# BeagleBone_Blue.net
KiCad netlist of a schematic drawn in EAGLE
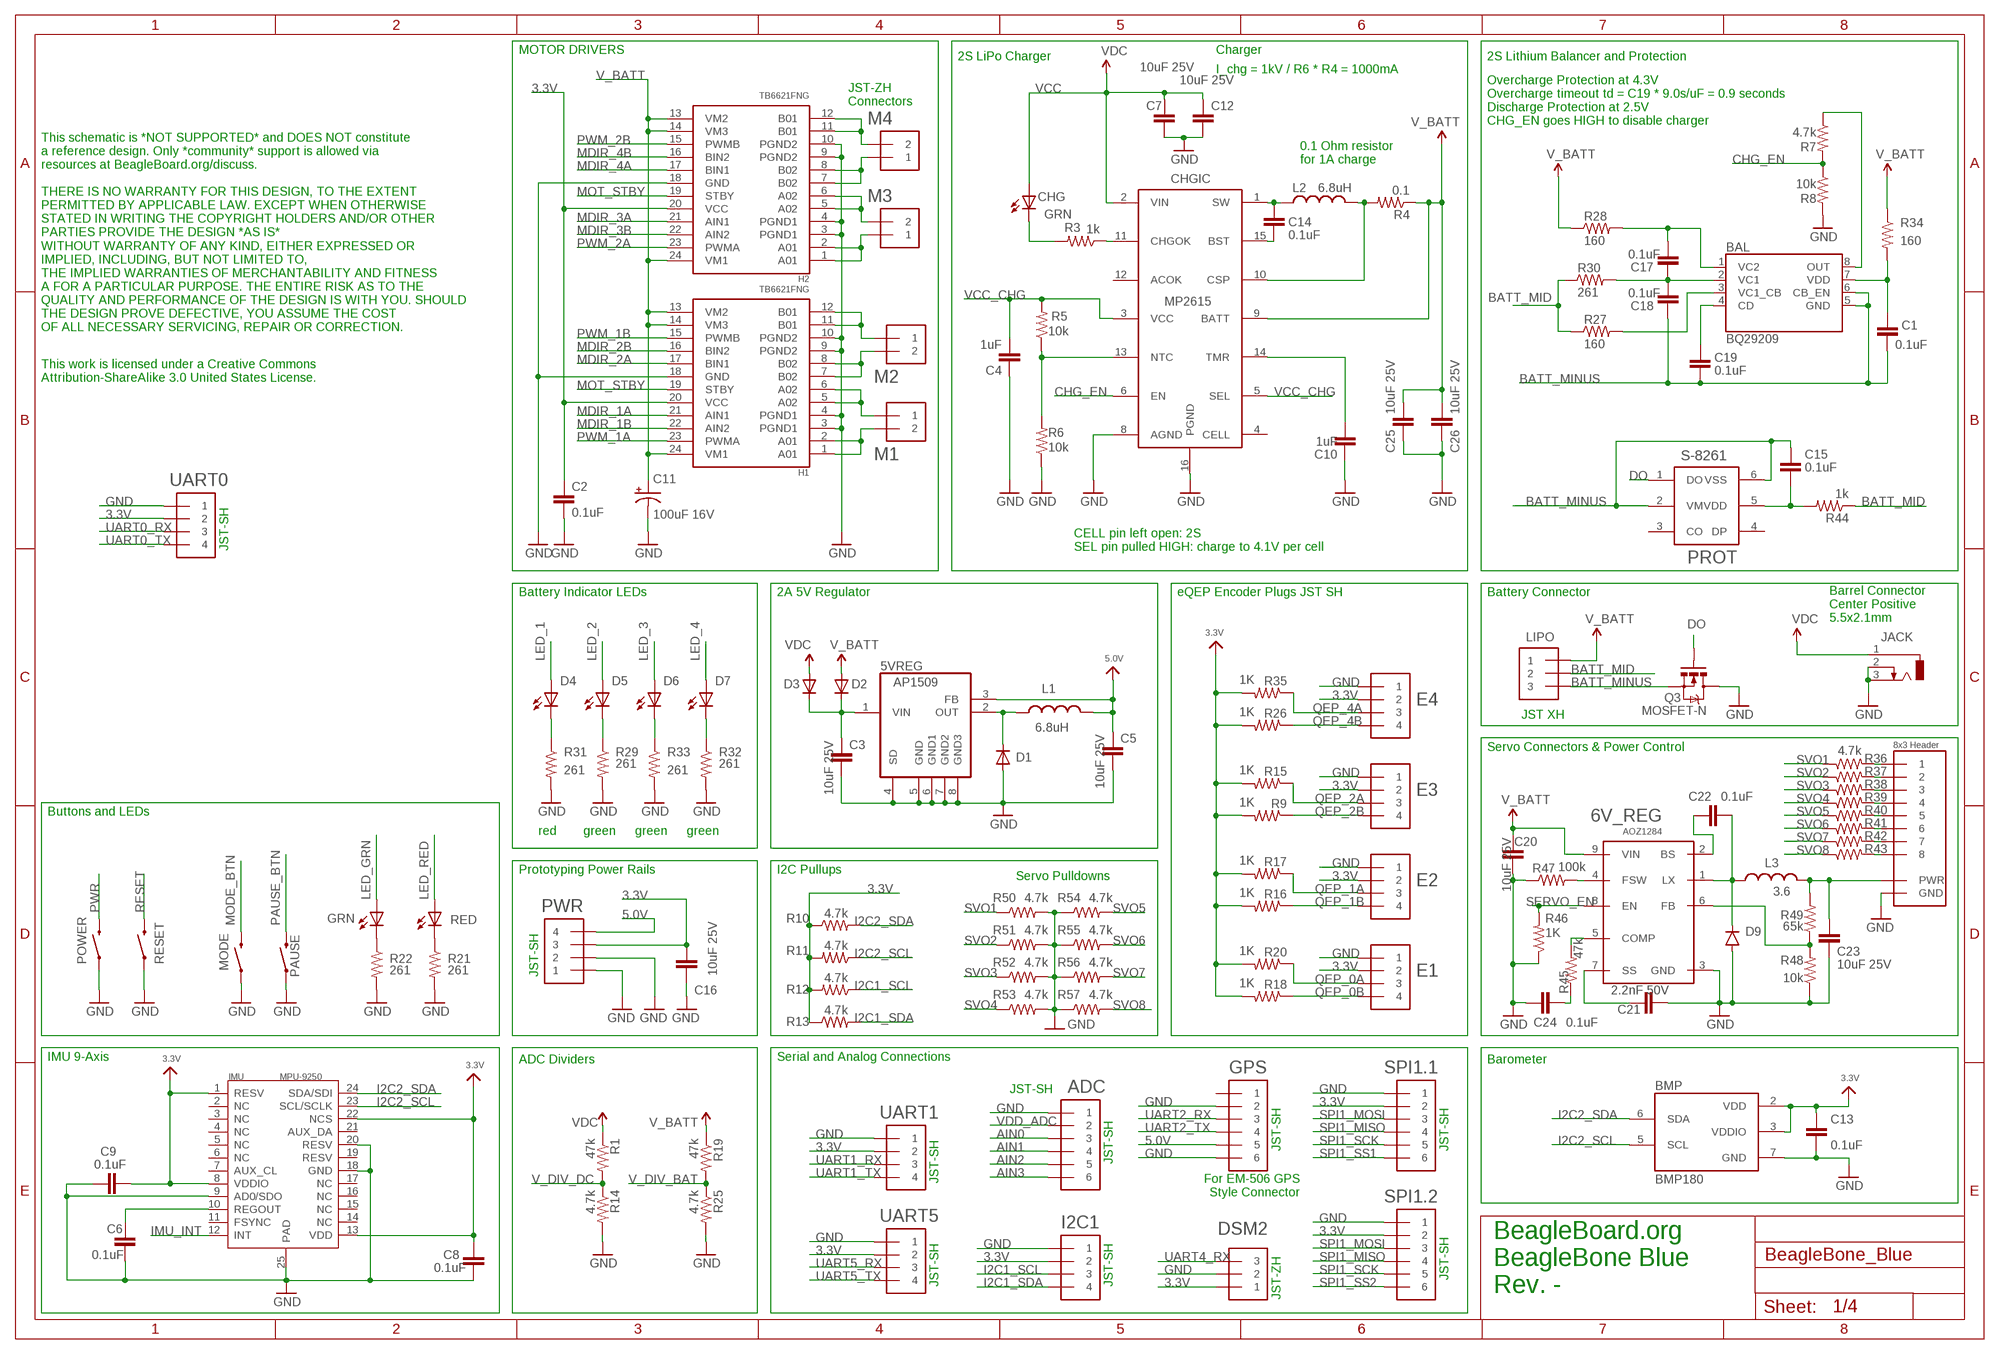
[diagram p0: schematic, sheet 1]
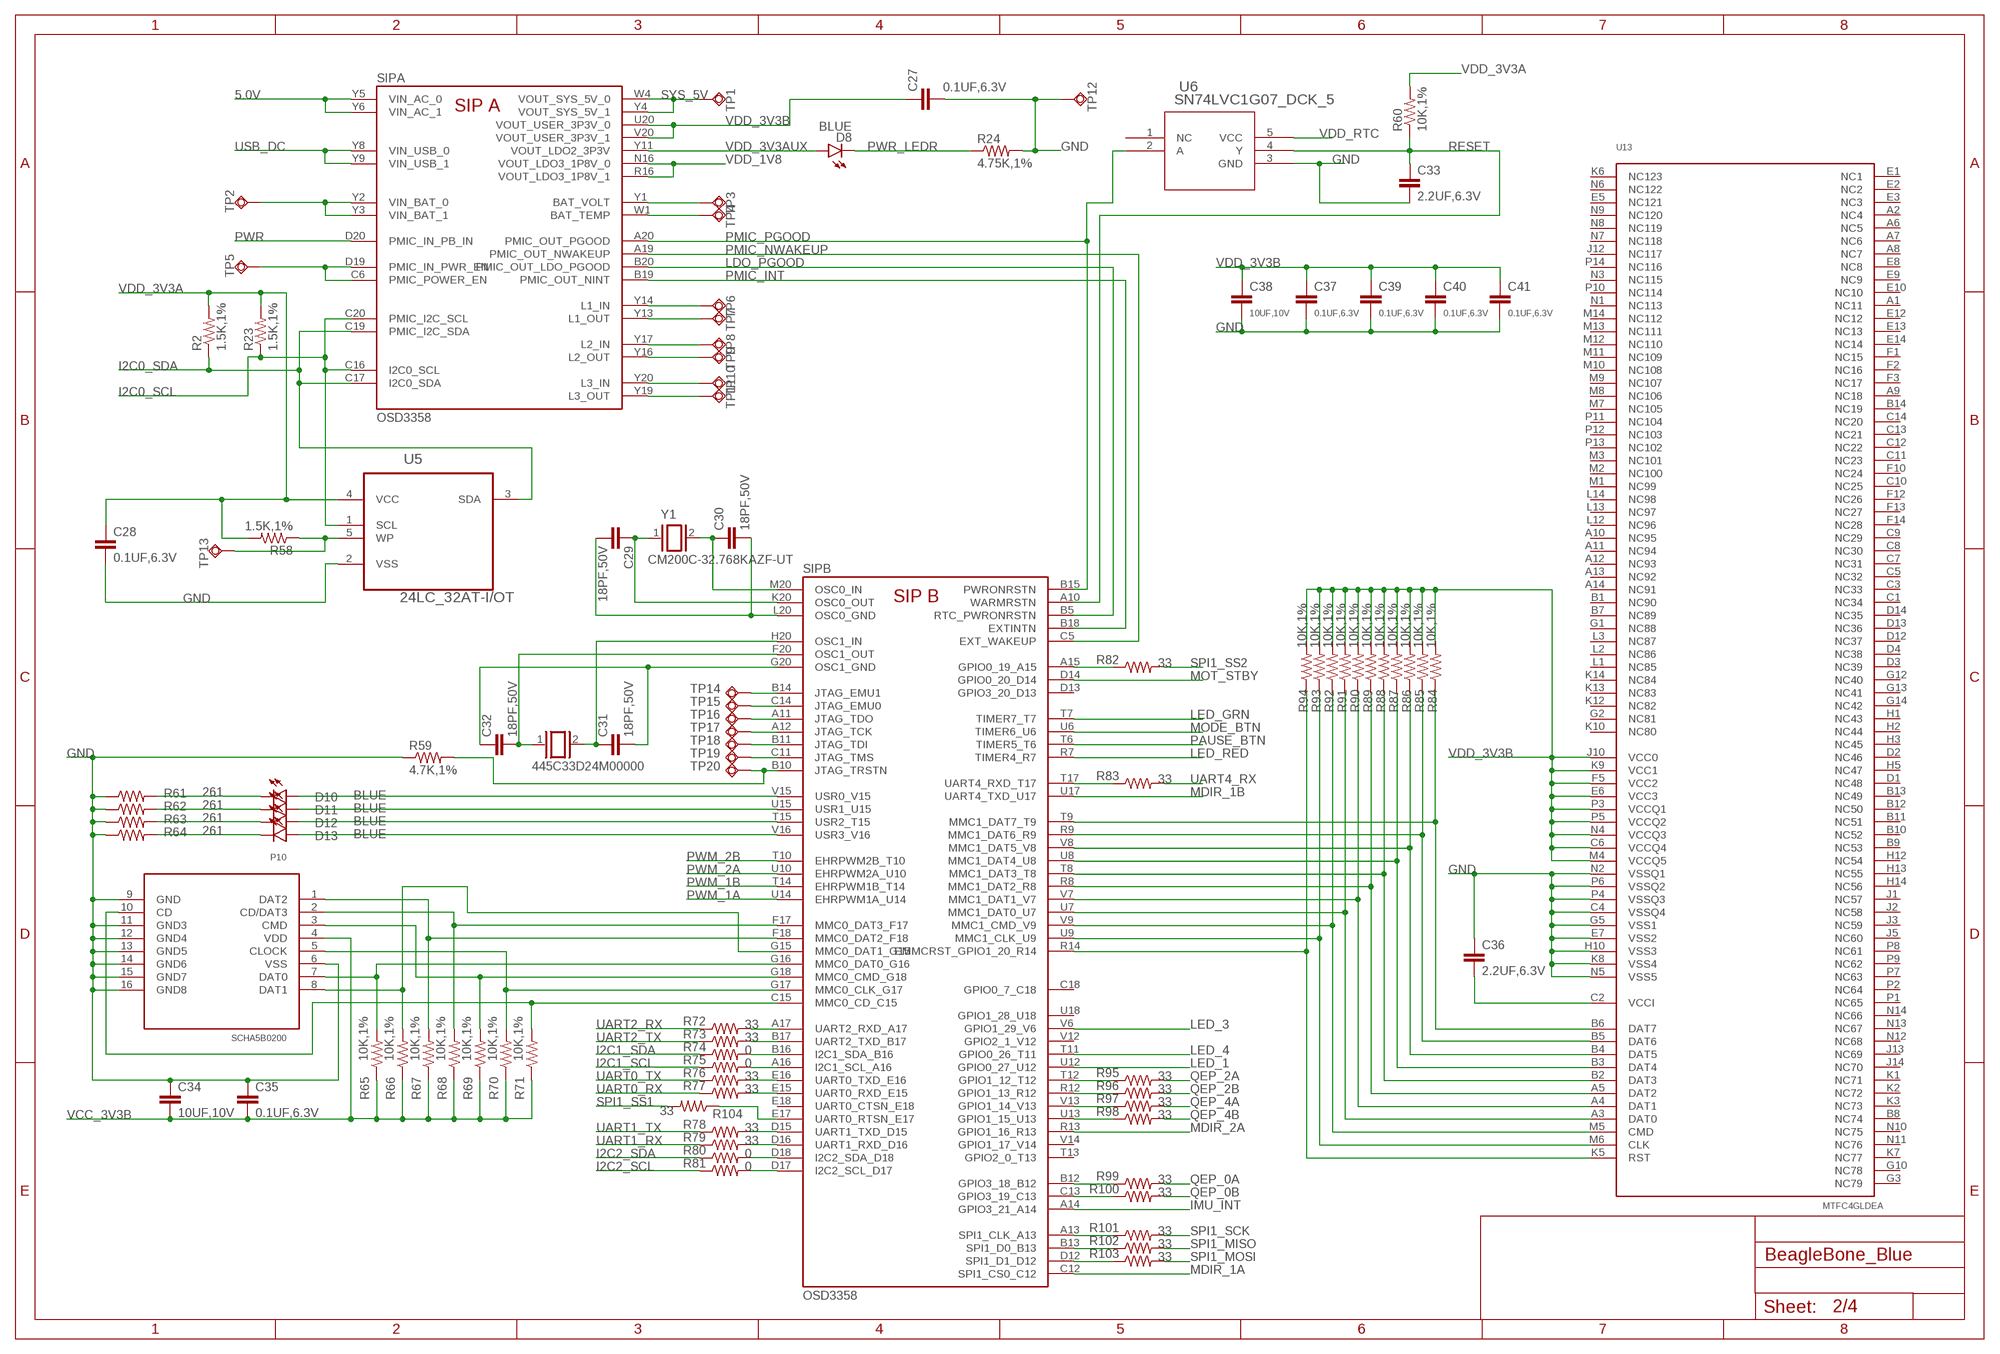
[diagram p1: schematic, sheet 2]
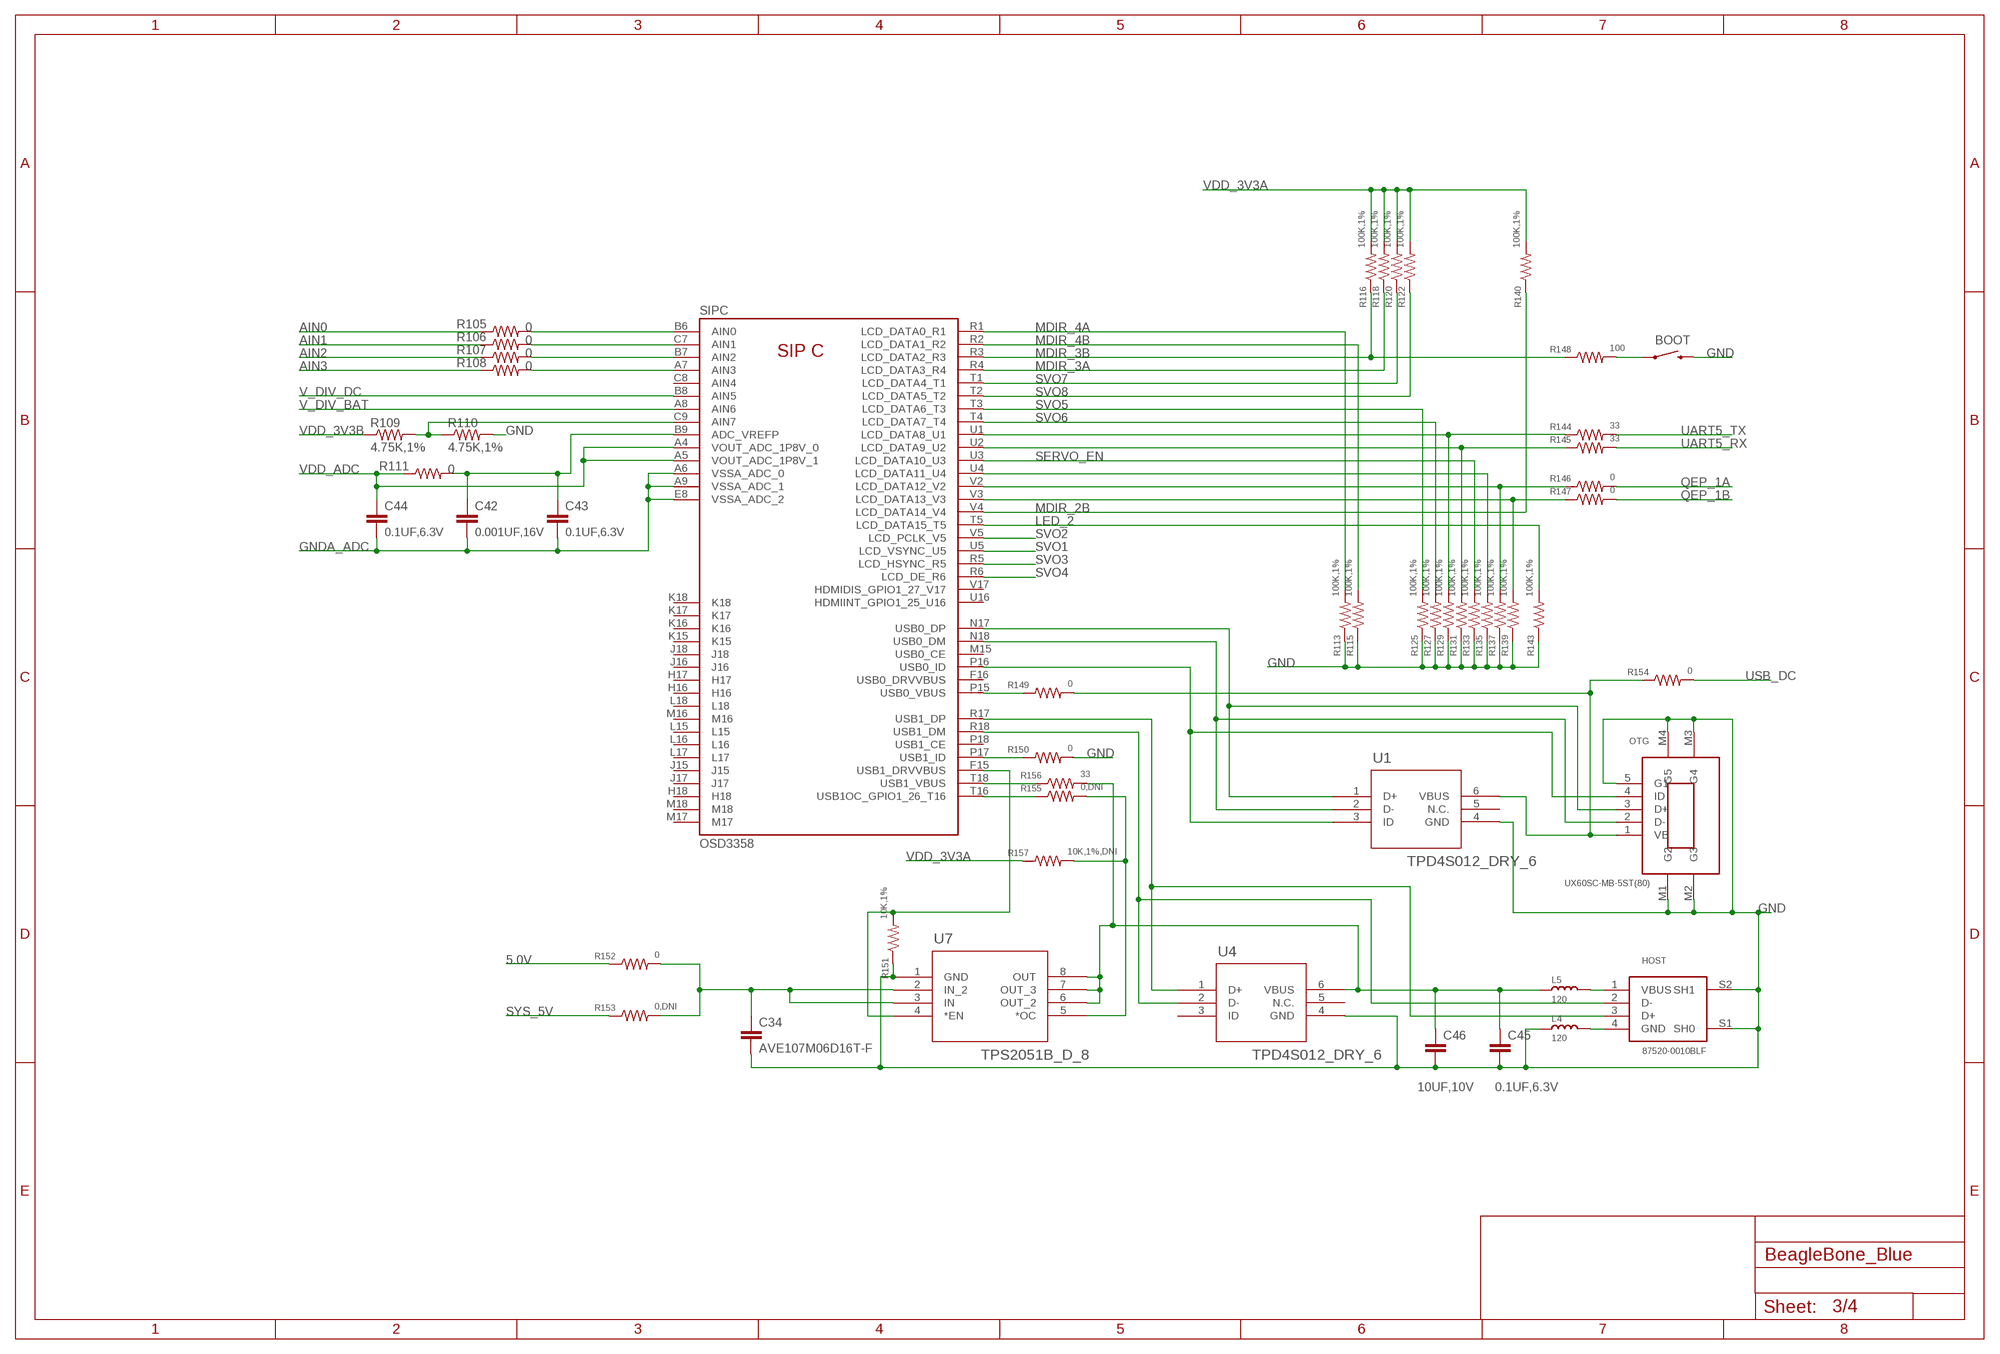
[diagram p2: schematic, sheet 3]
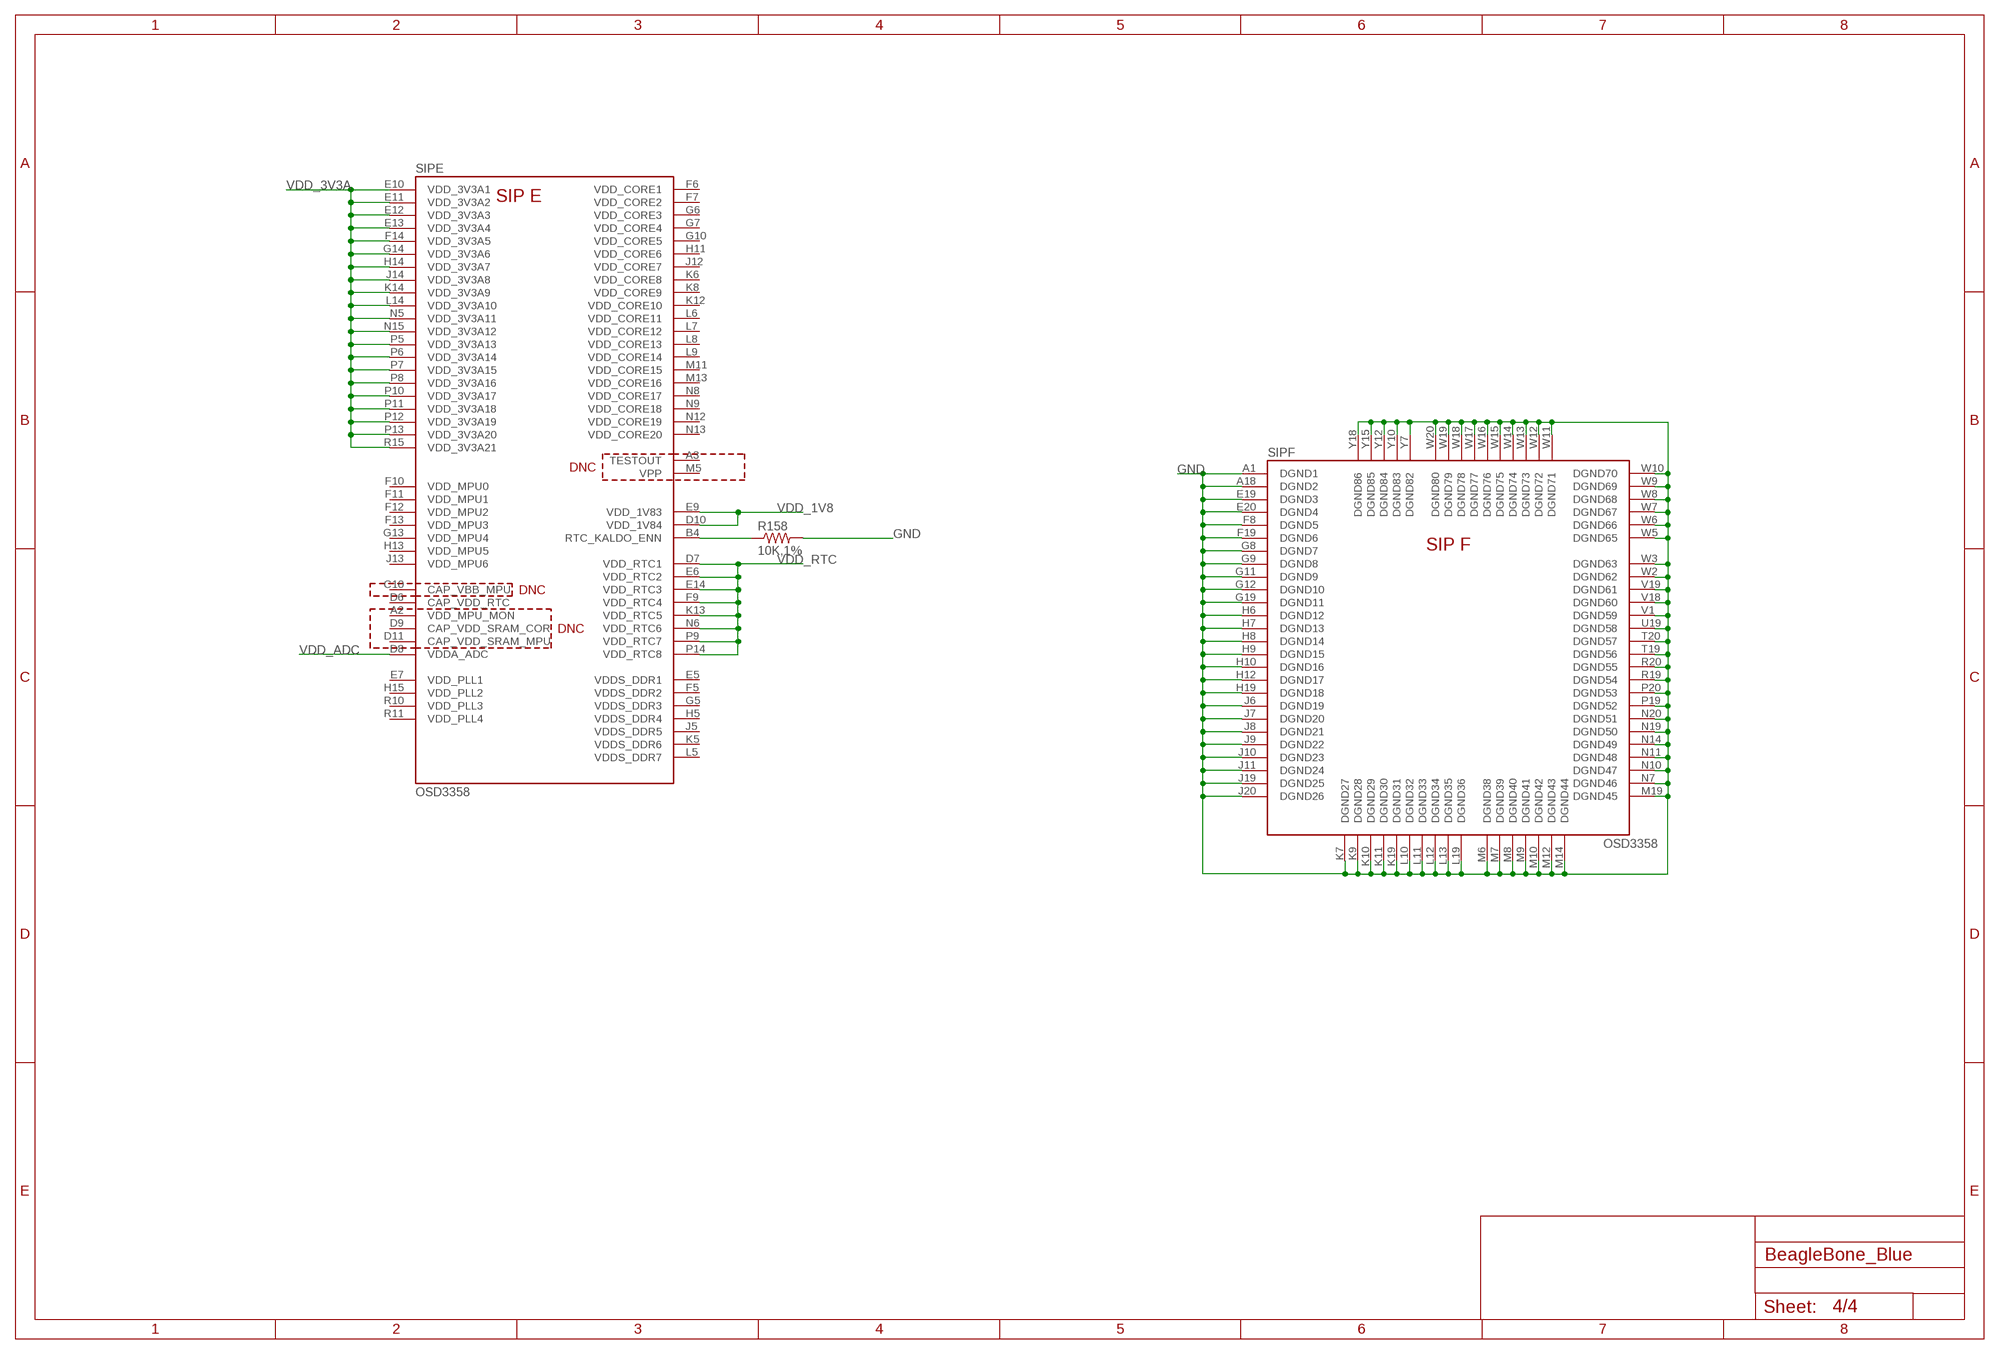
[diagram p3: schematic, sheet 4]

(export (version "E")
  (design (tool "Eeschema 10.0.6"))
  (components
    (comp (ref "R158")
      (value "10K,1%")
      (footprint "eagle-import:0402-RES")
      (libsource (lib "eagle-import") (part "RESISTOR0402-RES"))
    )
    (comp (ref "SIP")
      (value "OSD3358")
      (footprint "eagle-import:OSD3358")
      (libsource (lib "eagle-import") (part "OSD3358"))
    )
    (comp (ref "C27")
      (value "0.1UF,6.3V")
      (footprint "eagle-import:0402-CAP")
      (libsource (lib "eagle-import") (part "Strawson_Eagle_Lib_CAP0402-CAP"))
    )
    (comp (ref "C28")
      (value "0.1UF,6.3V")
      (footprint "eagle-import:0402-CAP")
      (libsource (lib "eagle-import") (part "Strawson_Eagle_Lib_CAP0402-CAP"))
    )
    (comp (ref "C29")
      (value "18PF,50V")
      (footprint "eagle-import:0402-CAP")
      (libsource (lib "eagle-import") (part "Strawson_Eagle_Lib_CAP0402-CAP"))
    )
    (comp (ref "C30")
      (value "18PF,50V")
      (footprint "eagle-import:0402-CAP")
      (libsource (lib "eagle-import") (part "Strawson_Eagle_Lib_CAP0402-CAP"))
    )
    (comp (ref "C31")
      (value "18PF,50V")
      (footprint "eagle-import:0402-CAP")
      (libsource (lib "eagle-import") (part "Strawson_Eagle_Lib_CAP0402-CAP"))
    )
    (comp (ref "C32")
      (value "18PF,50V")
      (footprint "eagle-import:0402-CAP")
      (libsource (lib "eagle-import") (part "Strawson_Eagle_Lib_CAP0402-CAP"))
    )
    (comp (ref "C33")
      (value "2.2UF,6.3V")
      (footprint "eagle-import:0402-CAP")
      (libsource (lib "eagle-import") (part "Strawson_Eagle_Lib_CAP0402-CAP"))
    )
    (comp (ref "C34")
      (value "10UF,10V")
      (footprint "eagle-import:0805")
      (libsource (lib "eagle-import") (part "Strawson_Eagle_Lib_CAP0805"))
    )
    (comp (ref "C35")
      (value "0.1UF,6.3V")
      (footprint "eagle-import:0402-CAP")
      (libsource (lib "eagle-import") (part "Strawson_Eagle_Lib_CAP0402-CAP"))
    )
    (comp (ref "C36")
      (value "2.2UF,6.3V")
      (footprint "eagle-import:0402-CAP")
      (libsource (lib "eagle-import") (part "Strawson_Eagle_Lib_CAP0402-CAP"))
    )
    (comp (ref "C37")
      (value "0.1UF,6.3V")
      (footprint "eagle-import:0402-CAP")
      (libsource (lib "eagle-import") (part "Strawson_Eagle_Lib_CAP0402-CAP"))
    )
    (comp (ref "C38")
      (value "10UF,10V")
      (footprint "eagle-import:0805")
      (libsource (lib "eagle-import") (part "Strawson_Eagle_Lib_CAP0805"))
    )
    (comp (ref "C39")
      (value "0.1UF,6.3V")
      (footprint "eagle-import:0402-CAP")
      (libsource (lib "eagle-import") (part "Strawson_Eagle_Lib_CAP0402-CAP"))
    )
    (comp (ref "C40")
      (value "0.1UF,6.3V")
      (footprint "eagle-import:0402-CAP")
      (libsource (lib "eagle-import") (part "Strawson_Eagle_Lib_CAP0402-CAP"))
    )
    (comp (ref "C41")
      (value "0.1UF,6.3V")
      (footprint "eagle-import:0402-CAP")
      (libsource (lib "eagle-import") (part "Strawson_Eagle_Lib_CAP0402-CAP"))
    )
    (comp (ref "D8")
      (value "BLUE")
      (footprint "eagle-import:LED-0603")
      (libsource (lib "eagle-import") (part "LED0603"))
    )
    (comp (ref "D10")
      (value "BLUE")
      (footprint "eagle-import:LED-0603")
      (libsource (lib "eagle-import") (part "LED0603"))
    )
    (comp (ref "D11")
      (value "BLUE")
      (footprint "eagle-import:LED-0603")
      (libsource (lib "eagle-import") (part "LED0603"))
    )
    (comp (ref "D12")
      (value "BLUE")
      (footprint "eagle-import:LED-0603")
      (libsource (lib "eagle-import") (part "LED0603"))
    )
    (comp (ref "D13")
      (value "BLUE")
      (footprint "eagle-import:LED-0603")
      (libsource (lib "eagle-import") (part "LED0603"))
    )
    (comp (ref "P10")
      (value "SCHA5B0200")
      (footprint "eagle-import:SCHA5B0200")
      (libsource (lib "eagle-import") (part "SCHA5B0200"))
    )
    (comp (ref "R2")
      (value "1.5K,1%")
      (footprint "eagle-import:0402-RES")
      (libsource (lib "eagle-import") (part "RESISTOR0402-RES"))
    )
    (comp (ref "R23")
      (value "1.5K,1%")
      (footprint "eagle-import:0402-RES")
      (libsource (lib "eagle-import") (part "RESISTOR0402-RES"))
    )
    (comp (ref "R24")
      (value "4.75K,1%")
      (footprint "eagle-import:0402-RES")
      (libsource (lib "eagle-import") (part "RESISTOR0402-RES"))
    )
    (comp (ref "R58")
      (value "1.5K,1%")
      (footprint "eagle-import:0402-RES")
      (libsource (lib "eagle-import") (part "RESISTOR0402-RES"))
    )
    (comp (ref "R59")
      (value "4.7K,1%")
      (footprint "eagle-import:0402-RES")
      (libsource (lib "eagle-import") (part "RESISTOR0402-RES"))
    )
    (comp (ref "R60")
      (value "10K,1%")
      (footprint "eagle-import:0402-RES")
      (libsource (lib "eagle-import") (part "RESISTOR0402-RES"))
    )
    (comp (ref "R61")
      (value "261")
      (footprint "eagle-import:0402-RES")
      (libsource (lib "eagle-import") (part "RESISTOR0402-RES"))
    )
    (comp (ref "R62")
      (value "261")
      (footprint "eagle-import:0402-RES")
      (libsource (lib "eagle-import") (part "RESISTOR0402-RES"))
    )
    (comp (ref "R63")
      (value "261")
      (footprint "eagle-import:0402-RES")
      (libsource (lib "eagle-import") (part "RESISTOR0402-RES"))
    )
    (comp (ref "R64")
      (value "261")
      (footprint "eagle-import:0402-RES")
      (libsource (lib "eagle-import") (part "RESISTOR0402-RES"))
    )
    (comp (ref "R65")
      (value "10K,1%")
      (footprint "eagle-import:0402-RES")
      (libsource (lib "eagle-import") (part "RESISTOR0402-RES"))
    )
    (comp (ref "R66")
      (value "10K,1%")
      (footprint "eagle-import:0402-RES")
      (libsource (lib "eagle-import") (part "RESISTOR0402-RES"))
    )
    (comp (ref "R67")
      (value "10K,1%")
      (footprint "eagle-import:0402-RES")
      (libsource (lib "eagle-import") (part "RESISTOR0402-RES"))
    )
    (comp (ref "R68")
      (value "10K,1%")
      (footprint "eagle-import:0402-RES")
      (libsource (lib "eagle-import") (part "RESISTOR0402-RES"))
    )
    (comp (ref "R69")
      (value "10K,1%")
      (footprint "eagle-import:0402-RES")
      (libsource (lib "eagle-import") (part "RESISTOR0402-RES"))
    )
    (comp (ref "R70")
      (value "10K,1%")
      (footprint "eagle-import:0402-RES")
      (libsource (lib "eagle-import") (part "RESISTOR0402-RES"))
    )
    (comp (ref "R71")
      (value "10K,1%")
      (footprint "eagle-import:0402-RES")
      (libsource (lib "eagle-import") (part "RESISTOR0402-RES"))
    )
    (comp (ref "R72")
      (value "33")
      (footprint "eagle-import:0402-RES")
      (libsource (lib "eagle-import") (part "RESISTOR0402-RES"))
    )
    (comp (ref "R73")
      (value "33")
      (footprint "eagle-import:0402-RES")
      (libsource (lib "eagle-import") (part "RESISTOR0402-RES"))
    )
    (comp (ref "R74")
      (value "0")
      (footprint "eagle-import:0402-RES")
      (libsource (lib "eagle-import") (part "RESISTOR0402-RES"))
    )
    (comp (ref "R75")
      (value "0")
      (footprint "eagle-import:0402-RES")
      (libsource (lib "eagle-import") (part "RESISTOR0402-RES"))
    )
    (comp (ref "R76")
      (value "33")
      (footprint "eagle-import:0402-RES")
      (libsource (lib "eagle-import") (part "RESISTOR0402-RES"))
    )
    (comp (ref "R77")
      (value "33")
      (footprint "eagle-import:0402-RES")
      (libsource (lib "eagle-import") (part "RESISTOR0402-RES"))
    )
    (comp (ref "R78")
      (value "33")
      (footprint "eagle-import:0402-RES")
      (libsource (lib "eagle-import") (part "RESISTOR0402-RES"))
    )
    (comp (ref "R79")
      (value "33")
      (footprint "eagle-import:0402-RES")
      (libsource (lib "eagle-import") (part "RESISTOR0402-RES"))
    )
    (comp (ref "R80")
      (value "0")
      (footprint "eagle-import:0402-RES")
      (libsource (lib "eagle-import") (part "RESISTOR0402-RES"))
    )
    (comp (ref "R81")
      (value "0")
      (footprint "eagle-import:0402-RES")
      (libsource (lib "eagle-import") (part "RESISTOR0402-RES"))
    )
    (comp (ref "R82")
      (value "33")
      (footprint "eagle-import:0402-RES")
      (libsource (lib "eagle-import") (part "RESISTOR0402-RES"))
    )
    (comp (ref "R83")
      (value "33")
      (footprint "eagle-import:0402-RES")
      (libsource (lib "eagle-import") (part "RESISTOR0402-RES"))
    )
    (comp (ref "R84")
      (value "10K,1%")
      (footprint "eagle-import:0402-RES")
      (libsource (lib "eagle-import") (part "RESISTOR0402-RES"))
    )
    (comp (ref "R85")
      (value "10K,1%")
      (footprint "eagle-import:0402-RES")
      (libsource (lib "eagle-import") (part "RESISTOR0402-RES"))
    )
    (comp (ref "R86")
      (value "10K,1%")
      (footprint "eagle-import:0402-RES")
      (libsource (lib "eagle-import") (part "RESISTOR0402-RES"))
    )
    (comp (ref "R87")
      (value "10K,1%")
      (footprint "eagle-import:0402-RES")
      (libsource (lib "eagle-import") (part "RESISTOR0402-RES"))
    )
    (comp (ref "R88")
      (value "10K,1%")
      (footprint "eagle-import:0402-RES")
      (libsource (lib "eagle-import") (part "RESISTOR0402-RES"))
    )
    (comp (ref "R89")
      (value "10K,1%")
      (footprint "eagle-import:0402-RES")
      (libsource (lib "eagle-import") (part "RESISTOR0402-RES"))
    )
    (comp (ref "R90")
      (value "10K,1%")
      (footprint "eagle-import:0402-RES")
      (libsource (lib "eagle-import") (part "RESISTOR0402-RES"))
    )
    (comp (ref "R91")
      (value "10K,1%")
      (footprint "eagle-import:0402-RES")
      (libsource (lib "eagle-import") (part "RESISTOR0402-RES"))
    )
    (comp (ref "R92")
      (value "10K,1%")
      (footprint "eagle-import:0402-RES")
      (libsource (lib "eagle-import") (part "RESISTOR0402-RES"))
    )
    (comp (ref "R93")
      (value "10K,1%")
      (footprint "eagle-import:0402-RES")
      (libsource (lib "eagle-import") (part "RESISTOR0402-RES"))
    )
    (comp (ref "R94")
      (value "10K,1%")
      (footprint "eagle-import:0402-RES")
      (libsource (lib "eagle-import") (part "RESISTOR0402-RES"))
    )
    (comp (ref "R95")
      (value "33")
      (footprint "eagle-import:0402-RES")
      (libsource (lib "eagle-import") (part "RESISTOR0402-RES"))
    )
    (comp (ref "R96")
      (value "33")
      (footprint "eagle-import:0402-RES")
      (libsource (lib "eagle-import") (part "RESISTOR0402-RES"))
    )
    (comp (ref "R97")
      (value "33")
      (footprint "eagle-import:0402-RES")
      (libsource (lib "eagle-import") (part "RESISTOR0402-RES"))
    )
    (comp (ref "R98")
      (value "33")
      (footprint "eagle-import:0402-RES")
      (libsource (lib "eagle-import") (part "RESISTOR0402-RES"))
    )
    (comp (ref "R99")
      (value "33")
      (footprint "eagle-import:0402-RES")
      (libsource (lib "eagle-import") (part "RESISTOR0402-RES"))
    )
    (comp (ref "R100")
      (value "33")
      (footprint "eagle-import:0402-RES")
      (libsource (lib "eagle-import") (part "RESISTOR0402-RES"))
    )
    (comp (ref "R101")
      (value "33")
      (footprint "eagle-import:0402-RES")
      (libsource (lib "eagle-import") (part "RESISTOR0402-RES"))
    )
    (comp (ref "R102")
      (value "33")
      (footprint "eagle-import:0402-RES")
      (libsource (lib "eagle-import") (part "RESISTOR0402-RES"))
    )
    (comp (ref "R103")
      (value "33")
      (footprint "eagle-import:0402-RES")
      (libsource (lib "eagle-import") (part "RESISTOR0402-RES"))
    )
    (comp (ref "R104")
      (value "33")
      (footprint "eagle-import:0402-RES")
      (libsource (lib "eagle-import") (part "RESISTOR0402-RES"))
    )
    (comp (ref "TP1")
      (value "TPSQB1,27")
      (footprint "eagle-import:B1,27")
      (libsource (lib "eagle-import") (part "TPSQB1,27"))
    )
    (comp (ref "TP2")
      (value "TPSQB1,27")
      (footprint "eagle-import:B1,27")
      (libsource (lib "eagle-import") (part "TPSQB1,27"))
    )
    (comp (ref "TP3")
      (value "TPSQB1,27")
      (footprint "eagle-import:B1,27")
      (libsource (lib "eagle-import") (part "TPSQB1,27"))
    )
    (comp (ref "TP4")
      (value "TPSQB1,27")
      (footprint "eagle-import:B1,27")
      (libsource (lib "eagle-import") (part "TPSQB1,27"))
    )
    (comp (ref "TP5")
      (value "TPSQB1,27")
      (footprint "eagle-import:B1,27")
      (libsource (lib "eagle-import") (part "TPSQB1,27"))
    )
    (comp (ref "TP6")
      (value "TPSQB1,27")
      (footprint "eagle-import:B1,27")
      (libsource (lib "eagle-import") (part "TPSQB1,27"))
    )
    (comp (ref "TP7")
      (value "TPSQB1,27")
      (footprint "eagle-import:B1,27")
      (libsource (lib "eagle-import") (part "TPSQB1,27"))
    )
    (comp (ref "TP8")
      (value "TPSQB1,27")
      (footprint "eagle-import:B1,27")
      (libsource (lib "eagle-import") (part "TPSQB1,27"))
    )
    (comp (ref "TP9")
      (value "TPSQB1,27")
      (footprint "eagle-import:B1,27")
      (libsource (lib "eagle-import") (part "TPSQB1,27"))
    )
    (comp (ref "TP10")
      (value "TPSQB1,27")
      (footprint "eagle-import:B1,27")
      (libsource (lib "eagle-import") (part "TPSQB1,27"))
    )
    (comp (ref "TP11")
      (value "TPSQB1,27")
      (footprint "eagle-import:B1,27")
      (libsource (lib "eagle-import") (part "TPSQB1,27"))
    )
    (comp (ref "TP12")
      (value "TPSQB1,27")
      (footprint "eagle-import:B1,27")
      (libsource (lib "eagle-import") (part "TPSQB1,27"))
    )
    (comp (ref "TP13")
      (value "TPSQB1,27")
      (footprint "eagle-import:B1,27")
      (libsource (lib "eagle-import") (part "TPSQB1,27"))
    )
    (comp (ref "TP14")
      (value "TPSQB1,27")
      (footprint "eagle-import:B1,27")
      (libsource (lib "eagle-import") (part "TPSQB1,27"))
    )
    (comp (ref "TP15")
      (value "TPSQB1,27")
      (footprint "eagle-import:B1,27")
      (libsource (lib "eagle-import") (part "TPSQB1,27"))
    )
    (comp (ref "TP16")
      (value "TPSQB1,27")
      (footprint "eagle-import:B1,27")
      (libsource (lib "eagle-import") (part "TPSQB1,27"))
    )
    (comp (ref "TP17")
      (value "TPSQB1,27")
      (footprint "eagle-import:B1,27")
      (libsource (lib "eagle-import") (part "TPSQB1,27"))
    )
    (comp (ref "TP18")
      (value "TPSQB1,27")
      (footprint "eagle-import:B1,27")
      (libsource (lib "eagle-import") (part "TPSQB1,27"))
    )
    (comp (ref "TP19")
      (value "TPSQB1,27")
      (footprint "eagle-import:B1,27")
      (libsource (lib "eagle-import") (part "TPSQB1,27"))
    )
    (comp (ref "TP20")
      (value "TPSQB1,27")
      (footprint "eagle-import:B1,27")
      (libsource (lib "eagle-import") (part "TPSQB1,27"))
    )
    (comp (ref "U5")
      (value "24LC_32AT-I/OT")
      (footprint "eagle-import:SOT95P290X145-5N")
      (fields (field (name "MPN") "24LC32AT-I/OT"))
      (libsource (lib "eagle-import") (part "24LC_32AT-I/OT"))
    )
    (comp (ref "U6")
      (value "SN74LVC1G07_DCK_5")
      (footprint "eagle-import:DCK5")
      (fields
        (field (name "GENERIC_PART_NUMBER") "SN74LVC1G07")
        (field (name "MANUFACTURER") "Texas Instruments")
        (field (name "MANUFACTURER_PART_NUMBER") "sn74lvc1g07_dck_5")
      )
      (libsource (lib "eagle-import") (part "SN74LVC1G07_DCK_5"))
    )
    (comp (ref "U8")
      (value "MTFC4GLDEA")
      (footprint "eagle-import:MTFC4GLDEA")
      (libsource (lib "eagle-import") (part "MTFC4GLDEA"))
    )
    (comp (ref "Y1")
      (value "CM200C-32.768KAZF-UT")
      (footprint "eagle-import:CM200C-32.768KAZF-UT")
      (libsource (lib "eagle-import") (part "CM200C-32.768KAZF-UT"))
    )
    (comp (ref "Y2")
      (value "445C33D24M00000")
      (footprint "eagle-import:445C33D24M00000")
      (libsource (lib "eagle-import") (part "445C33D24M00000"))
    )
    (comp (ref "BOOT")
      (value "SWITCH-MOMENTARY-2SMD-1101NE")
      (footprint "eagle-import:TACTILE-SWITCH-1101NE")
      (libsource (lib "eagle-import") (part "SWITCH-MOMENTARY-2SMD-1101NE"))
    )
    (comp (ref "C$1")
      (value "AVE107M06D16T-F")
      (footprint "eagle-import:AVE107M06D16T-F")
      (libsource (lib "eagle-import") (part "AVE107M06D16T-F"))
    )
    (comp (ref "C42")
      (value "0.001UF,16V")
      (footprint "eagle-import:0402-CAP")
      (libsource (lib "eagle-import") (part "Strawson_Eagle_Lib_CAP0402-CAP"))
    )
    (comp (ref "C43")
      (value "0.1UF,6.3V")
      (footprint "eagle-import:0402-CAP")
      (libsource (lib "eagle-import") (part "Strawson_Eagle_Lib_CAP0402-CAP"))
    )
    (comp (ref "C44")
      (value "0.1UF,6.3V")
      (footprint "eagle-import:0402-CAP")
      (libsource (lib "eagle-import") (part "Strawson_Eagle_Lib_CAP0402-CAP"))
    )
    (comp (ref "C45")
      (value "0.1UF,6.3V")
      (footprint "eagle-import:0402-CAP")
      (libsource (lib "eagle-import") (part "Strawson_Eagle_Lib_CAP0402-CAP"))
    )
    (comp (ref "C46")
      (value "10UF,10V")
      (footprint "eagle-import:0805")
      (libsource (lib "eagle-import") (part "Strawson_Eagle_Lib_CAP0805"))
    )
    (comp (ref "HOST")
      (value "87520-0010BLF")
      (footprint "eagle-import:87520-0010BLF")
      (libsource (lib "eagle-import") (part "87520-0010BLF"))
    )
    (comp (ref "L4")
      (value "120")
      (footprint "eagle-import:L0603")
      (libsource (lib "eagle-import") (part "INDUCTOR/FERRITE-BEAD'0603'"))
    )
    (comp (ref "L5")
      (value "120")
      (footprint "eagle-import:L0603")
      (libsource (lib "eagle-import") (part "INDUCTOR/FERRITE-BEAD'0603'"))
    )
    (comp (ref "OTG")
      (value "UX60SC-MB-5ST(80)")
      (footprint "eagle-import:UX60SC-MB-5ST(80)")
      (libsource (lib "eagle-import") (part "UX60SC-MB-5ST(80)"))
    )
    (comp (ref "R105")
      (value "0")
      (footprint "eagle-import:0402-RES")
      (libsource (lib "eagle-import") (part "RESISTOR0402-RES"))
    )
    (comp (ref "R106")
      (value "0")
      (footprint "eagle-import:0402-RES")
      (libsource (lib "eagle-import") (part "RESISTOR0402-RES"))
    )
    (comp (ref "R107")
      (value "0")
      (footprint "eagle-import:0402-RES")
      (libsource (lib "eagle-import") (part "RESISTOR0402-RES"))
    )
    (comp (ref "R108")
      (value "0")
      (footprint "eagle-import:0402-RES")
      (libsource (lib "eagle-import") (part "RESISTOR0402-RES"))
    )
    (comp (ref "R109")
      (value "4.75K,1%")
      (footprint "eagle-import:0402-RES")
      (libsource (lib "eagle-import") (part "RESISTOR0402-RES"))
    )
    (comp (ref "R110")
      (value "4.75K,1%")
      (footprint "eagle-import:0402-RES")
      (libsource (lib "eagle-import") (part "RESISTOR0402-RES"))
    )
    (comp (ref "R111")
      (value "0")
      (footprint "eagle-import:0402-RES")
      (libsource (lib "eagle-import") (part "RESISTOR0402-RES"))
    )
    (comp (ref "R113")
      (value "100K,1%")
      (footprint "eagle-import:0402-RES")
      (libsource (lib "eagle-import") (part "RESISTOR0402-RES"))
    )
    (comp (ref "R115")
      (value "100K,1%")
      (footprint "eagle-import:0402-RES")
      (libsource (lib "eagle-import") (part "RESISTOR0402-RES"))
    )
    (comp (ref "R116")
      (value "100K,1%")
      (footprint "eagle-import:0402-RES")
      (libsource (lib "eagle-import") (part "RESISTOR0402-RES"))
    )
    (comp (ref "R118")
      (value "100K,1%")
      (footprint "eagle-import:0402-RES")
      (libsource (lib "eagle-import") (part "RESISTOR0402-RES"))
    )
    (comp (ref "R120")
      (value "100K,1%")
      (footprint "eagle-import:0402-RES")
      (libsource (lib "eagle-import") (part "RESISTOR0402-RES"))
    )
    (comp (ref "R122")
      (value "100K,1%")
      (footprint "eagle-import:0402-RES")
      (libsource (lib "eagle-import") (part "RESISTOR0402-RES"))
    )
    (comp (ref "R125")
      (value "100K,1%")
      (footprint "eagle-import:0402-RES")
      (libsource (lib "eagle-import") (part "RESISTOR0402-RES"))
    )
    (comp (ref "R127")
      (value "100K,1%")
      (footprint "eagle-import:0402-RES")
      (libsource (lib "eagle-import") (part "RESISTOR0402-RES"))
    )
    (comp (ref "R129")
      (value "100K,1%")
      (footprint "eagle-import:0402-RES")
      (libsource (lib "eagle-import") (part "RESISTOR0402-RES"))
    )
    (comp (ref "R131")
      (value "100K,1%")
      (footprint "eagle-import:0402-RES")
      (libsource (lib "eagle-import") (part "RESISTOR0402-RES"))
    )
    (comp (ref "R133")
      (value "100K,1%")
      (footprint "eagle-import:0402-RES")
      (libsource (lib "eagle-import") (part "RESISTOR0402-RES"))
    )
    (comp (ref "R135")
      (value "100K,1%")
      (footprint "eagle-import:0402-RES")
      (libsource (lib "eagle-import") (part "RESISTOR0402-RES"))
    )
    (comp (ref "R137")
      (value "100K,1%")
      (footprint "eagle-import:0402-RES")
      (libsource (lib "eagle-import") (part "RESISTOR0402-RES"))
    )
    (comp (ref "R139")
      (value "100K,1%")
      (footprint "eagle-import:0402-RES")
      (libsource (lib "eagle-import") (part "RESISTOR0402-RES"))
    )
    (comp (ref "R140")
      (value "100K,1%")
      (footprint "eagle-import:0402-RES")
      (libsource (lib "eagle-import") (part "RESISTOR0402-RES"))
    )
    (comp (ref "R143")
      (value "100K,1%")
      (footprint "eagle-import:0402-RES")
      (libsource (lib "eagle-import") (part "RESISTOR0402-RES"))
    )
    (comp (ref "R144")
      (value "33")
      (footprint "eagle-import:0402-RES")
      (libsource (lib "eagle-import") (part "RESISTOR0402-RES"))
    )
    (comp (ref "R145")
      (value "33")
      (footprint "eagle-import:0402-RES")
      (libsource (lib "eagle-import") (part "RESISTOR0402-RES"))
    )
    (comp (ref "R146")
      (value "0")
      (footprint "eagle-import:0402-RES")
      (libsource (lib "eagle-import") (part "RESISTOR0402-RES"))
    )
    (comp (ref "R147")
      (value "0")
      (footprint "eagle-import:0402-RES")
      (libsource (lib "eagle-import") (part "RESISTOR0402-RES"))
    )
    (comp (ref "R148")
      (value "100")
      (footprint "eagle-import:0402-RES")
      (libsource (lib "eagle-import") (part "RESISTOR0402-RES"))
    )
    (comp (ref "R149")
      (value "0")
      (footprint "eagle-import:0402-RES")
      (libsource (lib "eagle-import") (part "RESISTOR0402-RES"))
    )
    (comp (ref "R150")
      (value "0")
      (footprint "eagle-import:0402-RES")
      (libsource (lib "eagle-import") (part "RESISTOR0402-RES"))
    )
    (comp (ref "R151")
      (value "10K,1%")
      (footprint "eagle-import:0402-RES")
      (libsource (lib "eagle-import") (part "RESISTOR0402-RES"))
    )
    (comp (ref "R152")
      (value "0")
      (footprint "eagle-import:0402-RES")
      (libsource (lib "eagle-import") (part "RESISTOR0402-RES"))
    )
    (comp (ref "R153")
      (value "0,DNI")
      (footprint "eagle-import:0402-RES")
      (libsource (lib "eagle-import") (part "RESISTOR0402-RES"))
    )
    (comp (ref "R154")
      (value "0")
      (footprint "eagle-import:0402-RES")
      (libsource (lib "eagle-import") (part "RESISTOR0402-RES"))
    )
    (comp (ref "R155")
      (value "0,DNI")
      (footprint "eagle-import:0402-RES")
      (libsource (lib "eagle-import") (part "RESISTOR0402-RES"))
    )
    (comp (ref "R156")
      (value "33")
      (footprint "eagle-import:0402-RES")
      (libsource (lib "eagle-import") (part "RESISTOR0402-RES"))
    )
    (comp (ref "R157")
      (value "10K,1%,DNI")
      (footprint "eagle-import:0402-RES")
      (libsource (lib "eagle-import") (part "RESISTOR0402-RES"))
    )
    (comp (ref "U1")
      (value "TPD4S012_DRY_6")
      (footprint "eagle-import:DRY6")
      (fields
        (field (name "GENERIC_PART_NUMBER") "TPD4S012")
        (field (name "MANUFACTURER") "Texas Instruments")
        (field (name "MANUFACTURER_PART_NUMBER") "tpd4s012_dry_6")
      )
      (libsource (lib "eagle-import") (part "TPD4S012_DRY_6"))
    )
    (comp (ref "U4")
      (value "TPD4S012_DRY_6")
      (footprint "eagle-import:DRY6")
      (fields
        (field (name "GENERIC_PART_NUMBER") "TPD4S012")
        (field (name "MANUFACTURER") "Texas Instruments")
        (field (name "MANUFACTURER_PART_NUMBER") "tpd4s012_dry_6")
      )
      (libsource (lib "eagle-import") (part "TPD4S012_DRY_6"))
    )
    (comp (ref "U7")
      (value "TPS2051B_D_8")
      (footprint "eagle-import:D8")
      (fields
        (field (name "GENERIC_PART_NUMBER") "TPS2051B")
        (field (name "MANUFACTURER") "Texas Instruments")
        (field (name "MANUFACTURER_PART_NUMBER") "tps2051b_d_8")
      )
      (libsource (lib "eagle-import") (part "TPS2051B_D_8"))
    )
    (comp (ref "5VREG")
      (value "AP1509SOIC-8-TIGHT")
      (footprint "eagle-import:SO08-TIGHT")
      (libsource (lib "eagle-import") (part "AP1509SOIC-8-TIGHT"))
    )
    (comp (ref "6V_REG")
      (value "AOZ1284")
      (footprint "eagle-import:SO08-EXPOSED")
      (libsource (lib "eagle-import") (part "AOZ1284"))
    )
    (comp (ref "ADC")
      (value "JST_SH_6")
      (footprint "eagle-import:JST_SH_6")
      (libsource (lib "eagle-import") (part "JST_SH_6"))
    )
    (comp (ref "BAL")
      (value "BQ29209")
      (footprint "eagle-import:8-SON_3X3MM")
      (libsource (lib "eagle-import") (part "BQ29209"))
    )
    (comp (ref "BMP")
      (value "BMP180")
      (footprint "eagle-import:BMP180")
      (libsource (lib "eagle-import") (part "BMP180"))
    )
    (comp (ref "C1")
      (value "0.1uF")
      (footprint "eagle-import:0402-CAP")
      (libsource (lib "eagle-import") (part "Strawson_Eagle_Lib_CAP0402-CAP"))
    )
    (comp (ref "C2")
      (value "0.1uF")
      (footprint "eagle-import:0402-CAP")
      (libsource (lib "eagle-import") (part "Strawson_Eagle_Lib_CAP0402-CAP"))
    )
    (comp (ref "C3")
      (value "10uF 25V")
      (footprint "eagle-import:0805")
      (libsource (lib "eagle-import") (part "CAP0805"))
    )
    (comp (ref "C4")
      (value "1uF")
      (footprint "eagle-import:0402-CAP")
      (libsource (lib "eagle-import") (part "Strawson_Eagle_Lib_CAP0402-CAP"))
    )
    (comp (ref "C5")
      (value "10uF 25V")
      (footprint "eagle-import:0805")
      (libsource (lib "eagle-import") (part "CAP0805"))
    )
    (comp (ref "C6")
      (value "0.1uF")
      (footprint "eagle-import:0402-CAP")
      (libsource (lib "eagle-import") (part "Strawson_Eagle_Lib_CAP0402-CAP"))
    )
    (comp (ref "C7")
      (value "10uF 25V")
      (footprint "eagle-import:0805")
      (libsource (lib "eagle-import") (part "CAP0805"))
    )
    (comp (ref "C8")
      (value "0.1uF")
      (footprint "eagle-import:0402-CAP")
      (libsource (lib "eagle-import") (part "Strawson_Eagle_Lib_CAP0402-CAP"))
    )
    (comp (ref "C9")
      (value "0.1uF")
      (footprint "eagle-import:0402-CAP")
      (libsource (lib "eagle-import") (part "Strawson_Eagle_Lib_CAP0402-CAP"))
    )
    (comp (ref "C10")
      (value "1uF")
      (footprint "eagle-import:0402-CAP")
      (libsource (lib "eagle-import") (part "Strawson_Eagle_Lib_CAP0402-CAP"))
    )
    (comp (ref "C11")
      (value "100uF 16V")
      (footprint "eagle-import:PANASONIC_D")
      (libsource (lib "eagle-import") (part "CPOL-USD"))
    )
    (comp (ref "C12")
      (value "10uF 25V")
      (footprint "eagle-import:0805")
      (libsource (lib "eagle-import") (part "CAP0805"))
    )
    (comp (ref "C13")
      (value "0.1uF")
      (footprint "eagle-import:0402-CAP")
      (libsource (lib "eagle-import") (part "Strawson_Eagle_Lib_CAP0402-CAP"))
    )
    (comp (ref "C14")
      (value "0.1uF")
      (footprint "eagle-import:0402-CAP")
      (libsource (lib "eagle-import") (part "Strawson_Eagle_Lib_CAP0402-CAP"))
    )
    (comp (ref "C15")
      (value "0.1uF")
      (footprint "eagle-import:0402-CAP")
      (libsource (lib "eagle-import") (part "Strawson_Eagle_Lib_CAP0402-CAP"))
    )
    (comp (ref "C16")
      (value "10uF 25V")
      (footprint "eagle-import:0805")
      (libsource (lib "eagle-import") (part "CAP0805"))
    )
    (comp (ref "C17")
      (value "0.1uF")
      (footprint "eagle-import:0402-CAP")
      (libsource (lib "eagle-import") (part "Strawson_Eagle_Lib_CAP0402-CAP"))
    )
    (comp (ref "C18")
      (value "0.1uF")
      (footprint "eagle-import:0402-CAP")
      (libsource (lib "eagle-import") (part "Strawson_Eagle_Lib_CAP0402-CAP"))
    )
    (comp (ref "C19")
      (value "0.1uF")
      (footprint "eagle-import:0402-CAP")
      (libsource (lib "eagle-import") (part "Strawson_Eagle_Lib_CAP0402-CAP"))
    )
    (comp (ref "C20")
      (value "10uF 25V")
      (footprint "eagle-import:0805")
      (libsource (lib "eagle-import") (part "CAP0805"))
    )
    (comp (ref "C21")
      (value "2.2nF 50V")
      (footprint "eagle-import:0402-CAP")
      (libsource (lib "eagle-import") (part "Strawson_Eagle_Lib_CAP0402-CAP"))
    )
    (comp (ref "C22")
      (value "0.1uF")
      (footprint "eagle-import:0402-CAP")
      (libsource (lib "eagle-import") (part "Strawson_Eagle_Lib_CAP0402-CAP"))
    )
    (comp (ref "C23")
      (value "10uF 25V")
      (footprint "eagle-import:0805")
      (libsource (lib "eagle-import") (part "CAP0805"))
    )
    (comp (ref "C24")
      (value "0.1uF")
      (footprint "eagle-import:0402-CAP")
      (libsource (lib "eagle-import") (part "Strawson_Eagle_Lib_CAP0402-CAP"))
    )
    (comp (ref "C25")
      (value "10uF 25V")
      (footprint "eagle-import:0805")
      (libsource (lib "eagle-import") (part "CAP0805"))
    )
    (comp (ref "C26")
      (value "10uF 25V")
      (footprint "eagle-import:0805")
      (libsource (lib "eagle-import") (part "CAP0805"))
    )
    (comp (ref "CHG")
      (value "GRN")
      (footprint "eagle-import:LED-0603")
      (libsource (lib "eagle-import") (part "SparkFun-LED_LED0603"))
    )
    (comp (ref "CHGIC")
      (value "MP2615")
      (footprint "eagle-import:MP2615")
      (libsource (lib "eagle-import") (part "MP2615"))
    )
    (comp (ref "D1")
      (value "DIODESOD-123")
      (footprint "eagle-import:SOD-123")
      (libsource (lib "eagle-import") (part "DIODESOD-123"))
    )
    (comp (ref "D2")
      (value "DIODESOD-123")
      (footprint "eagle-import:SOD-123")
      (libsource (lib "eagle-import") (part "DIODESOD-123"))
    )
    (comp (ref "D3")
      (value "DIODESOD-123")
      (footprint "eagle-import:SOD-123")
      (libsource (lib "eagle-import") (part "DIODESOD-123"))
    )
    (comp (ref "D4")
      (value "RED")
      (footprint "eagle-import:LED-0603")
      (libsource (lib "eagle-import") (part "SparkFun-LED_LED0603"))
    )
    (comp (ref "D5")
      (value "GREEN")
      (footprint "eagle-import:LED-0603")
      (libsource (lib "eagle-import") (part "SparkFun-LED_LED0603"))
    )
    (comp (ref "D6")
      (value "GREEN")
      (footprint "eagle-import:LED-0603")
      (libsource (lib "eagle-import") (part "SparkFun-LED_LED0603"))
    )
    (comp (ref "D7")
      (value "GREEN")
      (footprint "eagle-import:LED-0603")
      (libsource (lib "eagle-import") (part "SparkFun-LED_LED0603"))
    )
    (comp (ref "D9")
      (value "DIODEDO214AA")
      (footprint "eagle-import:DO-214AA")
      (libsource (lib "eagle-import") (part "DIODEDO214AA"))
    )
    (comp (ref "DSM2")
      (value "JST_ZH_3")
      (footprint "eagle-import:JST_ZH_3")
      (libsource (lib "eagle-import") (part "JST_ZH_3"))
    )
    (comp (ref "E1")
      (value "JST_SH_4")
      (footprint "eagle-import:JST_SH_4_SMD")
      (libsource (lib "eagle-import") (part "JST_SH_4"))
    )
    (comp (ref "E2")
      (value "JST_SH_4")
      (footprint "eagle-import:JST_SH_4_SMD")
      (libsource (lib "eagle-import") (part "JST_SH_4"))
    )
    (comp (ref "E3")
      (value "JST_SH_4")
      (footprint "eagle-import:JST_SH_4_SMD")
      (libsource (lib "eagle-import") (part "JST_SH_4"))
    )
    (comp (ref "E4")
      (value "JST_SH_4")
      (footprint "eagle-import:JST_SH_4_SMD")
      (libsource (lib "eagle-import") (part "JST_SH_4"))
    )
    (comp (ref "GPS")
      (value "JST_SH_6")
      (footprint "eagle-import:JST_SH_6")
      (libsource (lib "eagle-import") (part "JST_SH_6"))
    )
    (comp (ref "GRN")
      (value "GRN")
      (footprint "eagle-import:LED-0603")
      (libsource (lib "eagle-import") (part "SparkFun-LED_LED0603"))
    )
    (comp (ref "H1")
      (value "TB6621FNG")
      (footprint "eagle-import:SSOP24")
      (libsource (lib "eagle-import") (part "TB6621FNG"))
    )
    (comp (ref "H2")
      (value "TB6621FNG")
      (footprint "eagle-import:SSOP24")
      (libsource (lib "eagle-import") (part "TB6621FNG"))
    )
    (comp (ref "I2C1")
      (value "JST_SH_4")
      (footprint "eagle-import:JST_SH_4_SMD")
      (libsource (lib "eagle-import") (part "JST_SH_4"))
    )
    (comp (ref "IMU")
      (value "MPU-9250")
      (footprint "eagle-import:QFN24G-0.4-3X3MM")
      (libsource (lib "eagle-import") (part "MPU-9250"))
    )
    (comp (ref "JACK")
      (value "5.5x2.1mm")
      (footprint "eagle-import:DCJ0303")
      (libsource (lib "eagle-import") (part "DCJ0303"))
    )
    (comp (ref "L1")
      (value "6.8uH")
      (footprint "eagle-import:SRN6045")
      (libsource (lib "eagle-import") (part "INDUCTORBOURNS_SRN6045"))
    )
    (comp (ref "L2")
      (value "6.8uH")
      (footprint "eagle-import:SRN6045")
      (libsource (lib "eagle-import") (part "INDUCTORBOURNS_SRN6045"))
    )
    (comp (ref "L3")
      (value "3.6")
      (footprint "eagle-import:8X8MM_INDUCTOR")
      (libsource (lib "eagle-import") (part "INDUCTOR"))
    )
    (comp (ref "LIPO")
      (value "JST_XH_3-PIN")
      (footprint "eagle-import:JST_XH_3-PIN")
      (libsource (lib "eagle-import") (part "JST_XH_3-PIN"))
    )
    (comp (ref "M1")
      (value "JST_ZH_2")
      (footprint "eagle-import:JST_ZH_2")
      (libsource (lib "eagle-import") (part "JST_ZH_2"))
    )
    (comp (ref "M2")
      (value "JST_ZH_2")
      (footprint "eagle-import:JST_ZH_2")
      (libsource (lib "eagle-import") (part "JST_ZH_2"))
    )
    (comp (ref "M3")
      (value "JST_ZH_2")
      (footprint "eagle-import:JST_ZH_2")
      (libsource (lib "eagle-import") (part "JST_ZH_2"))
    )
    (comp (ref "M4")
      (value "JST_ZH_2")
      (footprint "eagle-import:JST_ZH_2")
      (libsource (lib "eagle-import") (part "JST_ZH_2"))
    )
    (comp (ref "MODE")
      (value "SWITCH-MOMENTARY-2SMD-1101NE")
      (footprint "eagle-import:TACTILE-SWITCH-1101NE")
      (libsource (lib "eagle-import") (part "SWITCH-MOMENTARY-2SMD-1101NE"))
    )
    (comp (ref "PAUSE")
      (value "SWITCH-MOMENTARY-2SMD-1101NE")
      (footprint "eagle-import:TACTILE-SWITCH-1101NE")
      (libsource (lib "eagle-import") (part "SWITCH-MOMENTARY-2SMD-1101NE"))
    )
    (comp (ref "POWER")
      (value "SWITCH-MOMENTARY-2SMD-1101NE")
      (footprint "eagle-import:TACTILE-SWITCH-1101NE")
      (libsource (lib "eagle-import") (part "SWITCH-MOMENTARY-2SMD-1101NE"))
    )
    (comp (ref "PROT")
      (value "S-8261")
      (footprint "eagle-import:SOT-236")
      (libsource (lib "eagle-import") (part "S-8261"))
    )
    (comp (ref "PWR")
      (value "JST_SH_4")
      (footprint "eagle-import:JST_SH_4_SMD")
      (libsource (lib "eagle-import") (part "JST_SH_4"))
    )
    (comp (ref "Q3")
      (value "MOSFET-N")
      (footprint "eagle-import:SO08-TIGHT")
      (libsource (lib "eagle-import") (part "MOSFET-NCHANNEL"))
    )
    (comp (ref "R1")
      (value "47k")
      (footprint "eagle-import:0402-RES")
      (libsource (lib "eagle-import") (part "RESISTOR0402-RES"))
    )
    (comp (ref "R3")
      (value "1k")
      (footprint "eagle-import:0402-RES")
      (libsource (lib "eagle-import") (part "RESISTOR0402-RES"))
    )
    (comp (ref "R4")
      (value "0.1")
      (footprint "eagle-import:0603-RES")
      (libsource (lib "eagle-import") (part "RESISTOR0603"))
    )
    (comp (ref "R5")
      (value "10k")
      (footprint "eagle-import:0402-RES")
      (libsource (lib "eagle-import") (part "RESISTOR0402-RES"))
    )
    (comp (ref "R6")
      (value "10k")
      (footprint "eagle-import:0402-RES")
      (libsource (lib "eagle-import") (part "RESISTOR0402-RES"))
    )
    (comp (ref "R7")
      (value "4.7k")
      (footprint "eagle-import:0402-RES")
      (libsource (lib "eagle-import") (part "RESISTOR0402-RES"))
    )
    (comp (ref "R8")
      (value "10k")
      (footprint "eagle-import:0402-RES")
      (libsource (lib "eagle-import") (part "RESISTOR0402-RES"))
    )
    (comp (ref "R9")
      (value "1K")
      (footprint "eagle-import:0402-RES")
      (libsource (lib "eagle-import") (part "RESISTOR0402-RES"))
    )
    (comp (ref "R10")
      (value "4.7k")
      (footprint "eagle-import:0402-RES")
      (libsource (lib "eagle-import") (part "RESISTOR0402-RES"))
    )
    (comp (ref "R11")
      (value "4.7k")
      (footprint "eagle-import:0402-RES")
      (libsource (lib "eagle-import") (part "RESISTOR0402-RES"))
    )
    (comp (ref "R12")
      (value "4.7k")
      (footprint "eagle-import:0402-RES")
      (libsource (lib "eagle-import") (part "RESISTOR0402-RES"))
    )
    (comp (ref "R13")
      (value "4.7k")
      (footprint "eagle-import:0402-RES")
      (libsource (lib "eagle-import") (part "RESISTOR0402-RES"))
    )
    (comp (ref "R14")
      (value "4.7k")
      (footprint "eagle-import:0402-RES")
      (libsource (lib "eagle-import") (part "RESISTOR0402-RES"))
    )
    (comp (ref "R15")
      (value "1K")
      (footprint "eagle-import:0402-RES")
      (libsource (lib "eagle-import") (part "RESISTOR0402-RES"))
    )
    (comp (ref "R16")
      (value "1K")
      (footprint "eagle-import:0402-RES")
      (libsource (lib "eagle-import") (part "RESISTOR0402-RES"))
    )
    (comp (ref "R17")
      (value "1K")
      (footprint "eagle-import:0402-RES")
      (libsource (lib "eagle-import") (part "RESISTOR0402-RES"))
    )
    (comp (ref "R18")
      (value "1K")
      (footprint "eagle-import:0402-RES")
      (libsource (lib "eagle-import") (part "RESISTOR0402-RES"))
    )
    (comp (ref "R19")
      (value "47k")
      (footprint "eagle-import:0402-RES")
      (libsource (lib "eagle-import") (part "RESISTOR0402-RES"))
    )
    (comp (ref "R20")
      (value "1K")
      (footprint "eagle-import:0402-RES")
      (libsource (lib "eagle-import") (part "RESISTOR0402-RES"))
    )
    (comp (ref "R21")
      (value "261")
      (footprint "eagle-import:0402-RES")
      (libsource (lib "eagle-import") (part "RESISTOR0402-RES"))
    )
    (comp (ref "R22")
      (value "261")
      (footprint "eagle-import:0402-RES")
      (libsource (lib "eagle-import") (part "RESISTOR0402-RES"))
    )
    (comp (ref "R25")
      (value "4.7k")
      (footprint "eagle-import:0402-RES")
      (libsource (lib "eagle-import") (part "RESISTOR0402-RES"))
    )
    (comp (ref "R26")
      (value "1K")
      (footprint "eagle-import:0402-RES")
      (libsource (lib "eagle-import") (part "RESISTOR0402-RES"))
    )
    (comp (ref "R27")
      (value "160")
      (footprint "eagle-import:0402-RES")
      (libsource (lib "eagle-import") (part "RESISTOR0402-RES"))
    )
    (comp (ref "R28")
      (value "160")
      (footprint "eagle-import:0402-RES")
      (libsource (lib "eagle-import") (part "RESISTOR0402-RES"))
    )
    (comp (ref "R29")
      (value "261")
      (footprint "eagle-import:0402-RES")
      (libsource (lib "eagle-import") (part "RESISTOR0402-RES"))
    )
    (comp (ref "R30")
      (value "261")
      (footprint "eagle-import:0402-RES")
      (libsource (lib "eagle-import") (part "RESISTOR0402-RES"))
    )
    (comp (ref "R31")
      (value "261")
      (footprint "eagle-import:0402-RES")
      (libsource (lib "eagle-import") (part "RESISTOR0402-RES"))
    )
    (comp (ref "R32")
      (value "261")
      (footprint "eagle-import:0402-RES")
      (libsource (lib "eagle-import") (part "RESISTOR0402-RES"))
    )
    (comp (ref "R33")
      (value "261")
      (footprint "eagle-import:0402-RES")
      (libsource (lib "eagle-import") (part "RESISTOR0402-RES"))
    )
    (comp (ref "R34")
      (value "160")
      (footprint "eagle-import:0402-RES")
      (libsource (lib "eagle-import") (part "RESISTOR0402-RES"))
    )
    (comp (ref "R35")
      (value "1K")
      (footprint "eagle-import:0402-RES")
      (libsource (lib "eagle-import") (part "RESISTOR0402-RES"))
    )
    (comp (ref "R36")
      (value "4.7k")
      (footprint "eagle-import:0402-RES")
      (libsource (lib "eagle-import") (part "RESISTOR0402-RES"))
    )
    (comp (ref "R37")
      (value "4.7k")
      (footprint "eagle-import:0402-RES")
      (libsource (lib "eagle-import") (part "RESISTOR0402-RES"))
    )
    (comp (ref "R38")
      (value "4.7k")
      (footprint "eagle-import:0402-RES")
      (libsource (lib "eagle-import") (part "RESISTOR0402-RES"))
    )
    (comp (ref "R39")
      (value "4.7k")
      (footprint "eagle-import:0402-RES")
      (libsource (lib "eagle-import") (part "RESISTOR0402-RES"))
    )
    (comp (ref "R40")
      (value "4.7k")
      (footprint "eagle-import:0402-RES")
      (libsource (lib "eagle-import") (part "RESISTOR0402-RES"))
    )
    (comp (ref "R41")
      (value "4.7k")
      (footprint "eagle-import:0402-RES")
      (libsource (lib "eagle-import") (part "RESISTOR0402-RES"))
    )
    (comp (ref "R42")
      (value "4.7k")
      (footprint "eagle-import:0402-RES")
      (libsource (lib "eagle-import") (part "RESISTOR0402-RES"))
    )
    (comp (ref "R43")
      (value "4.7k")
      (footprint "eagle-import:0402-RES")
      (libsource (lib "eagle-import") (part "RESISTOR0402-RES"))
    )
    (comp (ref "R44")
      (value "1k")
      (footprint "eagle-import:0402-RES")
      (libsource (lib "eagle-import") (part "RESISTOR0402-RES"))
    )
    (comp (ref "R45")
      (value "47k")
      (footprint "eagle-import:0402-RES")
      (libsource (lib "eagle-import") (part "RESISTOR0402-RES"))
    )
    (comp (ref "R46")
      (value "1K")
      (footprint "eagle-import:0402-RES")
      (libsource (lib "eagle-import") (part "RESISTOR0402-RES"))
    )
    (comp (ref "R47")
      (value "100k")
      (footprint "eagle-import:0402-RES")
      (libsource (lib "eagle-import") (part "RESISTOR0402-RES"))
    )
    (comp (ref "R48")
      (value "10k")
      (footprint "eagle-import:0402-RES")
      (libsource (lib "eagle-import") (part "RESISTOR0402-RES"))
    )
    (comp (ref "R49")
      (value "65k")
      (footprint "eagle-import:0402-RES")
      (libsource (lib "eagle-import") (part "RESISTOR0402-RES"))
    )
    (comp (ref "R50")
      (value "4.7k")
      (footprint "eagle-import:0402-RES")
      (libsource (lib "eagle-import") (part "RESISTOR0402-RES"))
    )
    (comp (ref "R51")
      (value "4.7k")
      (footprint "eagle-import:0402-RES")
      (libsource (lib "eagle-import") (part "RESISTOR0402-RES"))
    )
    (comp (ref "R52")
      (value "4.7k")
      (footprint "eagle-import:0402-RES")
      (libsource (lib "eagle-import") (part "RESISTOR0402-RES"))
    )
    (comp (ref "R53")
      (value "4.7k")
      (footprint "eagle-import:0402-RES")
      (libsource (lib "eagle-import") (part "RESISTOR0402-RES"))
    )
    (comp (ref "R54")
      (value "4.7k")
      (footprint "eagle-import:0402-RES")
      (libsource (lib "eagle-import") (part "RESISTOR0402-RES"))
    )
    (comp (ref "R55")
      (value "4.7k")
      (footprint "eagle-import:0402-RES")
      (libsource (lib "eagle-import") (part "RESISTOR0402-RES"))
    )
    (comp (ref "R56")
      (value "4.7k")
      (footprint "eagle-import:0402-RES")
      (libsource (lib "eagle-import") (part "RESISTOR0402-RES"))
    )
    (comp (ref "R57")
      (value "4.7k")
      (footprint "eagle-import:0402-RES")
      (libsource (lib "eagle-import") (part "RESISTOR0402-RES"))
    )
    (comp (ref "RED")
      (value "RED")
      (footprint "eagle-import:LED-0603")
      (libsource (lib "eagle-import") (part "SparkFun-LED_LED0603"))
    )
    (comp (ref "RESET")
      (value "SWITCH-MOMENTARY-2SMD-1101NE")
      (footprint "eagle-import:TACTILE-SWITCH-1101NE")
      (libsource (lib "eagle-import") (part "SWITCH-MOMENTARY-2SMD-1101NE"))
    )
    (comp (ref "SPI1.1")
      (value "JST_SH_6")
      (footprint "eagle-import:JST_SH_6")
      (libsource (lib "eagle-import") (part "JST_SH_6"))
    )
    (comp (ref "SPI1.2")
      (value "JST_SH_6")
      (footprint "eagle-import:JST_SH_6")
      (libsource (lib "eagle-import") (part "JST_SH_6"))
    )
    (comp (ref "U$1")
      (value "SERVO_HEADERS_8X")
      (footprint "eagle-import:3X8_0.1__HEADER")
      (libsource (lib "eagle-import") (part "SERVO_HEADERS_8X"))
    )
    (comp (ref "UART0")
      (value "JST_SH_4")
      (footprint "eagle-import:JST_SH_4_SMD")
      (libsource (lib "eagle-import") (part "JST_SH_4"))
    )
    (comp (ref "UART1")
      (value "JST_SH_4")
      (footprint "eagle-import:JST_SH_4_SMD")
      (libsource (lib "eagle-import") (part "JST_SH_4"))
    )
    (comp (ref "UART5")
      (value "JST_SH_4")
      (footprint "eagle-import:JST_SH_4_SMD")
      (libsource (lib "eagle-import") (part "JST_SH_4"))
    )
  )
  (nets
    (net (code "1") (name "3.3V") (class "Default")
      (node (ref "BMP") (pin "2") (pinfunction "VDD_2") (pintype "power_in"))
      (node (ref "BMP") (pin "3") (pinfunction "VDDIO_3") (pintype "power_in"))
      (node (ref "C13") (pin "1") (pinfunction "1_1") (pintype "passive"))
      (node (ref "C16") (pin "1") (pinfunction "1_1") (pintype "passive"))
      (node (ref "C2") (pin "2") (pinfunction "2_2") (pintype "passive"))
      (node (ref "C8") (pin "1") (pinfunction "1_1") (pintype "passive"))
      (node (ref "C9") (pin "2") (pinfunction "2_2") (pintype "passive"))
      (node (ref "DSM2") (pin "P$1") (pinfunction "1_P$1") (pintype "bidirectional"))
      (node (ref "E1") (pin "2") (pinfunction "2_2") (pintype "bidirectional"))
      (node (ref "E2") (pin "2") (pinfunction "2_2") (pintype "bidirectional"))
      (node (ref "E3") (pin "2") (pinfunction "2_2") (pintype "bidirectional"))
      (node (ref "E4") (pin "2") (pinfunction "2_2") (pintype "bidirectional"))
      (node (ref "H1") (pin "20") (pinfunction "VCC_20") (pintype "bidirectional"))
      (node (ref "H2") (pin "20") (pinfunction "VCC_20") (pintype "bidirectional"))
      (node (ref "I2C1") (pin "2") (pinfunction "2_2") (pintype "bidirectional"))
      (node (ref "IMU") (pin "1") (pinfunction "RESV_1") (pintype "bidirectional"))
      (node (ref "IMU") (pin "13") (pinfunction "VDD_13") (pintype "bidirectional"))
      (node (ref "IMU") (pin "22") (pinfunction "NCS_22") (pintype "bidirectional"))
      (node (ref "IMU") (pin "8") (pinfunction "VDDIO_8") (pintype "bidirectional"))
      (node (ref "PWR") (pin "3") (pinfunction "3_3") (pintype "bidirectional"))
      (node (ref "R10") (pin "1") (pinfunction "1_1") (pintype "passive"))
      (node (ref "R11") (pin "2") (pinfunction "2_2") (pintype "passive"))
      (node (ref "R12") (pin "2") (pinfunction "2_2") (pintype "passive"))
      (node (ref "R13") (pin "1") (pinfunction "1_1") (pintype "passive"))
      (node (ref "R15") (pin "2") (pinfunction "2_2") (pintype "passive"))
      (node (ref "R16") (pin "2") (pinfunction "2_2") (pintype "passive"))
      (node (ref "R17") (pin "2") (pinfunction "2_2") (pintype "passive"))
      (node (ref "R18") (pin "2") (pinfunction "2_2") (pintype "passive"))
      (node (ref "R20") (pin "2") (pinfunction "2_2") (pintype "passive"))
      (node (ref "R26") (pin "2") (pinfunction "2_2") (pintype "passive"))
      (node (ref "R35") (pin "2") (pinfunction "2_2") (pintype "passive"))
      (node (ref "R9") (pin "2") (pinfunction "2_2") (pintype "passive"))
      (node (ref "SPI1.1") (pin "2") (pinfunction "2_2") (pintype "bidirectional"))
      (node (ref "SPI1.2") (pin "2") (pinfunction "2_2") (pintype "bidirectional"))
      (node (ref "UART0") (pin "2") (pinfunction "2_2") (pintype "bidirectional"))
      (node (ref "UART1") (pin "2") (pinfunction "2_2") (pintype "bidirectional"))
      (node (ref "UART5") (pin "2") (pinfunction "2_2") (pintype "bidirectional"))
    )
    (net (code "2") (name "5.0V") (class "Default")
      (node (ref "5VREG") (pin "3") (pinfunction "FB_3") (pintype "power_in"))
      (node (ref "C5") (pin "1") (pinfunction "1_1") (pintype "passive"))
      (node (ref "GPS") (pin "5") (pinfunction "5_5") (pintype "bidirectional"))
      (node (ref "L1") (pin "2") (pinfunction "2_2") (pintype "passive"))
      (node (ref "PWR") (pin "4") (pinfunction "4_4") (pintype "bidirectional"))
      (node (ref "R152") (pin "1") (pinfunction "1_1") (pintype "passive"))
      (node (ref "SIP") (pin "Y5") (pinfunction "VIN_AC_0_Y5") (pintype "power_in"))
      (node (ref "SIP") (pin "Y6") (pinfunction "VIN_AC_1_Y6") (pintype "power_in"))
    )
    (net (code "3") (name "AIN0") (class "Default")
      (node (ref "ADC") (pin "3") (pinfunction "3_3") (pintype "bidirectional"))
      (node (ref "R105") (pin "1") (pinfunction "1_1") (pintype "passive"))
    )
    (net (code "4") (name "AIN1") (class "Default")
      (node (ref "ADC") (pin "4") (pinfunction "4_4") (pintype "bidirectional"))
      (node (ref "R106") (pin "1") (pinfunction "1_1") (pintype "passive"))
    )
    (net (code "5") (name "AIN2") (class "Default")
      (node (ref "ADC") (pin "5") (pinfunction "5_5") (pintype "bidirectional"))
      (node (ref "R107") (pin "1") (pinfunction "1_1") (pintype "passive"))
    )
    (net (code "6") (name "AIN3") (class "Default")
      (node (ref "ADC") (pin "6") (pinfunction "6_6") (pintype "bidirectional"))
      (node (ref "R108") (pin "1") (pinfunction "1_1") (pintype "passive"))
    )
    (net (code "7") (name "BATT_MID") (class "Default")
      (node (ref "LIPO") (pin "P$2") (pinfunction "2_P$2") (pintype "passive"))
      (node (ref "R27") (pin "1") (pinfunction "1_1") (pintype "passive"))
      (node (ref "R30") (pin "1") (pinfunction "1_1") (pintype "passive"))
      (node (ref "R44") (pin "1") (pinfunction "1_1") (pintype "passive"))
    )
    (net (code "8") (name "BATT_MINUS") (class "Default")
      (node (ref "BAL") (pin "5") (pinfunction "GND_5") (pintype "bidirectional"))
      (node (ref "BAL") (pin "6") (pinfunction "CB_EN_6") (pintype "bidirectional"))
      (node (ref "C1") (pin "2") (pinfunction "2_2") (pintype "passive"))
      (node (ref "C15") (pin "1") (pinfunction "1_1") (pintype "passive"))
      (node (ref "C18") (pin "1") (pinfunction "1_1") (pintype "passive"))
      (node (ref "C19") (pin "2") (pinfunction "2_2") (pintype "passive"))
      (node (ref "LIPO") (pin "P$3") (pinfunction "3_P$3") (pintype "passive"))
      (node (ref "PROT") (pin "2") (pinfunction "VM_2") (pintype "bidirectional"))
      (node (ref "PROT") (pin "6") (pinfunction "VSS_6") (pintype "bidirectional"))
      (node (ref "Q3") (pin "1") (pinfunction "S_1") (pintype "passive"))
      (node (ref "Q3") (pin "2") (pinfunction "S_2") (pintype "passive"))
      (node (ref "Q3") (pin "3") (pinfunction "S_3") (pintype "passive"))
    )
    (net (code "9") (name "CHG_EN") (class "Default")
      (node (ref "CHGIC") (pin "6") (pinfunction "EN_6") (pintype "bidirectional"))
      (node (ref "R7") (pin "2") (pinfunction "2_2") (pintype "passive"))
      (node (ref "R8") (pin "1") (pinfunction "1_1") (pintype "passive"))
    )
    (net (code "10") (name "DO") (class "Default")
      (node (ref "PROT") (pin "1") (pinfunction "DO_1") (pintype "bidirectional"))
      (node (ref "Q3") (pin "4") (pinfunction "G_4") (pintype "passive"))
    )
    (net (code "11") (name "GND") (class "Default")
      (node (ref "5VREG") (pin "4") (pinfunction "SD_4") (pintype "input"))
      (node (ref "5VREG") (pin "5") (pinfunction "GND_5") (pintype "power_in"))
      (node (ref "5VREG") (pin "6") (pinfunction "GND1_6") (pintype "input"))
      (node (ref "5VREG") (pin "7") (pinfunction "GND2_7") (pintype "passive"))
      (node (ref "5VREG") (pin "8") (pinfunction "GND3_8") (pintype "power_in"))
      (node (ref "6V_REG") (pin "3") (pinfunction "GND_3") (pintype "bidirectional"))
      (node (ref "ADC") (pin "1") (pinfunction "1_1") (pintype "bidirectional"))
      (node (ref "BMP") (pin "7") (pinfunction "GND_7") (pintype "power_in"))
      (node (ref "BOOT") (pin "2") (pinfunction "2_2") (pintype "passive"))
      (node (ref "C$1") (pin "-") (pinfunction "2_-") (pintype "passive"))
      (node (ref "C10") (pin "1") (pinfunction "1_1") (pintype "passive"))
      (node (ref "C11") (pin "-") (pinfunction "-_-") (pintype "passive"))
      (node (ref "C12") (pin "2") (pinfunction "2_2") (pintype "passive"))
      (node (ref "C13") (pin "2") (pinfunction "2_2") (pintype "passive"))
      (node (ref "C16") (pin "2") (pinfunction "2_2") (pintype "passive"))
      (node (ref "C2") (pin "1") (pinfunction "1_1") (pintype "passive"))
      (node (ref "C20") (pin "1") (pinfunction "1_1") (pintype "passive"))
      (node (ref "C21") (pin "1") (pinfunction "1_1") (pintype "passive"))
      (node (ref "C23") (pin "1") (pinfunction "1_1") (pintype "passive"))
      (node (ref "C24") (pin "1") (pinfunction "1_1") (pintype "passive"))
      (node (ref "C25") (pin "2") (pinfunction "2_2") (pintype "passive"))
      (node (ref "C26") (pin "2") (pinfunction "2_2") (pintype "passive"))
      (node (ref "C27") (pin "2") (pinfunction "2_2") (pintype "passive"))
      (node (ref "C28") (pin "2") (pinfunction "2_2") (pintype "passive"))
      (node (ref "C3") (pin "2") (pinfunction "2_2") (pintype "passive"))
      (node (ref "C33") (pin "2") (pinfunction "2_2") (pintype "passive"))
      (node (ref "C34") (pin "1") (pinfunction "1_1") (pintype "passive"))
      (node (ref "C35") (pin "1") (pinfunction "1_1") (pintype "passive"))
      (node (ref "C36") (pin "1") (pinfunction "1_1") (pintype "passive"))
      (node (ref "C37") (pin "2") (pinfunction "2_2") (pintype "passive"))
      (node (ref "C38") (pin "2") (pinfunction "2_2") (pintype "passive"))
      (node (ref "C39") (pin "2") (pinfunction "2_2") (pintype "passive"))
      (node (ref "C4") (pin "1") (pinfunction "1_1") (pintype "passive"))
      (node (ref "C40") (pin "2") (pinfunction "2_2") (pintype "passive"))
      (node (ref "C41") (pin "2") (pinfunction "2_2") (pintype "passive"))
      (node (ref "C45") (pin "2") (pinfunction "2_2") (pintype "passive"))
      (node (ref "C46") (pin "2") (pinfunction "2_2") (pintype "passive"))
      (node (ref "C5") (pin "2") (pinfunction "2_2") (pintype "passive"))
      (node (ref "C6") (pin "2") (pinfunction "2_2") (pintype "passive"))
      (node (ref "C7") (pin "2") (pinfunction "2_2") (pintype "passive"))
      (node (ref "C8") (pin "2") (pinfunction "2_2") (pintype "passive"))
      (node (ref "C9") (pin "1") (pinfunction "1_1") (pintype "passive"))
      (node (ref "CHGIC") (pin "16") (pinfunction "PGND_16") (pintype "bidirectional"))
      (node (ref "CHGIC") (pin "8") (pinfunction "AGND_8") (pintype "bidirectional"))
      (node (ref "D1") (pin "A") (pinfunction "A_A") (pintype "passive"))
      (node (ref "D9") (pin "A") (pinfunction "A_A") (pintype "passive"))
      (node (ref "DSM2") (pin "P$2") (pinfunction "2_P$2") (pintype "bidirectional"))
      (node (ref "E1") (pin "1") (pinfunction "1_1") (pintype "bidirectional"))
      (node (ref "E2") (pin "1") (pinfunction "1_1") (pintype "bidirectional"))
      (node (ref "E3") (pin "1") (pinfunction "1_1") (pintype "bidirectional"))
      (node (ref "E4") (pin "1") (pinfunction "1_1") (pintype "bidirectional"))
      (node (ref "GPS") (pin "2") (pinfunction "2_2") (pintype "bidirectional"))
      (node (ref "GPS") (pin "6") (pinfunction "6_6") (pintype "bidirectional"))
      (node (ref "H1") (pin "10") (pinfunction "PGND2_10") (pintype "bidirectional"))
      (node (ref "H1") (pin "18") (pinfunction "GND_18") (pintype "bidirectional"))
      (node (ref "H1") (pin "3") (pinfunction "PGND1_3") (pintype "bidirectional"))
      (node (ref "H1") (pin "4") (pinfunction "PGND1_4") (pintype "bidirectional"))
      (node (ref "H1") (pin "9") (pinfunction "PGND2_9") (pintype "bidirectional"))
      (node (ref "H2") (pin "10") (pinfunction "PGND2_10") (pintype "bidirectional"))
      (node (ref "H2") (pin "18") (pinfunction "GND_18") (pintype "bidirectional"))
      (node (ref "H2") (pin "3") (pinfunction "PGND1_3") (pintype "bidirectional"))
      (node (ref "H2") (pin "4") (pinfunction "PGND1_4") (pintype "bidirectional"))
      (node (ref "H2") (pin "9") (pinfunction "PGND2_9") (pintype "bidirectional"))
      (node (ref "HOST") (pin "S1") (pinfunction "SH0_S1") (pintype "bidirectional"))
      (node (ref "HOST") (pin "S2") (pinfunction "SH1_S2") (pintype "bidirectional"))
      (node (ref "I2C1") (pin "1") (pinfunction "1_1") (pintype "bidirectional"))
      (node (ref "IMU") (pin "18") (pinfunction "GND_18") (pintype "bidirectional"))
      (node (ref "IMU") (pin "20") (pinfunction "RESV_20") (pintype "bidirectional"))
      (node (ref "IMU") (pin "25") (pinfunction "PAD_25") (pintype "bidirectional"))
      (node (ref "IMU") (pin "9") (pinfunction "AD0/SDO_9") (pintype "bidirectional"))
      (node (ref "JACK") (pin "2") (pinfunction "2_2") (pintype "passive"))
      (node (ref "JACK") (pin "3") (pinfunction "3_3") (pintype "passive"))
      (node (ref "L4") (pin "1") (pinfunction "1_1") (pintype "passive"))
      (node (ref "MODE") (pin "1") (pinfunction "1_1") (pintype "passive"))
      (node (ref "OTG") (pin "5") (pinfunction "G1_5") (pintype "bidirectional"))
      (node (ref "OTG") (pin "M1") (pinfunction "G2_M1") (pintype "bidirectional"))
      (node (ref "OTG") (pin "M2") (pinfunction "G3_M2") (pintype "bidirectional"))
      (node (ref "OTG") (pin "M3") (pinfunction "G4_M3") (pintype "bidirectional"))
      (node (ref "OTG") (pin "M4") (pinfunction "G5_M4") (pintype "bidirectional"))
      (node (ref "P10") (pin "11") (pinfunction "GND3_11") (pintype "bidirectional"))
      (node (ref "P10") (pin "12") (pinfunction "GND4_12") (pintype "bidirectional"))
      (node (ref "P10") (pin "13") (pinfunction "GND5_13") (pintype "bidirectional"))
      (node (ref "P10") (pin "14") (pinfunction "GND6_14") (pintype "bidirectional"))
      (node (ref "P10") (pin "15") (pinfunction "GND7_15") (pintype "bidirectional"))
      (node (ref "P10") (pin "16") (pinfunction "GND8_16") (pintype "bidirectional"))
      (node (ref "P10") (pin "6") (pinfunction "VSS_6") (pintype "bidirectional"))
      (node (ref "P10") (pin "9") (pinfunction "GND_9") (pintype "bidirectional"))
      (node (ref "PAUSE") (pin "1") (pinfunction "1_1") (pintype "passive"))
      (node (ref "POWER") (pin "1") (pinfunction "1_1") (pintype "passive"))
      (node (ref "PWR") (pin "1") (pinfunction "1_1") (pintype "bidirectional"))
      (node (ref "PWR") (pin "2") (pinfunction "2_2") (pintype "bidirectional"))
      (node (ref "Q3") (pin "5") (pinfunction "D_5") (pintype "passive"))
      (node (ref "Q3") (pin "6") (pinfunction "D_6") (pintype "passive"))
      (node (ref "Q3") (pin "7") (pinfunction "D_7") (pintype "passive"))
      (node (ref "Q3") (pin "8") (pinfunction "D_8") (pintype "passive"))
      (node (ref "R110") (pin "2") (pinfunction "2_2") (pintype "passive"))
      (node (ref "R113") (pin "1") (pinfunction "1_1") (pintype "passive"))
      (node (ref "R115") (pin "1") (pinfunction "1_1") (pintype "passive"))
      (node (ref "R125") (pin "1") (pinfunction "1_1") (pintype "passive"))
      (node (ref "R127") (pin "1") (pinfunction "1_1") (pintype "passive"))
      (node (ref "R129") (pin "1") (pinfunction "1_1") (pintype "passive"))
      (node (ref "R131") (pin "1") (pinfunction "1_1") (pintype "passive"))
      (node (ref "R133") (pin "1") (pinfunction "1_1") (pintype "passive"))
      (node (ref "R135") (pin "1") (pinfunction "1_1") (pintype "passive"))
      (node (ref "R137") (pin "1") (pinfunction "1_1") (pintype "passive"))
      (node (ref "R139") (pin "1") (pinfunction "1_1") (pintype "passive"))
      (node (ref "R14") (pin "2") (pinfunction "2_2") (pintype "passive"))
      (node (ref "R143") (pin "1") (pinfunction "1_1") (pintype "passive"))
      (node (ref "R150") (pin "2") (pinfunction "2_2") (pintype "passive"))
      (node (ref "R151") (pin "1") (pinfunction "1_1") (pintype "passive"))
      (node (ref "R158") (pin "2") (pinfunction "2_2") (pintype "passive"))
      (node (ref "R21") (pin "2") (pinfunction "2_2") (pintype "passive"))
      (node (ref "R22") (pin "2") (pinfunction "2_2") (pintype "passive"))
      (node (ref "R24") (pin "2") (pinfunction "2_2") (pintype "passive"))
      (node (ref "R25") (pin "2") (pinfunction "2_2") (pintype "passive"))
      (node (ref "R29") (pin "2") (pinfunction "2_2") (pintype "passive"))
      (node (ref "R31") (pin "2") (pinfunction "2_2") (pintype "passive"))
      (node (ref "R32") (pin "2") (pinfunction "2_2") (pintype "passive"))
      (node (ref "R33") (pin "2") (pinfunction "2_2") (pintype "passive"))
      (node (ref "R46") (pin "1") (pinfunction "1_1") (pintype "passive"))
      (node (ref "R47") (pin "1") (pinfunction "1_1") (pintype "passive"))
      (node (ref "R48") (pin "1") (pinfunction "1_1") (pintype "passive"))
      (node (ref "R50") (pin "2") (pinfunction "2_2") (pintype "passive"))
      (node (ref "R51") (pin "2") (pinfunction "2_2") (pintype "passive"))
      (node (ref "R52") (pin "2") (pinfunction "2_2") (pintype "passive"))
      (node (ref "R53") (pin "2") (pinfunction "2_2") (pintype "passive"))
      (node (ref "R54") (pin "1") (pinfunction "1_1") (pintype "passive"))
      (node (ref "R55") (pin "1") (pinfunction "1_1") (pintype "passive"))
      (node (ref "R56") (pin "1") (pinfunction "1_1") (pintype "passive"))
      (node (ref "R57") (pin "1") (pinfunction "1_1") (pintype "passive"))
      (node (ref "R59") (pin "1") (pinfunction "1_1") (pintype "passive"))
      (node (ref "R6") (pin "1") (pinfunction "1_1") (pintype "passive"))
      (node (ref "R61") (pin "1") (pinfunction "1_1") (pintype "passive"))
      (node (ref "R62") (pin "1") (pinfunction "1_1") (pintype "passive"))
      (node (ref "R63") (pin "1") (pinfunction "1_1") (pintype "passive"))
      (node (ref "R64") (pin "1") (pinfunction "1_1") (pintype "passive"))
      (node (ref "R8") (pin "2") (pinfunction "2_2") (pintype "passive"))
      (node (ref "RESET") (pin "1") (pinfunction "1_1") (pintype "passive"))
      (node (ref "SIP") (pin "A1") (pinfunction "DGND1_A1") (pintype "bidirectional"))
      (node (ref "SIP") (pin "A18") (pinfunction "DGND2_A18") (pintype "bidirectional"))
      (node (ref "SIP") (pin "E19") (pinfunction "DGND3_E19") (pintype "bidirectional"))
      (node (ref "SIP") (pin "E20") (pinfunction "DGND4_E20") (pintype "bidirectional"))
      (node (ref "SIP") (pin "F19") (pinfunction "DGND6_F19") (pintype "bidirectional"))
      (node (ref "SIP") (pin "F8") (pinfunction "DGND5_F8") (pintype "bidirectional"))
      (node (ref "SIP") (pin "G11") (pinfunction "DGND9_G11") (pintype "bidirectional"))
      (node (ref "SIP") (pin "G12") (pinfunction "DGND10_G12") (pintype "bidirectional"))
      (node (ref "SIP") (pin "G19") (pinfunction "DGND11_G19") (pintype "bidirectional"))
      (node (ref "SIP") (pin "G8") (pinfunction "DGND7_G8") (pintype "bidirectional"))
      (node (ref "SIP") (pin "G9") (pinfunction "DGND8_G9") (pintype "bidirectional"))
      (node (ref "SIP") (pin "H10") (pinfunction "DGND16_H10") (pintype "bidirectional"))
      (node (ref "SIP") (pin "H12") (pinfunction "DGND17_H12") (pintype "bidirectional"))
      (node (ref "SIP") (pin "H19") (pinfunction "DGND18_H19") (pintype "bidirectional"))
      (node (ref "SIP") (pin "H6") (pinfunction "DGND12_H6") (pintype "bidirectional"))
      (node (ref "SIP") (pin "H7") (pinfunction "DGND13_H7") (pintype "bidirectional"))
      (node (ref "SIP") (pin "H8") (pinfunction "DGND14_H8") (pintype "bidirectional"))
      (node (ref "SIP") (pin "H9") (pinfunction "DGND15_H9") (pintype "bidirectional"))
      (node (ref "SIP") (pin "J10") (pinfunction "DGND23_J10") (pintype "bidirectional"))
      (node (ref "SIP") (pin "J11") (pinfunction "DGND24_J11") (pintype "bidirectional"))
      (node (ref "SIP") (pin "J19") (pinfunction "DGND25_J19") (pintype "bidirectional"))
      (node (ref "SIP") (pin "J20") (pinfunction "DGND26_J20") (pintype "bidirectional"))
      (node (ref "SIP") (pin "J6") (pinfunction "DGND19_J6") (pintype "bidirectional"))
      (node (ref "SIP") (pin "J7") (pinfunction "DGND20_J7") (pintype "bidirectional"))
      (node (ref "SIP") (pin "J8") (pinfunction "DGND21_J8") (pintype "bidirectional"))
      (node (ref "SIP") (pin "J9") (pinfunction "DGND22_J9") (pintype "bidirectional"))
      (node (ref "SIP") (pin "K10") (pinfunction "DGND29_K10") (pintype "bidirectional"))
      (node (ref "SIP") (pin "K11") (pinfunction "DGND30_K11") (pintype "bidirectional"))
      (node (ref "SIP") (pin "K19") (pinfunction "DGND31_K19") (pintype "bidirectional"))
      (node (ref "SIP") (pin "K7") (pinfunction "DGND27_K7") (pintype "bidirectional"))
      (node (ref "SIP") (pin "K9") (pinfunction "DGND28_K9") (pintype "bidirectional"))
      (node (ref "SIP") (pin "L10") (pinfunction "DGND32_L10") (pintype "bidirectional"))
      (node (ref "SIP") (pin "L11") (pinfunction "DGND33_L11") (pintype "bidirectional"))
      (node (ref "SIP") (pin "L12") (pinfunction "DGND34_L12") (pintype "bidirectional"))
      (node (ref "SIP") (pin "L13") (pinfunction "DGND35_L13") (pintype "bidirectional"))
      (node (ref "SIP") (pin "L19") (pinfunction "DGND36_L19") (pintype "bidirectional"))
      (node (ref "SIP") (pin "M10") (pinfunction "DGND42_M10") (pintype "bidirectional"))
      (node (ref "SIP") (pin "M12") (pinfunction "DGND43_M12") (pintype "bidirectional"))
      (node (ref "SIP") (pin "M14") (pinfunction "DGND44_M14") (pintype "bidirectional"))
      (node (ref "SIP") (pin "M19") (pinfunction "DGND45_M19") (pintype "bidirectional"))
      (node (ref "SIP") (pin "M6") (pinfunction "DGND38_M6") (pintype "bidirectional"))
      (node (ref "SIP") (pin "M7") (pinfunction "DGND39_M7") (pintype "bidirectional"))
      (node (ref "SIP") (pin "M8") (pinfunction "DGND40_M8") (pintype "bidirectional"))
      (node (ref "SIP") (pin "M9") (pinfunction "DGND41_M9") (pintype "bidirectional"))
      (node (ref "SIP") (pin "N10") (pinfunction "DGND47_N10") (pintype "bidirectional"))
      (node (ref "SIP") (pin "N11") (pinfunction "DGND48_N11") (pintype "bidirectional"))
      (node (ref "SIP") (pin "N14") (pinfunction "DGND49_N14") (pintype "bidirectional"))
      (node (ref "SIP") (pin "N19") (pinfunction "DGND50_N19") (pintype "bidirectional"))
      (node (ref "SIP") (pin "N20") (pinfunction "DGND51_N20") (pintype "bidirectional"))
      (node (ref "SIP") (pin "N7") (pinfunction "DGND46_N7") (pintype "bidirectional"))
      (node (ref "SIP") (pin "P19") (pinfunction "DGND52_P19") (pintype "bidirectional"))
      (node (ref "SIP") (pin "P20") (pinfunction "DGND53_P20") (pintype "bidirectional"))
      (node (ref "SIP") (pin "R19") (pinfunction "DGND54_R19") (pintype "bidirectional"))
      (node (ref "SIP") (pin "R20") (pinfunction "DGND55_R20") (pintype "bidirectional"))
      (node (ref "SIP") (pin "T19") (pinfunction "DGND56_T19") (pintype "bidirectional"))
      (node (ref "SIP") (pin "T20") (pinfunction "DGND57_T20") (pintype "bidirectional"))
      (node (ref "SIP") (pin "U19") (pinfunction "DGND58_U19") (pintype "bidirectional"))
      (node (ref "SIP") (pin "V1") (pinfunction "DGND59_V1") (pintype "bidirectional"))
      (node (ref "SIP") (pin "V18") (pinfunction "DGND60_V18") (pintype "bidirectional"))
      (node (ref "SIP") (pin "V19") (pinfunction "DGND61_V19") (pintype "bidirectional"))
      (node (ref "SIP") (pin "W10") (pinfunction "DGND70_W10") (pintype "bidirectional"))
      (node (ref "SIP") (pin "W11") (pinfunction "DGND71_W11") (pintype "bidirectional"))
      (node (ref "SIP") (pin "W12") (pinfunction "DGND72_W12") (pintype "bidirectional"))
      (node (ref "SIP") (pin "W13") (pinfunction "DGND73_W13") (pintype "bidirectional"))
      (node (ref "SIP") (pin "W14") (pinfunction "DGND74_W14") (pintype "bidirectional"))
      (node (ref "SIP") (pin "W15") (pinfunction "DGND75_W15") (pintype "bidirectional"))
      (node (ref "SIP") (pin "W16") (pinfunction "DGND76_W16") (pintype "bidirectional"))
      (node (ref "SIP") (pin "W17") (pinfunction "DGND77_W17") (pintype "bidirectional"))
      (node (ref "SIP") (pin "W18") (pinfunction "DGND78_W18") (pintype "bidirectional"))
      (node (ref "SIP") (pin "W19") (pinfunction "DGND79_W19") (pintype "bidirectional"))
      (node (ref "SIP") (pin "W2") (pinfunction "DGND62_W2") (pintype "bidirectional"))
      (node (ref "SIP") (pin "W20") (pinfunction "DGND80_W20") (pintype "bidirectional"))
      (node (ref "SIP") (pin "W3") (pinfunction "DGND63_W3") (pintype "bidirectional"))
      (node (ref "SIP") (pin "W5") (pinfunction "DGND65_W5") (pintype "bidirectional"))
      (node (ref "SIP") (pin "W6") (pinfunction "DGND66_W6") (pintype "bidirectional"))
      (node (ref "SIP") (pin "W7") (pinfunction "DGND67_W7") (pintype "bidirectional"))
      (node (ref "SIP") (pin "W8") (pinfunction "DGND68_W8") (pintype "bidirectional"))
      (node (ref "SIP") (pin "W9") (pinfunction "DGND69_W9") (pintype "bidirectional"))
      (node (ref "SIP") (pin "Y10") (pinfunction "DGND83_Y10") (pintype "bidirectional"))
      (node (ref "SIP") (pin "Y12") (pinfunction "DGND84_Y12") (pintype "bidirectional"))
      (node (ref "SIP") (pin "Y15") (pinfunction "DGND85_Y15") (pintype "bidirectional"))
      (node (ref "SIP") (pin "Y18") (pinfunction "DGND86_Y18") (pintype "bidirectional"))
      (node (ref "SIP") (pin "Y7") (pinfunction "DGND82_Y7") (pintype "bidirectional"))
      (node (ref "SPI1.1") (pin "1") (pinfunction "1_1") (pintype "bidirectional"))
      (node (ref "SPI1.2") (pin "1") (pinfunction "1_1") (pintype "bidirectional"))
      (node (ref "TP12") (pin "TP") (pinfunction "TP_TP") (pintype "input"))
      (node (ref "U$1") (pin "P$13") (pinfunction "GND_P$13") (pintype "bidirectional"))
      (node (ref "U$1") (pin "P$14") (pinfunction "GND_P$14") (pintype "bidirectional"))
      (node (ref "U$1") (pin "P$15") (pinfunction "GND_P$15") (pintype "bidirectional"))
      (node (ref "U$1") (pin "P$16") (pinfunction "GND_P$16") (pintype "bidirectional"))
      (node (ref "U$1") (pin "P$17") (pinfunction "GND_P$17") (pintype "bidirectional"))
      (node (ref "U$1") (pin "P$18") (pinfunction "GND_P$18") (pintype "bidirectional"))
      (node (ref "U$1") (pin "P$23") (pinfunction "GND_P$23") (pintype "bidirectional"))
      (node (ref "U$1") (pin "P$24") (pinfunction "GND_P$24") (pintype "bidirectional"))
      (node (ref "U1") (pin "4") (pinfunction "GND_4") (pintype "power_in"))
      (node (ref "U4") (pin "4") (pinfunction "GND_4") (pintype "power_in"))
      (node (ref "U5") (pin "2") (pinfunction "VSS_2") (pintype "passive"))
      (node (ref "U6") (pin "3") (pinfunction "GND_3") (pintype "power_in"))
      (node (ref "U7") (pin "1") (pinfunction "GND_1") (pintype "power_in"))
      (node (ref "U8") (pin "C4") (pinfunction "VSSQ4_C4") (pintype "bidirectional"))
      (node (ref "U8") (pin "E7") (pinfunction "VSS2_E7") (pintype "bidirectional"))
      (node (ref "U8") (pin "G5") (pinfunction "VSS1_G5") (pintype "bidirectional"))
      (node (ref "U8") (pin "H10") (pinfunction "VSS3_H10") (pintype "bidirectional"))
      (node (ref "U8") (pin "K8") (pinfunction "VSS4_K8") (pintype "bidirectional"))
      (node (ref "U8") (pin "N2") (pinfunction "VSSQ1_N2") (pintype "bidirectional"))
      (node (ref "U8") (pin "N5") (pinfunction "VSS5_N5") (pintype "bidirectional"))
      (node (ref "U8") (pin "P4") (pinfunction "VSSQ3_P4") (pintype "bidirectional"))
      (node (ref "U8") (pin "P6") (pinfunction "VSSQ2_P6") (pintype "bidirectional"))
      (node (ref "UART0") (pin "1") (pinfunction "1_1") (pintype "bidirectional"))
      (node (ref "UART1") (pin "1") (pinfunction "1_1") (pintype "bidirectional"))
      (node (ref "UART5") (pin "1") (pinfunction "1_1") (pintype "bidirectional"))
    )
    (net (code "12") (name "GNDA_ADC") (class "Default")
      (node (ref "C42") (pin "2") (pinfunction "2_2") (pintype "passive"))
      (node (ref "C43") (pin "2") (pinfunction "2_2") (pintype "passive"))
      (node (ref "C44") (pin "2") (pinfunction "2_2") (pintype "passive"))
      (node (ref "SIP") (pin "A6") (pinfunction "VSSA_ADC_0_A6") (pintype "bidirectional"))
      (node (ref "SIP") (pin "A9") (pinfunction "VSSA_ADC_1_A9") (pintype "bidirectional"))
      (node (ref "SIP") (pin "E8") (pinfunction "VSSA_ADC_2_E8") (pintype "bidirectional"))
    )
    (net (code "13") (name "I2C0_SCL") (class "Default")
      (node (ref "R23") (pin "1") (pinfunction "1_1") (pintype "passive"))
      (node (ref "SIP") (pin "C16") (pinfunction "I2C0_SCL_C16") (pintype "bidirectional"))
      (node (ref "SIP") (pin "C20") (pinfunction "PMIC_I2C_SCL_C20") (pintype "bidirectional"))
      (node (ref "U5") (pin "1") (pinfunction "SCL_1") (pintype "input"))
    )
    (net (code "14") (name "I2C0_SDA") (class "Default")
      (node (ref "R2") (pin "1") (pinfunction "1_1") (pintype "passive"))
      (node (ref "SIP") (pin "C17") (pinfunction "I2C0_SDA_C17") (pintype "bidirectional"))
      (node (ref "SIP") (pin "C19") (pinfunction "PMIC_I2C_SDA_C19") (pintype "bidirectional"))
      (node (ref "U5") (pin "3") (pinfunction "SDA_3") (pintype "bidirectional"))
    )
    (net (code "15") (name "I2C1_SCL") (class "Default")
      (node (ref "I2C1") (pin "3") (pinfunction "3_3") (pintype "bidirectional"))
      (node (ref "R12") (pin "1") (pinfunction "1_1") (pintype "passive"))
      (node (ref "R75") (pin "1") (pinfunction "1_1") (pintype "passive"))
    )
    (net (code "16") (name "I2C1_SDA") (class "Default")
      (node (ref "I2C1") (pin "4") (pinfunction "4_4") (pintype "bidirectional"))
      (node (ref "R13") (pin "2") (pinfunction "2_2") (pintype "passive"))
      (node (ref "R74") (pin "1") (pinfunction "1_1") (pintype "passive"))
    )
    (net (code "17") (name "I2C2_SCL") (class "Default")
      (node (ref "BMP") (pin "5") (pinfunction "SCL_5") (pintype "input"))
      (node (ref "IMU") (pin "23") (pinfunction "SCL/SCLK_23") (pintype "bidirectional"))
      (node (ref "R11") (pin "1") (pinfunction "1_1") (pintype "passive"))
      (node (ref "R81") (pin "1") (pinfunction "1_1") (pintype "passive"))
    )
    (net (code "18") (name "I2C2_SDA") (class "Default")
      (node (ref "BMP") (pin "6") (pinfunction "SDA_6") (pintype "bidirectional"))
      (node (ref "IMU") (pin "24") (pinfunction "SDA/SDI_24") (pintype "bidirectional"))
      (node (ref "R10") (pin "2") (pinfunction "2_2") (pintype "passive"))
      (node (ref "R80") (pin "1") (pinfunction "1_1") (pintype "passive"))
    )
    (net (code "19") (name "IMU_INT") (class "Default")
      (node (ref "IMU") (pin "12") (pinfunction "INT_12") (pintype "bidirectional"))
      (node (ref "SIP") (pin "A14") (pinfunction "GPIO3_21_A14_A14") (pintype "bidirectional"))
    )
    (net (code "20") (name "LDO_PGOOD") (class "Default")
      (node (ref "SIP") (pin "B20") (pinfunction "PMIC_OUT_LDO_PGOOD_B20") (pintype "output"))
      (node (ref "SIP") (pin "B5") (pinfunction "RTC_PWRONRSTN_B5") (pintype "bidirectional"))
    )
    (net (code "21") (name "LED_1") (class "Default")
      (node (ref "D4") (pin "A") (pinfunction "A_A") (pintype "passive"))
      (node (ref "SIP") (pin "U12") (pinfunction "GPIO0_27_U12_U12") (pintype "bidirectional"))
    )
    (net (code "22") (name "LED_2") (class "Default")
      (node (ref "D5") (pin "A") (pinfunction "A_A") (pintype "passive"))
      (node (ref "R143") (pin "2") (pinfunction "2_2") (pintype "passive"))
      (node (ref "SIP") (pin "T5") (pinfunction "LCD_DATA15_T5_T5") (pintype "bidirectional"))
    )
    (net (code "23") (name "LED_3") (class "Default")
      (node (ref "D6") (pin "A") (pinfunction "A_A") (pintype "passive"))
      (node (ref "SIP") (pin "V6") (pinfunction "GPIO1_29_V6_V6") (pintype "bidirectional"))
    )
    (net (code "24") (name "LED_4") (class "Default")
      (node (ref "D7") (pin "A") (pinfunction "A_A") (pintype "passive"))
      (node (ref "SIP") (pin "T11") (pinfunction "GPIO0_26_T11_T11") (pintype "bidirectional"))
    )
    (net (code "25") (name "LED_GRN") (class "Default")
      (node (ref "GRN") (pin "A") (pinfunction "A_A") (pintype "passive"))
      (node (ref "SIP") (pin "T7") (pinfunction "TIMER7_T7_T7") (pintype "bidirectional"))
    )
    (net (code "26") (name "LED_RED") (class "Default")
      (node (ref "RED") (pin "A") (pinfunction "A_A") (pintype "passive"))
      (node (ref "SIP") (pin "R7") (pinfunction "TIMER4_R7_R7") (pintype "bidirectional"))
    )
    (net (code "27") (name "MDIR_1A") (class "Default")
      (node (ref "H1") (pin "21") (pinfunction "AIN1_21") (pintype "bidirectional"))
      (node (ref "SIP") (pin "C12") (pinfunction "SPI1_CS0_C12_C12") (pintype "bidirectional"))
    )
    (net (code "28") (name "MDIR_1B") (class "Default")
      (node (ref "H1") (pin "22") (pinfunction "AIN2_22") (pintype "bidirectional"))
      (node (ref "SIP") (pin "U17") (pinfunction "UART4_TXD_U17_U17") (pintype "bidirectional"))
    )
    (net (code "29") (name "MDIR_2A") (class "Default")
      (node (ref "H1") (pin "17") (pinfunction "BIN1_17") (pintype "bidirectional"))
      (node (ref "SIP") (pin "R13") (pinfunction "GPIO1_16_R13_R13") (pintype "bidirectional"))
    )
    (net (code "30") (name "MDIR_2B") (class "Default")
      (node (ref "H1") (pin "16") (pinfunction "BIN2_16") (pintype "bidirectional"))
      (node (ref "R140") (pin "1") (pinfunction "1_1") (pintype "passive"))
      (node (ref "SIP") (pin "V4") (pinfunction "LCD_DATA14_V4_V4") (pintype "bidirectional"))
    )
    (net (code "31") (name "MDIR_3A") (class "Default")
      (node (ref "H2") (pin "21") (pinfunction "AIN1_21") (pintype "bidirectional"))
      (node (ref "R118") (pin "1") (pinfunction "1_1") (pintype "passive"))
      (node (ref "SIP") (pin "R4") (pinfunction "LCD_DATA3_R4_R4") (pintype "bidirectional"))
    )
    (net (code "32") (name "MDIR_3B") (class "Default")
      (node (ref "H2") (pin "22") (pinfunction "AIN2_22") (pintype "bidirectional"))
      (node (ref "R116") (pin "1") (pinfunction "1_1") (pintype "passive"))
      (node (ref "R148") (pin "1") (pinfunction "1_1") (pintype "passive"))
      (node (ref "SIP") (pin "R3") (pinfunction "LCD_DATA2_R3_R3") (pintype "bidirectional"))
    )
    (net (code "33") (name "MDIR_4A") (class "Default")
      (node (ref "H2") (pin "17") (pinfunction "BIN1_17") (pintype "bidirectional"))
      (node (ref "R113") (pin "2") (pinfunction "2_2") (pintype "passive"))
      (node (ref "SIP") (pin "R1") (pinfunction "LCD_DATA0_R1_R1") (pintype "bidirectional"))
    )
    (net (code "34") (name "MDIR_4B") (class "Default")
      (node (ref "H2") (pin "16") (pinfunction "BIN2_16") (pintype "bidirectional"))
      (node (ref "R115") (pin "2") (pinfunction "2_2") (pintype "passive"))
      (node (ref "SIP") (pin "R2") (pinfunction "LCD_DATA1_R2_R2") (pintype "bidirectional"))
    )
    (net (code "35") (name "MODE_BTN") (class "Default")
      (node (ref "MODE") (pin "2") (pinfunction "2_2") (pintype "passive"))
      (node (ref "SIP") (pin "U6") (pinfunction "TIMER6_U6_U6") (pintype "bidirectional"))
    )
    (net (code "36") (name "MOT_STBY") (class "Default")
      (node (ref "H1") (pin "19") (pinfunction "STBY_19") (pintype "bidirectional"))
      (node (ref "H2") (pin "19") (pinfunction "STBY_19") (pintype "bidirectional"))
      (node (ref "SIP") (pin "D14") (pinfunction "GPIO0_20_D14_D14") (pintype "bidirectional"))
    )
    (net (code "37") (name "Net-(5VREG-OUT)") (class "Default")
      (node (ref "5VREG") (pin "2") (pinfunction "OUT_2") (pintype "power_in"))
      (node (ref "D1") (pin "C") (pinfunction "C_C") (pintype "passive"))
      (node (ref "L1") (pin "1") (pinfunction "1_1") (pintype "passive"))
    )
    (net (code "38") (name "Net-(5VREG-VIN)") (class "Default")
      (node (ref "5VREG") (pin "1") (pinfunction "VIN_1") (pintype "input"))
      (node (ref "C3") (pin "1") (pinfunction "1_1") (pintype "passive"))
      (node (ref "D2") (pin "C") (pinfunction "C_C") (pintype "passive"))
      (node (ref "D3") (pin "C") (pinfunction "C_C") (pintype "passive"))
    )
    (net (code "39") (name "Net-(6V_REG-BS)") (class "Default")
      (node (ref "6V_REG") (pin "2") (pinfunction "BS_2") (pintype "bidirectional"))
      (node (ref "C22") (pin "1") (pinfunction "1_1") (pintype "passive"))
    )
    (net (code "40") (name "Net-(6V_REG-COMP)") (class "Default")
      (node (ref "6V_REG") (pin "5") (pinfunction "COMP_5") (pintype "bidirectional"))
      (node (ref "R45") (pin "2") (pinfunction "2_2") (pintype "passive"))
    )
    (net (code "41") (name "Net-(6V_REG-FB)") (class "Default")
      (node (ref "6V_REG") (pin "6") (pinfunction "FB_6") (pintype "bidirectional"))
      (node (ref "R48") (pin "2") (pinfunction "2_2") (pintype "passive"))
      (node (ref "R49") (pin "1") (pinfunction "1_1") (pintype "passive"))
    )
    (net (code "42") (name "Net-(6V_REG-FSW)") (class "Default")
      (node (ref "6V_REG") (pin "4") (pinfunction "FSW_4") (pintype "bidirectional"))
      (node (ref "R47") (pin "2") (pinfunction "2_2") (pintype "passive"))
    )
    (net (code "43") (name "Net-(6V_REG-LX)") (class "Default")
      (node (ref "6V_REG") (pin "1") (pinfunction "LX_1") (pintype "bidirectional"))
      (node (ref "C22") (pin "2") (pinfunction "2_2") (pintype "passive"))
      (node (ref "D9") (pin "C") (pinfunction "C_C") (pintype "passive"))
      (node (ref "L3") (pin "1") (pinfunction "1_1") (pintype "passive"))
    )
    (net (code "44") (name "Net-(6V_REG-SS)") (class "Default")
      (node (ref "6V_REG") (pin "7") (pinfunction "SS_7") (pintype "bidirectional"))
      (node (ref "C21") (pin "2") (pinfunction "2_2") (pintype "passive"))
    )
    (net (code "45") (name "Net-(BAL-CD)") (class "Default")
      (node (ref "BAL") (pin "4") (pinfunction "CD_4") (pintype "bidirectional"))
      (node (ref "C19") (pin "1") (pinfunction "1_1") (pintype "passive"))
    )
    (net (code "46") (name "Net-(BAL-OUT)") (class "Default")
      (node (ref "BAL") (pin "8") (pinfunction "OUT_8") (pintype "bidirectional"))
      (node (ref "R7") (pin "1") (pinfunction "1_1") (pintype "passive"))
    )
    (net (code "47") (name "Net-(BAL-VC1)") (class "Default")
      (node (ref "BAL") (pin "2") (pinfunction "VC1_2") (pintype "bidirectional"))
      (node (ref "C17") (pin "1") (pinfunction "1_1") (pintype "passive"))
      (node (ref "C18") (pin "2") (pinfunction "2_2") (pintype "passive"))
      (node (ref "R30") (pin "2") (pinfunction "2_2") (pintype "passive"))
    )
    (net (code "48") (name "Net-(BAL-VC1_CB)") (class "Default")
      (node (ref "BAL") (pin "3") (pinfunction "VC1_CB_3") (pintype "bidirectional"))
      (node (ref "R27") (pin "2") (pinfunction "2_2") (pintype "passive"))
    )
    (net (code "49") (name "Net-(BAL-VC2)") (class "Default")
      (node (ref "BAL") (pin "1") (pinfunction "VC2_1") (pintype "bidirectional"))
      (node (ref "C17") (pin "2") (pinfunction "2_2") (pintype "passive"))
      (node (ref "R28") (pin "2") (pinfunction "2_2") (pintype "passive"))
    )
    (net (code "50") (name "Net-(BAL-VDD)") (class "Default")
      (node (ref "BAL") (pin "7") (pinfunction "VDD_7") (pintype "bidirectional"))
      (node (ref "C1") (pin "1") (pinfunction "1_1") (pintype "passive"))
      (node (ref "R34") (pin "2") (pinfunction "2_2") (pintype "passive"))
    )
    (net (code "51") (name "Net-(BOOT-Pad1)") (class "Default")
      (node (ref "BOOT") (pin "1") (pinfunction "1_1") (pintype "passive"))
      (node (ref "R148") (pin "2") (pinfunction "2_2") (pintype "passive"))
    )
    (net (code "52") (name "Net-(C$1-1)") (class "Default")
      (node (ref "C$1") (pin "+") (pinfunction "1_+") (pintype "passive"))
      (node (ref "R152") (pin "2") (pinfunction "2_2") (pintype "passive"))
      (node (ref "R153") (pin "2") (pinfunction "2_2") (pintype "passive"))
      (node (ref "U7") (pin "2") (pinfunction "IN_2_2") (pintype "input"))
      (node (ref "U7") (pin "3") (pinfunction "IN_3") (pintype "input"))
    )
    (net (code "53") (name "Net-(C23-Pad2)") (class "Default")
      (node (ref "C23") (pin "2") (pinfunction "2_2") (pintype "passive"))
      (node (ref "L3") (pin "2") (pinfunction "2_2") (pintype "passive"))
      (node (ref "R49") (pin "2") (pinfunction "2_2") (pintype "passive"))
      (node (ref "U$1") (pin "P$10") (pinfunction "PWR_P$10") (pintype "bidirectional"))
      (node (ref "U$1") (pin "P$11") (pinfunction "PWR_P$11") (pintype "bidirectional"))
      (node (ref "U$1") (pin "P$12") (pinfunction "PWR_P$12") (pintype "bidirectional"))
      (node (ref "U$1") (pin "P$21") (pinfunction "PWR_P$21") (pintype "bidirectional"))
      (node (ref "U$1") (pin "P$22") (pinfunction "PWR_P$22") (pintype "bidirectional"))
      (node (ref "U$1") (pin "P$7") (pinfunction "PWR_P$7") (pintype "bidirectional"))
      (node (ref "U$1") (pin "P$8") (pinfunction "PWR_P$8") (pintype "bidirectional"))
      (node (ref "U$1") (pin "P$9") (pinfunction "PWR_P$9") (pintype "bidirectional"))
    )
    (net (code "54") (name "Net-(C24-Pad2)") (class "Default")
      (node (ref "C24") (pin "2") (pinfunction "2_2") (pintype "passive"))
      (node (ref "R45") (pin "1") (pinfunction "1_1") (pintype "passive"))
    )
    (net (code "55") (name "Net-(CHG-PadC)") (class "Default")
      (node (ref "CHG") (pin "C") (pinfunction "C_C") (pintype "passive"))
      (node (ref "R3") (pin "2") (pinfunction "2_2") (pintype "passive"))
    )
    (net (code "56") (name "Net-(CHGIC-BST)") (class "Default")
      (node (ref "C14") (pin "1") (pinfunction "1_1") (pintype "passive"))
      (node (ref "CHGIC") (pin "15") (pinfunction "BST_15") (pintype "bidirectional"))
    )
    (net (code "57") (name "Net-(CHGIC-CHGOK)") (class "Default")
      (node (ref "CHGIC") (pin "11") (pinfunction "CHGOK_11") (pintype "bidirectional"))
      (node (ref "R3") (pin "1") (pinfunction "1_1") (pintype "passive"))
    )
    (net (code "58") (name "Net-(CHGIC-CSP)") (class "Default")
      (node (ref "CHGIC") (pin "10") (pinfunction "CSP_10") (pintype "bidirectional"))
      (node (ref "L2") (pin "2") (pinfunction "2_2") (pintype "passive"))
      (node (ref "R4") (pin "2") (pinfunction "2_2") (pintype "passive"))
    )
    (net (code "59") (name "Net-(CHGIC-NTC)") (class "Default")
      (node (ref "CHGIC") (pin "13") (pinfunction "NTC_13") (pintype "bidirectional"))
      (node (ref "R5") (pin "1") (pinfunction "1_1") (pintype "passive"))
      (node (ref "R6") (pin "2") (pinfunction "2_2") (pintype "passive"))
    )
    (net (code "60") (name "Net-(CHGIC-SW)") (class "Default")
      (node (ref "C14") (pin "2") (pinfunction "2_2") (pintype "passive"))
      (node (ref "CHGIC") (pin "1") (pinfunction "SW_1") (pintype "bidirectional"))
      (node (ref "L2") (pin "1") (pinfunction "1_1") (pintype "passive"))
    )
    (net (code "61") (name "Net-(CHGIC-TMR)") (class "Default")
      (node (ref "C10") (pin "2") (pinfunction "2_2") (pintype "passive"))
      (node (ref "CHGIC") (pin "14") (pinfunction "TMR_14") (pintype "bidirectional"))
    )
    (net (code "62") (name "Net-(D4-PadC)") (class "Default")
      (node (ref "D4") (pin "C") (pinfunction "C_C") (pintype "passive"))
      (node (ref "R31") (pin "1") (pinfunction "1_1") (pintype "passive"))
    )
    (net (code "63") (name "Net-(D5-PadC)") (class "Default")
      (node (ref "D5") (pin "C") (pinfunction "C_C") (pintype "passive"))
      (node (ref "R29") (pin "1") (pinfunction "1_1") (pintype "passive"))
    )
    (net (code "64") (name "Net-(D6-PadC)") (class "Default")
      (node (ref "D6") (pin "C") (pinfunction "C_C") (pintype "passive"))
      (node (ref "R33") (pin "1") (pinfunction "1_1") (pintype "passive"))
    )
    (net (code "65") (name "Net-(D7-PadC)") (class "Default")
      (node (ref "D7") (pin "C") (pinfunction "C_C") (pintype "passive"))
      (node (ref "R32") (pin "1") (pinfunction "1_1") (pintype "passive"))
    )
    (net (code "66") (name "Net-(D10-PadC)") (class "Default")
      (node (ref "D10") (pin "C") (pinfunction "C_C") (pintype "passive"))
      (node (ref "R61") (pin "2") (pinfunction "2_2") (pintype "passive"))
    )
    (net (code "67") (name "Net-(D11-PadC)") (class "Default")
      (node (ref "D11") (pin "C") (pinfunction "C_C") (pintype "passive"))
      (node (ref "R62") (pin "2") (pinfunction "2_2") (pintype "passive"))
    )
    (net (code "68") (name "Net-(D12-PadC)") (class "Default")
      (node (ref "D12") (pin "C") (pinfunction "C_C") (pintype "passive"))
      (node (ref "R63") (pin "2") (pinfunction "2_2") (pintype "passive"))
    )
    (net (code "69") (name "Net-(D13-PadC)") (class "Default")
      (node (ref "D13") (pin "C") (pinfunction "C_C") (pintype "passive"))
      (node (ref "R64") (pin "2") (pinfunction "2_2") (pintype "passive"))
    )
    (net (code "70") (name "Net-(GRN-PadC)") (class "Default")
      (node (ref "GRN") (pin "C") (pinfunction "C_C") (pintype "passive"))
      (node (ref "R22") (pin "1") (pinfunction "1_1") (pintype "passive"))
    )
    (net (code "71") (name "Net-(HOST-D+)") (class "Default")
      (node (ref "HOST") (pin "3") (pinfunction "D+_3") (pintype "bidirectional"))
      (node (ref "SIP") (pin "R17") (pinfunction "USB1_DP_R17") (pintype "bidirectional"))
      (node (ref "U4") (pin "1") (pinfunction "D+_1") (pintype "passive"))
    )
    (net (code "72") (name "Net-(HOST-D-)") (class "Default")
      (node (ref "HOST") (pin "2") (pinfunction "D-_2") (pintype "bidirectional"))
      (node (ref "SIP") (pin "R18") (pinfunction "USB1_DM_R18") (pintype "bidirectional"))
      (node (ref "U4") (pin "2") (pinfunction "D-_2") (pintype "passive"))
    )
    (net (code "73") (name "Net-(HOST-GND)") (class "Default")
      (node (ref "HOST") (pin "4") (pinfunction "GND_4") (pintype "bidirectional"))
      (node (ref "L4") (pin "2") (pinfunction "2_2") (pintype "passive"))
    )
    (net (code "74") (name "Net-(HOST-VBUS)") (class "Default")
      (node (ref "HOST") (pin "1") (pinfunction "VBUS_1") (pintype "bidirectional"))
      (node (ref "L5") (pin "2") (pinfunction "2_2") (pintype "passive"))
    )
    (net (code "75") (name "Net-(IMU-REGOUT)") (class "Default")
      (node (ref "C6") (pin "1") (pinfunction "1_1") (pintype "passive"))
      (node (ref "IMU") (pin "10") (pinfunction "REGOUT_10") (pintype "bidirectional"))
    )
    (net (code "76") (name "Net-(M1-1)") (class "Default")
      (node (ref "H1") (pin "5") (pinfunction "A02_5") (pintype "bidirectional"))
      (node (ref "H1") (pin "6") (pinfunction "A02_6") (pintype "bidirectional"))
      (node (ref "M1") (pin "P$1") (pinfunction "1_P$1") (pintype "bidirectional"))
    )
    (net (code "77") (name "Net-(M1-2)") (class "Default")
      (node (ref "H1") (pin "1") (pinfunction "A01_1") (pintype "bidirectional"))
      (node (ref "H1") (pin "2") (pinfunction "A01_2") (pintype "bidirectional"))
      (node (ref "M1") (pin "P$2") (pinfunction "2_P$2") (pintype "bidirectional"))
    )
    (net (code "78") (name "Net-(M2-1)") (class "Default")
      (node (ref "H1") (pin "11") (pinfunction "B01_11") (pintype "bidirectional"))
      (node (ref "H1") (pin "12") (pinfunction "B01_12") (pintype "bidirectional"))
      (node (ref "M2") (pin "P$1") (pinfunction "1_P$1") (pintype "bidirectional"))
    )
    (net (code "79") (name "Net-(M2-2)") (class "Default")
      (node (ref "H1") (pin "7") (pinfunction "B02_7") (pintype "bidirectional"))
      (node (ref "H1") (pin "8") (pinfunction "B02_8") (pintype "bidirectional"))
      (node (ref "M2") (pin "P$2") (pinfunction "2_P$2") (pintype "bidirectional"))
    )
    (net (code "80") (name "Net-(M3-1)") (class "Default")
      (node (ref "H2") (pin "1") (pinfunction "A01_1") (pintype "bidirectional"))
      (node (ref "H2") (pin "2") (pinfunction "A01_2") (pintype "bidirectional"))
      (node (ref "M3") (pin "P$1") (pinfunction "1_P$1") (pintype "bidirectional"))
    )
    (net (code "81") (name "Net-(M3-2)") (class "Default")
      (node (ref "H2") (pin "5") (pinfunction "A02_5") (pintype "bidirectional"))
      (node (ref "H2") (pin "6") (pinfunction "A02_6") (pintype "bidirectional"))
      (node (ref "M3") (pin "P$2") (pinfunction "2_P$2") (pintype "bidirectional"))
    )
    (net (code "82") (name "Net-(M4-1)") (class "Default")
      (node (ref "H2") (pin "7") (pinfunction "B02_7") (pintype "bidirectional"))
      (node (ref "H2") (pin "8") (pinfunction "B02_8") (pintype "bidirectional"))
      (node (ref "M4") (pin "P$1") (pinfunction "1_P$1") (pintype "bidirectional"))
    )
    (net (code "83") (name "Net-(M4-2)") (class "Default")
      (node (ref "H2") (pin "11") (pinfunction "B01_11") (pintype "bidirectional"))
      (node (ref "H2") (pin "12") (pinfunction "B01_12") (pintype "bidirectional"))
      (node (ref "M4") (pin "P$2") (pinfunction "2_P$2") (pintype "bidirectional"))
    )
    (net (code "84") (name "Net-(OTG-D+)") (class "Default")
      (node (ref "OTG") (pin "3") (pinfunction "D+_3") (pintype "bidirectional"))
      (node (ref "SIP") (pin "N17") (pinfunction "USB0_DP_N17") (pintype "bidirectional"))
      (node (ref "U1") (pin "1") (pinfunction "D+_1") (pintype "passive"))
    )
    (net (code "85") (name "Net-(OTG-D-)") (class "Default")
      (node (ref "OTG") (pin "2") (pinfunction "D-_2") (pintype "bidirectional"))
      (node (ref "SIP") (pin "N18") (pinfunction "USB0_DM_N18") (pintype "bidirectional"))
      (node (ref "U1") (pin "2") (pinfunction "D-_2") (pintype "passive"))
    )
    (net (code "86") (name "Net-(OTG-ID)") (class "Default")
      (node (ref "OTG") (pin "4") (pinfunction "ID_4") (pintype "bidirectional"))
      (node (ref "SIP") (pin "P16") (pinfunction "USB0_ID_P16") (pintype "bidirectional"))
      (node (ref "U1") (pin "3") (pinfunction "ID_3") (pintype "passive"))
    )
    (net (code "87") (name "Net-(OTG-VB)") (class "Default")
      (node (ref "OTG") (pin "1") (pinfunction "VB_1") (pintype "bidirectional"))
      (node (ref "R149") (pin "2") (pinfunction "2_2") (pintype "passive"))
      (node (ref "R154") (pin "1") (pinfunction "1_1") (pintype "passive"))
      (node (ref "U1") (pin "6") (pinfunction "VBUS_6") (pintype "passive"))
    )
    (net (code "88") (name "Net-(P10-CD)") (class "Default")
      (node (ref "P10") (pin "10") (pinfunction "CD_10") (pintype "bidirectional"))
      (node (ref "R71") (pin "2") (pinfunction "2_2") (pintype "passive"))
      (node (ref "SIP") (pin "C15") (pinfunction "MMC0_CD_C15_C15") (pintype "bidirectional"))
    )
    (net (code "89") (name "Net-(P10-CD{slash}DAT3)") (class "Default")
      (node (ref "P10") (pin "2") (pinfunction "CD/DAT3_2") (pintype "bidirectional"))
      (node (ref "R68") (pin "2") (pinfunction "2_2") (pintype "passive"))
      (node (ref "SIP") (pin "F17") (pinfunction "MMC0_DAT3_F17_F17") (pintype "bidirectional"))
    )
    (net (code "90") (name "Net-(P10-CLOCK)") (class "Default")
      (node (ref "P10") (pin "5") (pinfunction "CLOCK_5") (pintype "bidirectional"))
      (node (ref "R70") (pin "2") (pinfunction "2_2") (pintype "passive"))
      (node (ref "SIP") (pin "G17") (pinfunction "MMC0_CLK_G17_G17") (pintype "bidirectional"))
    )
    (net (code "91") (name "Net-(P10-CMD)") (class "Default")
      (node (ref "P10") (pin "3") (pinfunction "CMD_3") (pintype "bidirectional"))
      (node (ref "R69") (pin "2") (pinfunction "2_2") (pintype "passive"))
      (node (ref "SIP") (pin "G18") (pinfunction "MMC0_CMD_G18_G18") (pintype "bidirectional"))
    )
    (net (code "92") (name "Net-(P10-DAT0)") (class "Default")
      (node (ref "P10") (pin "7") (pinfunction "DAT0_7") (pintype "bidirectional"))
      (node (ref "R65") (pin "2") (pinfunction "2_2") (pintype "passive"))
      (node (ref "SIP") (pin "G16") (pinfunction "MMC0_DAT0_G16_G16") (pintype "bidirectional"))
    )
    (net (code "93") (name "Net-(P10-DAT1)") (class "Default")
      (node (ref "P10") (pin "8") (pinfunction "DAT1_8") (pintype "bidirectional"))
      (node (ref "R66") (pin "2") (pinfunction "2_2") (pintype "passive"))
      (node (ref "SIP") (pin "G15") (pinfunction "MMC0_DAT1_G15_G15") (pintype "bidirectional"))
    )
    (net (code "94") (name "Net-(P10-DAT2)") (class "Default")
      (node (ref "P10") (pin "1") (pinfunction "DAT2_1") (pintype "bidirectional"))
      (node (ref "R67") (pin "2") (pinfunction "2_2") (pintype "passive"))
      (node (ref "SIP") (pin "F18") (pinfunction "MMC0_DAT2_F18_F18") (pintype "bidirectional"))
    )
    (net (code "95") (name "Net-(PROT-VDD)") (class "Default")
      (node (ref "C15") (pin "2") (pinfunction "2_2") (pintype "passive"))
      (node (ref "PROT") (pin "5") (pinfunction "VDD_5") (pintype "bidirectional"))
      (node (ref "R44") (pin "2") (pinfunction "2_2") (pintype "passive"))
    )
    (net (code "96") (name "Net-(R21-Pad1)") (class "Default")
      (node (ref "R21") (pin "1") (pinfunction "1_1") (pintype "passive"))
      (node (ref "RED") (pin "C") (pinfunction "C_C") (pintype "passive"))
    )
    (net (code "97") (name "Net-(SIPA-BAT_TEMP)") (class "Default")
      (node (ref "SIP") (pin "W1") (pinfunction "BAT_TEMP_W1") (pintype "bidirectional"))
      (node (ref "TP4") (pin "TP") (pinfunction "TP_TP") (pintype "input"))
    )
    (net (code "98") (name "Net-(SIPA-BAT_VOLT)") (class "Default")
      (node (ref "SIP") (pin "Y1") (pinfunction "BAT_VOLT_Y1") (pintype "bidirectional"))
      (node (ref "TP3") (pin "TP") (pinfunction "TP_TP") (pintype "input"))
    )
    (net (code "99") (name "Net-(SIPA-L1_IN)") (class "Default")
      (node (ref "SIP") (pin "Y14") (pinfunction "L1_IN_Y14") (pintype "bidirectional"))
      (node (ref "TP6") (pin "TP") (pinfunction "TP_TP") (pintype "input"))
    )
    (net (code "100") (name "Net-(SIPA-L1_OUT)") (class "Default")
      (node (ref "SIP") (pin "Y13") (pinfunction "L1_OUT_Y13") (pintype "bidirectional"))
      (node (ref "TP7") (pin "TP") (pinfunction "TP_TP") (pintype "input"))
    )
    (net (code "101") (name "Net-(SIPA-L2_IN)") (class "Default")
      (node (ref "SIP") (pin "Y17") (pinfunction "L2_IN_Y17") (pintype "bidirectional"))
      (node (ref "TP8") (pin "TP") (pinfunction "TP_TP") (pintype "input"))
    )
    (net (code "102") (name "Net-(SIPA-L2_OUT)") (class "Default")
      (node (ref "SIP") (pin "Y16") (pinfunction "L2_OUT_Y16") (pintype "bidirectional"))
      (node (ref "TP9") (pin "TP") (pinfunction "TP_TP") (pintype "input"))
    )
    (net (code "103") (name "Net-(SIPA-L3_IN)") (class "Default")
      (node (ref "SIP") (pin "Y20") (pinfunction "L3_IN_Y20") (pintype "bidirectional"))
      (node (ref "TP10") (pin "TP") (pinfunction "TP_TP") (pintype "input"))
    )
    (net (code "104") (name "Net-(SIPA-L3_OUT)") (class "Default")
      (node (ref "SIP") (pin "Y19") (pinfunction "L3_OUT_Y19") (pintype "bidirectional"))
      (node (ref "TP11") (pin "TP") (pinfunction "TP_TP") (pintype "input"))
    )
    (net (code "105") (name "Net-(SIPA-PMIC_IN_PWR_EN)") (class "Default")
      (node (ref "SIP") (pin "C6") (pinfunction "PMIC_POWER_EN_C6") (pintype "output"))
      (node (ref "SIP") (pin "D19") (pinfunction "PMIC_IN_PWR_EN_D19") (pintype "input"))
      (node (ref "TP5") (pin "TP") (pinfunction "TP_TP") (pintype "input"))
    )
    (net (code "106") (name "Net-(SIPA-VIN_BAT_0)") (class "Default")
      (node (ref "SIP") (pin "Y2") (pinfunction "VIN_BAT_0_Y2") (pintype "power_in"))
      (node (ref "SIP") (pin "Y3") (pinfunction "VIN_BAT_1_Y3") (pintype "power_in"))
      (node (ref "TP2") (pin "TP") (pinfunction "TP_TP") (pintype "input"))
    )
    (net (code "107") (name "Net-(SIPB-EMMCRST_GPIO1_20_R14)") (class "Default")
      (node (ref "R94") (pin "1") (pinfunction "1_1") (pintype "passive"))
      (node (ref "SIP") (pin "R14") (pinfunction "EMMCRST_GPIO1_20_R14_R14") (pintype "bidirectional"))
      (node (ref "U8") (pin "K5") (pinfunction "RST_K5") (pintype "bidirectional"))
    )
    (net (code "108") (name "Net-(SIPB-GPIO0_19_A15)") (class "Default")
      (node (ref "R82") (pin "1") (pinfunction "1_1") (pintype "passive"))
      (node (ref "SIP") (pin "A15") (pinfunction "GPIO0_19_A15_A15") (pintype "bidirectional"))
    )
    (net (code "109") (name "Net-(SIPB-GPIO1_12_T12)") (class "Default")
      (node (ref "R95") (pin "1") (pinfunction "1_1") (pintype "passive"))
      (node (ref "SIP") (pin "T12") (pinfunction "GPIO1_12_T12_T12") (pintype "bidirectional"))
    )
    (net (code "110") (name "Net-(SIPB-GPIO1_13_R12)") (class "Default")
      (node (ref "R96") (pin "1") (pinfunction "1_1") (pintype "passive"))
      (node (ref "SIP") (pin "R12") (pinfunction "GPIO1_13_R12_R12") (pintype "bidirectional"))
    )
    (net (code "111") (name "Net-(SIPB-GPIO1_14_V13)") (class "Default")
      (node (ref "R97") (pin "1") (pinfunction "1_1") (pintype "passive"))
      (node (ref "SIP") (pin "V13") (pinfunction "GPIO1_14_V13_V13") (pintype "bidirectional"))
    )
    (net (code "112") (name "Net-(SIPB-GPIO1_15_U13)") (class "Default")
      (node (ref "R98") (pin "1") (pinfunction "1_1") (pintype "passive"))
      (node (ref "SIP") (pin "U13") (pinfunction "GPIO1_15_U13_U13") (pintype "bidirectional"))
    )
    (net (code "113") (name "Net-(SIPB-GPIO3_18_B12)") (class "Default")
      (node (ref "R99") (pin "1") (pinfunction "1_1") (pintype "passive"))
      (node (ref "SIP") (pin "B12") (pinfunction "GPIO3_18_B12_B12") (pintype "bidirectional"))
    )
    (net (code "114") (name "Net-(SIPB-GPIO3_19_C13)") (class "Default")
      (node (ref "R100") (pin "1") (pinfunction "1_1") (pintype "passive"))
      (node (ref "SIP") (pin "C13") (pinfunction "GPIO3_19_C13_C13") (pintype "bidirectional"))
    )
    (net (code "115") (name "Net-(SIPB-I2C1_SCL_A16)") (class "Default")
      (node (ref "R75") (pin "2") (pinfunction "2_2") (pintype "passive"))
      (node (ref "SIP") (pin "A16") (pinfunction "I2C1_SCL_A16_A16") (pintype "bidirectional"))
    )
    (net (code "116") (name "Net-(SIPB-I2C1_SDA_B16)") (class "Default")
      (node (ref "R74") (pin "2") (pinfunction "2_2") (pintype "passive"))
      (node (ref "SIP") (pin "B16") (pinfunction "I2C1_SDA_B16_B16") (pintype "bidirectional"))
    )
    (net (code "117") (name "Net-(SIPB-I2C2_SCL_D17)") (class "Default")
      (node (ref "R81") (pin "2") (pinfunction "2_2") (pintype "passive"))
      (node (ref "SIP") (pin "D17") (pinfunction "I2C2_SCL_D17_D17") (pintype "bidirectional"))
    )
    (net (code "118") (name "Net-(SIPB-I2C2_SDA_D18)") (class "Default")
      (node (ref "R80") (pin "2") (pinfunction "2_2") (pintype "passive"))
      (node (ref "SIP") (pin "D18") (pinfunction "I2C2_SDA_D18_D18") (pintype "bidirectional"))
    )
    (net (code "119") (name "Net-(SIPB-JTAG_EMU0)") (class "Default")
      (node (ref "SIP") (pin "C14") (pinfunction "JTAG_EMU0_C14") (pintype "bidirectional"))
      (node (ref "TP15") (pin "TP") (pinfunction "TP_TP") (pintype "input"))
    )
    (net (code "120") (name "Net-(SIPB-JTAG_EMU1)") (class "Default")
      (node (ref "SIP") (pin "B14") (pinfunction "JTAG_EMU1_B14") (pintype "bidirectional"))
      (node (ref "TP14") (pin "TP") (pinfunction "TP_TP") (pintype "input"))
    )
    (net (code "121") (name "Net-(SIPB-JTAG_TCK)") (class "Default")
      (node (ref "SIP") (pin "A12") (pinfunction "JTAG_TCK_A12") (pintype "bidirectional"))
      (node (ref "TP17") (pin "TP") (pinfunction "TP_TP") (pintype "input"))
    )
    (net (code "122") (name "Net-(SIPB-JTAG_TDI)") (class "Default")
      (node (ref "SIP") (pin "B11") (pinfunction "JTAG_TDI_B11") (pintype "bidirectional"))
      (node (ref "TP18") (pin "TP") (pinfunction "TP_TP") (pintype "input"))
    )
    (net (code "123") (name "Net-(SIPB-JTAG_TDO)") (class "Default")
      (node (ref "SIP") (pin "A11") (pinfunction "JTAG_TDO_A11") (pintype "bidirectional"))
      (node (ref "TP16") (pin "TP") (pinfunction "TP_TP") (pintype "input"))
    )
    (net (code "124") (name "Net-(SIPB-JTAG_TMS)") (class "Default")
      (node (ref "SIP") (pin "C11") (pinfunction "JTAG_TMS_C11") (pintype "bidirectional"))
      (node (ref "TP19") (pin "TP") (pinfunction "TP_TP") (pintype "input"))
    )
    (net (code "125") (name "Net-(SIPB-JTAG_TRSTN)") (class "Default")
      (node (ref "R59") (pin "2") (pinfunction "2_2") (pintype "passive"))
      (node (ref "SIP") (pin "B10") (pinfunction "JTAG_TRSTN_B10") (pintype "bidirectional"))
      (node (ref "TP20") (pin "TP") (pinfunction "TP_TP") (pintype "input"))
    )
    (net (code "126") (name "Net-(SIPB-MMC1_CLK_U9)") (class "Default")
      (node (ref "R93") (pin "1") (pinfunction "1_1") (pintype "passive"))
      (node (ref "SIP") (pin "U9") (pinfunction "MMC1_CLK_U9_U9") (pintype "bidirectional"))
      (node (ref "U8") (pin "M6") (pinfunction "CLK_M6") (pintype "bidirectional"))
    )
    (net (code "127") (name "Net-(SIPB-MMC1_CMD_V9)") (class "Default")
      (node (ref "R92") (pin "1") (pinfunction "1_1") (pintype "passive"))
      (node (ref "SIP") (pin "V9") (pinfunction "MMC1_CMD_V9_V9") (pintype "bidirectional"))
      (node (ref "U8") (pin "M5") (pinfunction "CMD_M5") (pintype "bidirectional"))
    )
    (net (code "128") (name "Net-(SIPB-MMC1_DAT0_U7)") (class "Default")
      (node (ref "R91") (pin "1") (pinfunction "1_1") (pintype "passive"))
      (node (ref "SIP") (pin "U7") (pinfunction "MMC1_DAT0_U7_U7") (pintype "bidirectional"))
      (node (ref "U8") (pin "A3") (pinfunction "DAT0_A3") (pintype "bidirectional"))
    )
    (net (code "129") (name "Net-(SIPB-MMC1_DAT1_V7)") (class "Default")
      (node (ref "R90") (pin "1") (pinfunction "1_1") (pintype "passive"))
      (node (ref "SIP") (pin "V7") (pinfunction "MMC1_DAT1_V7_V7") (pintype "bidirectional"))
      (node (ref "U8") (pin "A4") (pinfunction "DAT1_A4") (pintype "bidirectional"))
    )
    (net (code "130") (name "Net-(SIPB-MMC1_DAT2_R8)") (class "Default")
      (node (ref "R89") (pin "1") (pinfunction "1_1") (pintype "passive"))
      (node (ref "SIP") (pin "R8") (pinfunction "MMC1_DAT2_R8_R8") (pintype "bidirectional"))
      (node (ref "U8") (pin "A5") (pinfunction "DAT2_A5") (pintype "bidirectional"))
    )
    (net (code "131") (name "Net-(SIPB-MMC1_DAT3_T8)") (class "Default")
      (node (ref "R88") (pin "1") (pinfunction "1_1") (pintype "passive"))
      (node (ref "SIP") (pin "T8") (pinfunction "MMC1_DAT3_T8_T8") (pintype "bidirectional"))
      (node (ref "U8") (pin "B2") (pinfunction "DAT3_B2") (pintype "bidirectional"))
    )
    (net (code "132") (name "Net-(SIPB-MMC1_DAT4_U8)") (class "Default")
      (node (ref "R87") (pin "1") (pinfunction "1_1") (pintype "passive"))
      (node (ref "SIP") (pin "U8") (pinfunction "MMC1_DAT4_U8_U8") (pintype "bidirectional"))
      (node (ref "U8") (pin "B3") (pinfunction "DAT4_B3") (pintype "bidirectional"))
    )
    (net (code "133") (name "Net-(SIPB-MMC1_DAT5_V8)") (class "Default")
      (node (ref "R86") (pin "1") (pinfunction "1_1") (pintype "passive"))
      (node (ref "SIP") (pin "V8") (pinfunction "MMC1_DAT5_V8_V8") (pintype "bidirectional"))
      (node (ref "U8") (pin "B4") (pinfunction "DAT5_B4") (pintype "bidirectional"))
    )
    (net (code "134") (name "Net-(SIPB-MMC1_DAT6_R9)") (class "Default")
      (node (ref "R85") (pin "1") (pinfunction "1_1") (pintype "passive"))
      (node (ref "SIP") (pin "R9") (pinfunction "MMC1_DAT6_R9_R9") (pintype "bidirectional"))
      (node (ref "U8") (pin "B5") (pinfunction "DAT6_B5") (pintype "bidirectional"))
    )
    (net (code "135") (name "Net-(SIPB-MMC1_DAT7_T9)") (class "Default")
      (node (ref "R84") (pin "1") (pinfunction "1_1") (pintype "passive"))
      (node (ref "SIP") (pin "T9") (pinfunction "MMC1_DAT7_T9_T9") (pintype "bidirectional"))
      (node (ref "U8") (pin "B6") (pinfunction "DAT7_B6") (pintype "bidirectional"))
    )
    (net (code "136") (name "Net-(SIPB-OSC0_GND)") (class "Default")
      (node (ref "C29") (pin "2") (pinfunction "2_2") (pintype "passive"))
      (node (ref "C30") (pin "2") (pinfunction "2_2") (pintype "passive"))
      (node (ref "SIP") (pin "L20") (pinfunction "OSC0_GND_L20") (pintype "bidirectional"))
    )
    (net (code "137") (name "Net-(SIPB-OSC0_IN)") (class "Default")
      (node (ref "C30") (pin "1") (pinfunction "1_1") (pintype "passive"))
      (node (ref "SIP") (pin "M20") (pinfunction "OSC0_IN_M20") (pintype "bidirectional"))
      (node (ref "Y1") (pin "2") (pinfunction "2_2") (pintype "passive"))
    )
    (net (code "138") (name "Net-(SIPB-OSC0_OUT)") (class "Default")
      (node (ref "C29") (pin "1") (pinfunction "1_1") (pintype "passive"))
      (node (ref "SIP") (pin "K20") (pinfunction "OSC0_OUT_K20") (pintype "bidirectional"))
      (node (ref "Y1") (pin "1") (pinfunction "1_1") (pintype "passive"))
    )
    (net (code "139") (name "Net-(SIPB-OSC1_GND)") (class "Default")
      (node (ref "C31") (pin "2") (pinfunction "2_2") (pintype "passive"))
      (node (ref "C32") (pin "1") (pinfunction "1_1") (pintype "passive"))
      (node (ref "SIP") (pin "G20") (pinfunction "OSC1_GND_G20") (pintype "bidirectional"))
    )
    (net (code "140") (name "Net-(SIPB-OSC1_IN)") (class "Default")
      (node (ref "C31") (pin "1") (pinfunction "1_1") (pintype "passive"))
      (node (ref "SIP") (pin "H20") (pinfunction "OSC1_IN_H20") (pintype "bidirectional"))
      (node (ref "Y2") (pin "2") (pinfunction "2_2") (pintype "passive"))
    )
    (net (code "141") (name "Net-(SIPB-OSC1_OUT)") (class "Default")
      (node (ref "C32") (pin "2") (pinfunction "2_2") (pintype "passive"))
      (node (ref "SIP") (pin "F20") (pinfunction "OSC1_OUT_F20") (pintype "bidirectional"))
      (node (ref "Y2") (pin "1") (pinfunction "1_1") (pintype "passive"))
    )
    (net (code "142") (name "Net-(SIPB-SPI1_CLK_A13)") (class "Default")
      (node (ref "R101") (pin "1") (pinfunction "1_1") (pintype "passive"))
      (node (ref "SIP") (pin "A13") (pinfunction "SPI1_CLK_A13_A13") (pintype "bidirectional"))
    )
    (net (code "143") (name "Net-(SIPB-SPI1_D0_B13)") (class "Default")
      (node (ref "R102") (pin "1") (pinfunction "1_1") (pintype "passive"))
      (node (ref "SIP") (pin "B13") (pinfunction "SPI1_D0_B13_B13") (pintype "bidirectional"))
    )
    (net (code "144") (name "Net-(SIPB-SPI1_D1_D12)") (class "Default")
      (node (ref "R103") (pin "1") (pinfunction "1_1") (pintype "passive"))
      (node (ref "SIP") (pin "D12") (pinfunction "SPI1_D1_D12_D12") (pintype "bidirectional"))
    )
    (net (code "145") (name "Net-(SIPB-UART0_RTSN_E17)") (class "Default")
      (node (ref "R104") (pin "1") (pinfunction "1_1") (pintype "passive"))
      (node (ref "SIP") (pin "E17") (pinfunction "UART0_RTSN_E17_E17") (pintype "bidirectional"))
    )
    (net (code "146") (name "Net-(SIPB-UART0_RXD_E15)") (class "Default")
      (node (ref "R77") (pin "2") (pinfunction "2_2") (pintype "passive"))
      (node (ref "SIP") (pin "E15") (pinfunction "UART0_RXD_E15_E15") (pintype "bidirectional"))
    )
    (net (code "147") (name "Net-(SIPB-UART0_TXD_E16)") (class "Default")
      (node (ref "R76") (pin "2") (pinfunction "2_2") (pintype "passive"))
      (node (ref "SIP") (pin "E16") (pinfunction "UART0_TXD_E16_E16") (pintype "bidirectional"))
    )
    (net (code "148") (name "Net-(SIPB-UART1_RXD_D16)") (class "Default")
      (node (ref "R79") (pin "2") (pinfunction "2_2") (pintype "passive"))
      (node (ref "SIP") (pin "D16") (pinfunction "UART1_RXD_D16_D16") (pintype "bidirectional"))
    )
    (net (code "149") (name "Net-(SIPB-UART1_TXD_D15)") (class "Default")
      (node (ref "R78") (pin "2") (pinfunction "2_2") (pintype "passive"))
      (node (ref "SIP") (pin "D15") (pinfunction "UART1_TXD_D15_D15") (pintype "bidirectional"))
    )
    (net (code "150") (name "Net-(SIPB-UART2_RXD_A17)") (class "Default")
      (node (ref "R72") (pin "2") (pinfunction "2_2") (pintype "passive"))
      (node (ref "SIP") (pin "A17") (pinfunction "UART2_RXD_A17_A17") (pintype "bidirectional"))
    )
    (net (code "151") (name "Net-(SIPB-UART2_TXD_B17)") (class "Default")
      (node (ref "R73") (pin "2") (pinfunction "2_2") (pintype "passive"))
      (node (ref "SIP") (pin "B17") (pinfunction "UART2_TXD_B17_B17") (pintype "bidirectional"))
    )
    (net (code "152") (name "Net-(SIPB-UART4_RXD_T17)") (class "Default")
      (node (ref "R83") (pin "1") (pinfunction "1_1") (pintype "passive"))
      (node (ref "SIP") (pin "T17") (pinfunction "UART4_RXD_T17_T17") (pintype "bidirectional"))
    )
    (net (code "153") (name "Net-(SIPB-USR0_V15)") (class "Default")
      (node (ref "D10") (pin "A") (pinfunction "A_A") (pintype "passive"))
      (node (ref "SIP") (pin "V15") (pinfunction "USR0_V15_V15") (pintype "bidirectional"))
    )
    (net (code "154") (name "Net-(SIPB-USR1_U15)") (class "Default")
      (node (ref "D11") (pin "A") (pinfunction "A_A") (pintype "passive"))
      (node (ref "SIP") (pin "U15") (pinfunction "USR1_U15_U15") (pintype "bidirectional"))
    )
    (net (code "155") (name "Net-(SIPB-USR2_T15)") (class "Default")
      (node (ref "D12") (pin "A") (pinfunction "A_A") (pintype "passive"))
      (node (ref "SIP") (pin "T15") (pinfunction "USR2_T15_T15") (pintype "bidirectional"))
    )
    (net (code "156") (name "Net-(SIPB-USR3_V16)") (class "Default")
      (node (ref "D13") (pin "A") (pinfunction "A_A") (pintype "passive"))
      (node (ref "SIP") (pin "V16") (pinfunction "USR3_V16_V16") (pintype "bidirectional"))
    )
    (net (code "157") (name "Net-(SIPC-ADC_VREFP)") (class "Default")
      (node (ref "C42") (pin "1") (pinfunction "1_1") (pintype "passive"))
      (node (ref "C43") (pin "1") (pinfunction "1_1") (pintype "passive"))
      (node (ref "R111") (pin "2") (pinfunction "2_2") (pintype "passive"))
      (node (ref "SIP") (pin "B9") (pinfunction "ADC_VREFP_B9") (pintype "bidirectional"))
    )
    (net (code "158") (name "Net-(SIPC-AIN0)") (class "Default")
      (node (ref "R105") (pin "2") (pinfunction "2_2") (pintype "passive"))
      (node (ref "SIP") (pin "B6") (pinfunction "AIN0_B6") (pintype "bidirectional"))
    )
    (net (code "159") (name "Net-(SIPC-AIN1)") (class "Default")
      (node (ref "R106") (pin "2") (pinfunction "2_2") (pintype "passive"))
      (node (ref "SIP") (pin "C7") (pinfunction "AIN1_C7") (pintype "bidirectional"))
    )
    (net (code "160") (name "Net-(SIPC-AIN2)") (class "Default")
      (node (ref "R107") (pin "2") (pinfunction "2_2") (pintype "passive"))
      (node (ref "SIP") (pin "B7") (pinfunction "AIN2_B7") (pintype "bidirectional"))
    )
    (net (code "161") (name "Net-(SIPC-AIN3)") (class "Default")
      (node (ref "R108") (pin "2") (pinfunction "2_2") (pintype "passive"))
      (node (ref "SIP") (pin "A7") (pinfunction "AIN3_A7") (pintype "bidirectional"))
    )
    (net (code "162") (name "Net-(SIPC-AIN7)") (class "Default")
      (node (ref "R109") (pin "2") (pinfunction "2_2") (pintype "passive"))
      (node (ref "R110") (pin "1") (pinfunction "1_1") (pintype "passive"))
      (node (ref "SIP") (pin "C9") (pinfunction "AIN7_C9") (pintype "bidirectional"))
    )
    (net (code "163") (name "Net-(SIPC-LCD_DATA8_U1)") (class "Default")
      (node (ref "R129") (pin "2") (pinfunction "2_2") (pintype "passive"))
      (node (ref "R144") (pin "1") (pinfunction "1_1") (pintype "passive"))
      (node (ref "SIP") (pin "U1") (pinfunction "LCD_DATA8_U1_U1") (pintype "bidirectional"))
    )
    (net (code "164") (name "Net-(SIPC-LCD_DATA9_U2)") (class "Default")
      (node (ref "R131") (pin "2") (pinfunction "2_2") (pintype "passive"))
      (node (ref "R145") (pin "1") (pinfunction "1_1") (pintype "passive"))
      (node (ref "SIP") (pin "U2") (pinfunction "LCD_DATA9_U2_U2") (pintype "bidirectional"))
    )
    (net (code "165") (name "Net-(SIPC-LCD_DATA11_U4)") (class "Default")
      (node (ref "R135") (pin "2") (pinfunction "2_2") (pintype "passive"))
      (node (ref "SIP") (pin "U4") (pinfunction "LCD_DATA11_U4_U4") (pintype "bidirectional"))
    )
    (net (code "166") (name "Net-(SIPC-LCD_DATA12_V2)") (class "Default")
      (node (ref "R137") (pin "2") (pinfunction "2_2") (pintype "passive"))
      (node (ref "R146") (pin "1") (pinfunction "1_1") (pintype "passive"))
      (node (ref "SIP") (pin "V2") (pinfunction "LCD_DATA12_V2_V2") (pintype "bidirectional"))
    )
    (net (code "167") (name "Net-(SIPC-LCD_DATA13_V3)") (class "Default")
      (node (ref "R139") (pin "2") (pinfunction "2_2") (pintype "passive"))
      (node (ref "R147") (pin "1") (pinfunction "1_1") (pintype "passive"))
      (node (ref "SIP") (pin "V3") (pinfunction "LCD_DATA13_V3_V3") (pintype "bidirectional"))
    )
    (net (code "168") (name "Net-(SIPC-USB0_VBUS)") (class "Default")
      (node (ref "R149") (pin "1") (pinfunction "1_1") (pintype "passive"))
      (node (ref "SIP") (pin "P15") (pinfunction "USB0_VBUS_P15") (pintype "bidirectional"))
    )
    (net (code "169") (name "Net-(SIPC-USB1OC_GPIO1_26_T16)") (class "Default")
      (node (ref "R155") (pin "1") (pinfunction "1_1") (pintype "passive"))
      (node (ref "SIP") (pin "T16") (pinfunction "USB1OC_GPIO1_26_T16_T16") (pintype "bidirectional"))
    )
    (net (code "170") (name "Net-(SIPC-USB1_DRVVBUS)") (class "Default")
      (node (ref "R151") (pin "2") (pinfunction "2_2") (pintype "passive"))
      (node (ref "SIP") (pin "F15") (pinfunction "USB1_DRVVBUS_F15") (pintype "bidirectional"))
      (node (ref "U7") (pin "4") (pinfunction "*EN_4") (pintype "input"))
    )
    (net (code "171") (name "Net-(SIPC-USB1_ID)") (class "Default")
      (node (ref "R150") (pin "1") (pinfunction "1_1") (pintype "passive"))
      (node (ref "SIP") (pin "P17") (pinfunction "USB1_ID_P17") (pintype "bidirectional"))
    )
    (net (code "172") (name "Net-(SIPC-USB1_VBUS)") (class "Default")
      (node (ref "R156") (pin "1") (pinfunction "1_1") (pintype "passive"))
      (node (ref "SIP") (pin "T18") (pinfunction "USB1_VBUS_T18") (pintype "bidirectional"))
    )
    (net (code "173") (name "Net-(SIPE-RTC_KALDO_ENN)") (class "Default")
      (node (ref "R158") (pin "1") (pinfunction "1_1") (pintype "passive"))
      (node (ref "SIP") (pin "B4") (pinfunction "RTC_KALDO_ENN_B4") (pintype "bidirectional"))
    )
    (net (code "174") (name "Net-(U$1-1)") (class "Default")
      (node (ref "R36") (pin "2") (pinfunction "2_2") (pintype "passive"))
      (node (ref "U$1") (pin "P$1") (pinfunction "1_P$1") (pintype "bidirectional"))
    )
    (net (code "175") (name "Net-(U$1-2)") (class "Default")
      (node (ref "R37") (pin "2") (pinfunction "2_2") (pintype "passive"))
      (node (ref "U$1") (pin "P$2") (pinfunction "2_P$2") (pintype "bidirectional"))
    )
    (net (code "176") (name "Net-(U$1-3)") (class "Default")
      (node (ref "R38") (pin "2") (pinfunction "2_2") (pintype "passive"))
      (node (ref "U$1") (pin "P$3") (pinfunction "3_P$3") (pintype "bidirectional"))
    )
    (net (code "177") (name "Net-(U$1-4)") (class "Default")
      (node (ref "R39") (pin "2") (pinfunction "2_2") (pintype "passive"))
      (node (ref "U$1") (pin "P$4") (pinfunction "4_P$4") (pintype "bidirectional"))
    )
    (net (code "178") (name "Net-(U$1-5)") (class "Default")
      (node (ref "R40") (pin "2") (pinfunction "2_2") (pintype "passive"))
      (node (ref "U$1") (pin "P$5") (pinfunction "5_P$5") (pintype "bidirectional"))
    )
    (net (code "179") (name "Net-(U$1-6)") (class "Default")
      (node (ref "R41") (pin "2") (pinfunction "2_2") (pintype "passive"))
      (node (ref "U$1") (pin "P$6") (pinfunction "6_P$6") (pintype "bidirectional"))
    )
    (net (code "180") (name "Net-(U$1-7)") (class "Default")
      (node (ref "R42") (pin "2") (pinfunction "2_2") (pintype "passive"))
      (node (ref "U$1") (pin "P$19") (pinfunction "7_P$19") (pintype "bidirectional"))
    )
    (net (code "181") (name "Net-(U$1-8)") (class "Default")
      (node (ref "R43") (pin "2") (pinfunction "2_2") (pintype "passive"))
      (node (ref "U$1") (pin "P$20") (pinfunction "8_P$20") (pintype "bidirectional"))
    )
    (net (code "182") (name "Net-(U4-VBUS)") (class "Default")
      (node (ref "C45") (pin "1") (pinfunction "1_1") (pintype "passive"))
      (node (ref "C46") (pin "1") (pinfunction "1_1") (pintype "passive"))
      (node (ref "L5") (pin "1") (pinfunction "1_1") (pintype "passive"))
      (node (ref "R156") (pin "2") (pinfunction "2_2") (pintype "passive"))
      (node (ref "U4") (pin "6") (pinfunction "VBUS_6") (pintype "passive"))
      (node (ref "U7") (pin "6") (pinfunction "OUT_2_6") (pintype "power_in"))
      (node (ref "U7") (pin "7") (pinfunction "OUT_3_7") (pintype "power_in"))
      (node (ref "U7") (pin "8") (pinfunction "OUT_8") (pintype "power_in"))
    )
    (net (code "183") (name "Net-(U5-WP)") (class "Default")
      (node (ref "R58") (pin "1") (pinfunction "1_1") (pintype "passive"))
      (node (ref "TP13") (pin "TP") (pinfunction "TP_TP") (pintype "input"))
      (node (ref "U5") (pin "5") (pinfunction "WP_5") (pintype "input"))
    )
    (net (code "184") (name "Net-(U7-*OC)") (class "Default")
      (node (ref "R155") (pin "2") (pinfunction "2_2") (pintype "passive"))
      (node (ref "R157") (pin "2") (pinfunction "2_2") (pintype "passive"))
      (node (ref "U7") (pin "5") (pinfunction "*OC_5") (pintype "output"))
    )
    (net (code "185") (name "Net-(U8-VCCI)") (class "Default")
      (node (ref "C36") (pin "2") (pinfunction "2_2") (pintype "passive"))
      (node (ref "U8") (pin "C2") (pinfunction "VCCI_C2") (pintype "bidirectional"))
    )
    (net (code "186") (name "PAUSE_BTN") (class "Default")
      (node (ref "PAUSE") (pin "2") (pinfunction "2_2") (pintype "passive"))
      (node (ref "SIP") (pin "T6") (pinfunction "TIMER5_T6_T6") (pintype "bidirectional"))
    )
    (net (code "187") (name "PMIC_INT") (class "Default")
      (node (ref "SIP") (pin "B18") (pinfunction "EXTINTN_B18") (pintype "bidirectional"))
      (node (ref "SIP") (pin "B19") (pinfunction "PMIC_OUT_NINT_B19") (pintype "output"))
    )
    (net (code "188") (name "PMIC_NWAKEUP") (class "Default")
      (node (ref "SIP") (pin "A19") (pinfunction "PMIC_OUT_NWAKEUP_A19") (pintype "output"))
      (node (ref "SIP") (pin "C5") (pinfunction "EXT_WAKEUP_C5") (pintype "bidirectional"))
    )
    (net (code "189") (name "PMIC_PGOOD") (class "Default")
      (node (ref "SIP") (pin "A20") (pinfunction "PMIC_OUT_PGOOD_A20") (pintype "output"))
      (node (ref "SIP") (pin "B15") (pinfunction "PWRONRSTN_B15") (pintype "bidirectional"))
      (node (ref "U6") (pin "2") (pinfunction "A_2") (pintype "input"))
    )
    (net (code "190") (name "PWM_1A") (class "Default")
      (node (ref "H1") (pin "23") (pinfunction "PWMA_23") (pintype "bidirectional"))
      (node (ref "SIP") (pin "U14") (pinfunction "EHRPWM1A_U14_U14") (pintype "bidirectional"))
    )
    (net (code "191") (name "PWM_1B") (class "Default")
      (node (ref "H1") (pin "15") (pinfunction "PWMB_15") (pintype "bidirectional"))
      (node (ref "SIP") (pin "T14") (pinfunction "EHRPWM1B_T14_T14") (pintype "bidirectional"))
    )
    (net (code "192") (name "PWM_2A") (class "Default")
      (node (ref "H2") (pin "23") (pinfunction "PWMA_23") (pintype "bidirectional"))
      (node (ref "SIP") (pin "U10") (pinfunction "EHRPWM2A_U10_U10") (pintype "bidirectional"))
    )
    (net (code "193") (name "PWM_2B") (class "Default")
      (node (ref "H2") (pin "15") (pinfunction "PWMB_15") (pintype "bidirectional"))
      (node (ref "SIP") (pin "T10") (pinfunction "EHRPWM2B_T10_T10") (pintype "bidirectional"))
    )
    (net (code "194") (name "PWR") (class "Default")
      (node (ref "POWER") (pin "2") (pinfunction "2_2") (pintype "passive"))
      (node (ref "SIP") (pin "D20") (pinfunction "PMIC_IN_PB_IN_D20") (pintype "bidirectional"))
    )
    (net (code "195") (name "PWR_LEDR") (class "Default")
      (node (ref "D8") (pin "C") (pinfunction "C_C") (pintype "passive"))
      (node (ref "R24") (pin "1") (pinfunction "1_1") (pintype "passive"))
    )
    (net (code "196") (name "QEP_0A") (class "Default")
      (node (ref "E1") (pin "3") (pinfunction "3_3") (pintype "bidirectional"))
      (node (ref "R20") (pin "1") (pinfunction "1_1") (pintype "passive"))
      (node (ref "R99") (pin "2") (pinfunction "2_2") (pintype "passive"))
    )
    (net (code "197") (name "QEP_0B") (class "Default")
      (node (ref "E1") (pin "4") (pinfunction "4_4") (pintype "bidirectional"))
      (node (ref "R100") (pin "2") (pinfunction "2_2") (pintype "passive"))
      (node (ref "R18") (pin "1") (pinfunction "1_1") (pintype "passive"))
    )
    (net (code "198") (name "QEP_1A") (class "Default")
      (node (ref "E2") (pin "3") (pinfunction "3_3") (pintype "bidirectional"))
      (node (ref "R146") (pin "2") (pinfunction "2_2") (pintype "passive"))
      (node (ref "R17") (pin "1") (pinfunction "1_1") (pintype "passive"))
    )
    (net (code "199") (name "QEP_1B") (class "Default")
      (node (ref "E2") (pin "4") (pinfunction "4_4") (pintype "bidirectional"))
      (node (ref "R147") (pin "2") (pinfunction "2_2") (pintype "passive"))
      (node (ref "R16") (pin "1") (pinfunction "1_1") (pintype "passive"))
    )
    (net (code "200") (name "QEP_2A") (class "Default")
      (node (ref "E3") (pin "3") (pinfunction "3_3") (pintype "bidirectional"))
      (node (ref "R15") (pin "1") (pinfunction "1_1") (pintype "passive"))
      (node (ref "R95") (pin "2") (pinfunction "2_2") (pintype "passive"))
    )
    (net (code "201") (name "QEP_2B") (class "Default")
      (node (ref "E3") (pin "4") (pinfunction "4_4") (pintype "bidirectional"))
      (node (ref "R9") (pin "1") (pinfunction "1_1") (pintype "passive"))
      (node (ref "R96") (pin "2") (pinfunction "2_2") (pintype "passive"))
    )
    (net (code "202") (name "QEP_4A") (class "Default")
      (node (ref "E4") (pin "3") (pinfunction "3_3") (pintype "bidirectional"))
      (node (ref "R35") (pin "1") (pinfunction "1_1") (pintype "passive"))
      (node (ref "R97") (pin "2") (pinfunction "2_2") (pintype "passive"))
    )
    (net (code "203") (name "QEP_4B") (class "Default")
      (node (ref "E4") (pin "4") (pinfunction "4_4") (pintype "bidirectional"))
      (node (ref "R26") (pin "1") (pinfunction "1_1") (pintype "passive"))
      (node (ref "R98") (pin "2") (pinfunction "2_2") (pintype "passive"))
    )
    (net (code "204") (name "RESET") (class "Default")
      (node (ref "C33") (pin "1") (pinfunction "1_1") (pintype "passive"))
      (node (ref "R60") (pin "1") (pinfunction "1_1") (pintype "passive"))
      (node (ref "RESET") (pin "2") (pinfunction "2_2") (pintype "passive"))
      (node (ref "SIP") (pin "A10") (pinfunction "WARMRSTN_A10") (pintype "bidirectional"))
      (node (ref "U6") (pin "4") (pinfunction "Y_4") (pintype "output"))
    )
    (net (code "205") (name "SERVO_EN") (class "Default")
      (node (ref "6V_REG") (pin "8") (pinfunction "EN_8") (pintype "bidirectional"))
      (node (ref "R133") (pin "2") (pinfunction "2_2") (pintype "passive"))
      (node (ref "R46") (pin "2") (pinfunction "2_2") (pintype "passive"))
      (node (ref "SIP") (pin "U3") (pinfunction "LCD_DATA10_U3_U3") (pintype "bidirectional"))
    )
    (net (code "206") (name "SPI1_MISO") (class "Default")
      (node (ref "R102") (pin "2") (pinfunction "2_2") (pintype "passive"))
      (node (ref "SPI1.1") (pin "4") (pinfunction "4_4") (pintype "bidirectional"))
      (node (ref "SPI1.2") (pin "4") (pinfunction "4_4") (pintype "bidirectional"))
    )
    (net (code "207") (name "SPI1_MOSI") (class "Default")
      (node (ref "R103") (pin "2") (pinfunction "2_2") (pintype "passive"))
      (node (ref "SPI1.1") (pin "3") (pinfunction "3_3") (pintype "bidirectional"))
      (node (ref "SPI1.2") (pin "3") (pinfunction "3_3") (pintype "bidirectional"))
    )
    (net (code "208") (name "SPI1_SCK") (class "Default")
      (node (ref "R101") (pin "2") (pinfunction "2_2") (pintype "passive"))
      (node (ref "SPI1.1") (pin "5") (pinfunction "5_5") (pintype "bidirectional"))
      (node (ref "SPI1.2") (pin "5") (pinfunction "5_5") (pintype "bidirectional"))
    )
    (net (code "209") (name "SPI1_SS1") (class "Default")
      (node (ref "R104") (pin "2") (pinfunction "2_2") (pintype "passive"))
      (node (ref "SPI1.1") (pin "6") (pinfunction "6_6") (pintype "bidirectional"))
    )
    (net (code "210") (name "SPI1_SS2") (class "Default")
      (node (ref "R82") (pin "2") (pinfunction "2_2") (pintype "passive"))
      (node (ref "SPI1.2") (pin "6") (pinfunction "6_6") (pintype "bidirectional"))
    )
    (net (code "211") (name "SVO1") (class "Default")
      (node (ref "R36") (pin "1") (pinfunction "1_1") (pintype "passive"))
      (node (ref "R50") (pin "1") (pinfunction "1_1") (pintype "passive"))
      (node (ref "SIP") (pin "U5") (pinfunction "LCD_VSYNC_U5_U5") (pintype "bidirectional"))
    )
    (net (code "212") (name "SVO2") (class "Default")
      (node (ref "R37") (pin "1") (pinfunction "1_1") (pintype "passive"))
      (node (ref "R51") (pin "1") (pinfunction "1_1") (pintype "passive"))
      (node (ref "SIP") (pin "V5") (pinfunction "LCD_PCLK_V5_V5") (pintype "bidirectional"))
    )
    (net (code "213") (name "SVO3") (class "Default")
      (node (ref "R38") (pin "1") (pinfunction "1_1") (pintype "passive"))
      (node (ref "R52") (pin "1") (pinfunction "1_1") (pintype "passive"))
      (node (ref "SIP") (pin "R5") (pinfunction "LCD_HSYNC_R5_R5") (pintype "bidirectional"))
    )
    (net (code "214") (name "SVO4") (class "Default")
      (node (ref "R39") (pin "1") (pinfunction "1_1") (pintype "passive"))
      (node (ref "R53") (pin "1") (pinfunction "1_1") (pintype "passive"))
      (node (ref "SIP") (pin "R6") (pinfunction "LCD_DE_R6_R6") (pintype "bidirectional"))
    )
    (net (code "215") (name "SVO5") (class "Default")
      (node (ref "R125") (pin "2") (pinfunction "2_2") (pintype "passive"))
      (node (ref "R40") (pin "1") (pinfunction "1_1") (pintype "passive"))
      (node (ref "R54") (pin "2") (pinfunction "2_2") (pintype "passive"))
      (node (ref "SIP") (pin "T3") (pinfunction "LCD_DATA6_T3_T3") (pintype "bidirectional"))
    )
    (net (code "216") (name "SVO6") (class "Default")
      (node (ref "R127") (pin "2") (pinfunction "2_2") (pintype "passive"))
      (node (ref "R41") (pin "1") (pinfunction "1_1") (pintype "passive"))
      (node (ref "R55") (pin "2") (pinfunction "2_2") (pintype "passive"))
      (node (ref "SIP") (pin "T4") (pinfunction "LCD_DATA7_T4_T4") (pintype "bidirectional"))
    )
    (net (code "217") (name "SVO7") (class "Default")
      (node (ref "R120") (pin "1") (pinfunction "1_1") (pintype "passive"))
      (node (ref "R42") (pin "1") (pinfunction "1_1") (pintype "passive"))
      (node (ref "R56") (pin "2") (pinfunction "2_2") (pintype "passive"))
      (node (ref "SIP") (pin "T1") (pinfunction "LCD_DATA4_T1_T1") (pintype "bidirectional"))
    )
    (net (code "218") (name "SVO8") (class "Default")
      (node (ref "R122") (pin "1") (pinfunction "1_1") (pintype "passive"))
      (node (ref "R43") (pin "1") (pinfunction "1_1") (pintype "passive"))
      (node (ref "R57") (pin "2") (pinfunction "2_2") (pintype "passive"))
      (node (ref "SIP") (pin "T2") (pinfunction "LCD_DATA5_T2_T2") (pintype "bidirectional"))
    )
    (net (code "219") (name "SYS_5V") (class "Default")
      (node (ref "R153") (pin "1") (pinfunction "1_1") (pintype "passive"))
      (node (ref "SIP") (pin "W4") (pinfunction "VOUT_SYS_5V_0_W4") (pintype "power_in"))
      (node (ref "SIP") (pin "Y4") (pinfunction "VOUT_SYS_5V_1_Y4") (pintype "power_in"))
      (node (ref "TP1") (pin "TP") (pinfunction "TP_TP") (pintype "input"))
    )
    (net (code "220") (name "UART0_RX") (class "Default")
      (node (ref "R77") (pin "1") (pinfunction "1_1") (pintype "passive"))
      (node (ref "UART0") (pin "3") (pinfunction "3_3") (pintype "bidirectional"))
    )
    (net (code "221") (name "UART0_TX") (class "Default")
      (node (ref "R76") (pin "1") (pinfunction "1_1") (pintype "passive"))
      (node (ref "UART0") (pin "4") (pinfunction "4_4") (pintype "bidirectional"))
    )
    (net (code "222") (name "UART1_RX") (class "Default")
      (node (ref "R79") (pin "1") (pinfunction "1_1") (pintype "passive"))
      (node (ref "UART1") (pin "3") (pinfunction "3_3") (pintype "bidirectional"))
    )
    (net (code "223") (name "UART1_TX") (class "Default")
      (node (ref "R78") (pin "1") (pinfunction "1_1") (pintype "passive"))
      (node (ref "UART1") (pin "4") (pinfunction "4_4") (pintype "bidirectional"))
    )
    (net (code "224") (name "UART2_RX") (class "Default")
      (node (ref "GPS") (pin "3") (pinfunction "3_3") (pintype "bidirectional"))
      (node (ref "R72") (pin "1") (pinfunction "1_1") (pintype "passive"))
    )
    (net (code "225") (name "UART2_TX") (class "Default")
      (node (ref "GPS") (pin "4") (pinfunction "4_4") (pintype "bidirectional"))
      (node (ref "R73") (pin "1") (pinfunction "1_1") (pintype "passive"))
    )
    (net (code "226") (name "UART4_RX") (class "Default")
      (node (ref "DSM2") (pin "P$3") (pinfunction "3_P$3") (pintype "bidirectional"))
      (node (ref "R83") (pin "2") (pinfunction "2_2") (pintype "passive"))
    )
    (net (code "227") (name "UART5_RX") (class "Default")
      (node (ref "R145") (pin "2") (pinfunction "2_2") (pintype "passive"))
      (node (ref "UART5") (pin "3") (pinfunction "3_3") (pintype "bidirectional"))
    )
    (net (code "228") (name "UART5_TX") (class "Default")
      (node (ref "R144") (pin "2") (pinfunction "2_2") (pintype "passive"))
      (node (ref "UART5") (pin "4") (pinfunction "4_4") (pintype "bidirectional"))
    )
    (net (code "229") (name "USB_DC") (class "Default")
      (node (ref "R154") (pin "2") (pinfunction "2_2") (pintype "passive"))
      (node (ref "SIP") (pin "Y8") (pinfunction "VIN_USB_0_Y8") (pintype "power_in"))
      (node (ref "SIP") (pin "Y9") (pinfunction "VIN_USB_1_Y9") (pintype "power_in"))
    )
    (net (code "230") (name "VCC") (class "Default")
      (node (ref "C12") (pin "1") (pinfunction "1_1") (pintype "passive"))
      (node (ref "C7") (pin "1") (pinfunction "1_1") (pintype "passive"))
      (node (ref "CHG") (pin "A") (pinfunction "A_A") (pintype "passive"))
      (node (ref "CHGIC") (pin "2") (pinfunction "VIN_2") (pintype "bidirectional"))
      (node (ref "D3") (pin "A") (pinfunction "A_A") (pintype "passive"))
      (node (ref "JACK") (pin "1") (pinfunction "1_1") (pintype "passive"))
      (node (ref "R1") (pin "1") (pinfunction "1_1") (pintype "passive"))
    )
    (net (code "231") (name "VCC_3V3B") (class "Default")
      (node (ref "C34") (pin "2") (pinfunction "2_2") (pintype "passive"))
      (node (ref "C35") (pin "2") (pinfunction "2_2") (pintype "passive"))
      (node (ref "P10") (pin "4") (pinfunction "VDD_4") (pintype "bidirectional"))
      (node (ref "R65") (pin "1") (pinfunction "1_1") (pintype "passive"))
      (node (ref "R66") (pin "1") (pinfunction "1_1") (pintype "passive"))
      (node (ref "R67") (pin "1") (pinfunction "1_1") (pintype "passive"))
      (node (ref "R68") (pin "1") (pinfunction "1_1") (pintype "passive"))
      (node (ref "R69") (pin "1") (pinfunction "1_1") (pintype "passive"))
      (node (ref "R70") (pin "1") (pinfunction "1_1") (pintype "passive"))
      (node (ref "R71") (pin "1") (pinfunction "1_1") (pintype "passive"))
    )
    (net (code "232") (name "VCC_CHG") (class "Default")
      (node (ref "C4") (pin "2") (pinfunction "2_2") (pintype "passive"))
      (node (ref "CHGIC") (pin "3") (pinfunction "VCC_3") (pintype "bidirectional"))
      (node (ref "CHGIC") (pin "5") (pinfunction "SEL_5") (pintype "bidirectional"))
      (node (ref "R5") (pin "2") (pinfunction "2_2") (pintype "passive"))
    )
    (net (code "233") (name "VDD_1V8") (class "Default")
      (node (ref "SIP") (pin "D10") (pinfunction "VDD_1V84_D10") (pintype "bidirectional"))
      (node (ref "SIP") (pin "E9") (pinfunction "VDD_1V83_E9") (pintype "bidirectional"))
      (node (ref "SIP") (pin "N16") (pinfunction "VOUT_LDO3_1P8V_0_N16") (pintype "power_in"))
      (node (ref "SIP") (pin "R16") (pinfunction "VOUT_LDO3_1P8V_1_R16") (pintype "power_in"))
    )
    (net (code "234") (name "VDD_3V3A") (class "Default")
      (node (ref "C28") (pin "1") (pinfunction "1_1") (pintype "passive"))
      (node (ref "R116") (pin "2") (pinfunction "2_2") (pintype "passive"))
      (node (ref "R118") (pin "2") (pinfunction "2_2") (pintype "passive"))
      (node (ref "R120") (pin "2") (pinfunction "2_2") (pintype "passive"))
      (node (ref "R122") (pin "2") (pinfunction "2_2") (pintype "passive"))
      (node (ref "R140") (pin "2") (pinfunction "2_2") (pintype "passive"))
      (node (ref "R157") (pin "1") (pinfunction "1_1") (pintype "passive"))
      (node (ref "R2") (pin "2") (pinfunction "2_2") (pintype "passive"))
      (node (ref "R23") (pin "2") (pinfunction "2_2") (pintype "passive"))
      (node (ref "R58") (pin "2") (pinfunction "2_2") (pintype "passive"))
      (node (ref "R60") (pin "2") (pinfunction "2_2") (pintype "passive"))
      (node (ref "SIP") (pin "E10") (pinfunction "VDD_3V3A1_E10") (pintype "bidirectional"))
      (node (ref "SIP") (pin "E11") (pinfunction "VDD_3V3A2_E11") (pintype "bidirectional"))
      (node (ref "SIP") (pin "E12") (pinfunction "VDD_3V3A3_E12") (pintype "bidirectional"))
      (node (ref "SIP") (pin "E13") (pinfunction "VDD_3V3A4_E13") (pintype "bidirectional"))
      (node (ref "SIP") (pin "F14") (pinfunction "VDD_3V3A5_F14") (pintype "bidirectional"))
      (node (ref "SIP") (pin "G14") (pinfunction "VDD_3V3A6_G14") (pintype "bidirectional"))
      (node (ref "SIP") (pin "H14") (pinfunction "VDD_3V3A7_H14") (pintype "bidirectional"))
      (node (ref "SIP") (pin "J14") (pinfunction "VDD_3V3A8_J14") (pintype "bidirectional"))
      (node (ref "SIP") (pin "K14") (pinfunction "VDD_3V3A9_K14") (pintype "bidirectional"))
      (node (ref "SIP") (pin "L14") (pinfunction "VDD_3V3A10_L14") (pintype "bidirectional"))
      (node (ref "SIP") (pin "N15") (pinfunction "VDD_3V3A12_N15") (pintype "bidirectional"))
      (node (ref "SIP") (pin "N5") (pinfunction "VDD_3V3A11_N5") (pintype "bidirectional"))
      (node (ref "SIP") (pin "P10") (pinfunction "VDD_3V3A17_P10") (pintype "bidirectional"))
      (node (ref "SIP") (pin "P11") (pinfunction "VDD_3V3A18_P11") (pintype "bidirectional"))
      (node (ref "SIP") (pin "P12") (pinfunction "VDD_3V3A19_P12") (pintype "bidirectional"))
      (node (ref "SIP") (pin "P13") (pinfunction "VDD_3V3A20_P13") (pintype "bidirectional"))
      (node (ref "SIP") (pin "P5") (pinfunction "VDD_3V3A13_P5") (pintype "bidirectional"))
      (node (ref "SIP") (pin "P6") (pinfunction "VDD_3V3A14_P6") (pintype "bidirectional"))
      (node (ref "SIP") (pin "P7") (pinfunction "VDD_3V3A15_P7") (pintype "bidirectional"))
      (node (ref "SIP") (pin "P8") (pinfunction "VDD_3V3A16_P8") (pintype "bidirectional"))
      (node (ref "SIP") (pin "R15") (pinfunction "VDD_3V3A21_R15") (pintype "bidirectional"))
      (node (ref "U5") (pin "4") (pinfunction "VCC_4") (pintype "power_in"))
    )
    (net (code "235") (name "VDD_3V3AUX") (class "Default")
      (node (ref "D8") (pin "A") (pinfunction "A_A") (pintype "passive"))
      (node (ref "SIP") (pin "Y11") (pinfunction "VOUT_LDO2_3P3V_Y11") (pintype "power_in"))
    )
    (net (code "236") (name "VDD_3V3B") (class "Default")
      (node (ref "C27") (pin "1") (pinfunction "1_1") (pintype "passive"))
      (node (ref "C37") (pin "1") (pinfunction "1_1") (pintype "passive"))
      (node (ref "C38") (pin "1") (pinfunction "1_1") (pintype "passive"))
      (node (ref "C39") (pin "1") (pinfunction "1_1") (pintype "passive"))
      (node (ref "C40") (pin "1") (pinfunction "1_1") (pintype "passive"))
      (node (ref "C41") (pin "1") (pinfunction "1_1") (pintype "passive"))
      (node (ref "R109") (pin "1") (pinfunction "1_1") (pintype "passive"))
      (node (ref "R84") (pin "2") (pinfunction "2_2") (pintype "passive"))
      (node (ref "R85") (pin "2") (pinfunction "2_2") (pintype "passive"))
      (node (ref "R86") (pin "2") (pinfunction "2_2") (pintype "passive"))
      (node (ref "R87") (pin "2") (pinfunction "2_2") (pintype "passive"))
      (node (ref "R88") (pin "2") (pinfunction "2_2") (pintype "passive"))
      (node (ref "R89") (pin "2") (pinfunction "2_2") (pintype "passive"))
      (node (ref "R90") (pin "2") (pinfunction "2_2") (pintype "passive"))
      (node (ref "R91") (pin "2") (pinfunction "2_2") (pintype "passive"))
      (node (ref "R92") (pin "2") (pinfunction "2_2") (pintype "passive"))
      (node (ref "R93") (pin "2") (pinfunction "2_2") (pintype "passive"))
      (node (ref "R94") (pin "2") (pinfunction "2_2") (pintype "passive"))
      (node (ref "SIP") (pin "U20") (pinfunction "VOUT_USER_3P3V_0_U20") (pintype "power_in"))
      (node (ref "SIP") (pin "V20") (pinfunction "VOUT_USER_3P3V_1_V20") (pintype "power_in"))
      (node (ref "U8") (pin "C6") (pinfunction "VCCQ4_C6") (pintype "bidirectional"))
      (node (ref "U8") (pin "E6") (pinfunction "VCC3_E6") (pintype "bidirectional"))
      (node (ref "U8") (pin "F5") (pinfunction "VCC2_F5") (pintype "bidirectional"))
      (node (ref "U8") (pin "J10") (pinfunction "VCC0_J10") (pintype "bidirectional"))
      (node (ref "U8") (pin "K9") (pinfunction "VCC1_K9") (pintype "bidirectional"))
      (node (ref "U8") (pin "M4") (pinfunction "VCCQ5_M4") (pintype "bidirectional"))
      (node (ref "U8") (pin "N4") (pinfunction "VCCQ3_N4") (pintype "bidirectional"))
      (node (ref "U8") (pin "P3") (pinfunction "VCCQ1_P3") (pintype "bidirectional"))
      (node (ref "U8") (pin "P5") (pinfunction "VCCQ2_P5") (pintype "bidirectional"))
    )
    (net (code "237") (name "VDD_ADC") (class "Default")
      (node (ref "ADC") (pin "2") (pinfunction "2_2") (pintype "bidirectional"))
      (node (ref "C44") (pin "1") (pinfunction "1_1") (pintype "passive"))
      (node (ref "R111") (pin "1") (pinfunction "1_1") (pintype "passive"))
      (node (ref "SIP") (pin "A4") (pinfunction "VOUT_ADC_1P8V_0_A4") (pintype "bidirectional"))
      (node (ref "SIP") (pin "A5") (pinfunction "VOUT_ADC_1P8V_1_A5") (pintype "bidirectional"))
      (node (ref "SIP") (pin "D8") (pinfunction "VDDA_ADC_D8") (pintype "bidirectional"))
    )
    (net (code "238") (name "VDD_RTC") (class "Default")
      (node (ref "SIP") (pin "D7") (pinfunction "VDD_RTC1_D7") (pintype "bidirectional"))
      (node (ref "SIP") (pin "E14") (pinfunction "VDD_RTC3_E14") (pintype "bidirectional"))
      (node (ref "SIP") (pin "E6") (pinfunction "VDD_RTC2_E6") (pintype "bidirectional"))
      (node (ref "SIP") (pin "F9") (pinfunction "VDD_RTC4_F9") (pintype "bidirectional"))
      (node (ref "SIP") (pin "K13") (pinfunction "VDD_RTC5_K13") (pintype "bidirectional"))
      (node (ref "SIP") (pin "N6") (pinfunction "VDD_RTC6_N6") (pintype "bidirectional"))
      (node (ref "SIP") (pin "P14") (pinfunction "VDD_RTC8_P14") (pintype "bidirectional"))
      (node (ref "SIP") (pin "P9") (pinfunction "VDD_RTC7_P9") (pintype "bidirectional"))
      (node (ref "U6") (pin "5") (pinfunction "VCC_5") (pintype "power_in"))
    )
    (net (code "239") (name "V_BATT") (class "Default")
      (node (ref "6V_REG") (pin "9") (pinfunction "VIN_9") (pintype "bidirectional"))
      (node (ref "C11") (pin "+") (pinfunction "+_+") (pintype "passive"))
      (node (ref "C20") (pin "2") (pinfunction "2_2") (pintype "passive"))
      (node (ref "C25") (pin "1") (pinfunction "1_1") (pintype "passive"))
      (node (ref "C26") (pin "1") (pinfunction "1_1") (pintype "passive"))
      (node (ref "CHGIC") (pin "9") (pinfunction "BATT_9") (pintype "bidirectional"))
      (node (ref "D2") (pin "A") (pinfunction "A_A") (pintype "passive"))
      (node (ref "H1") (pin "13") (pinfunction "VM2_13") (pintype "bidirectional"))
      (node (ref "H1") (pin "14") (pinfunction "VM3_14") (pintype "bidirectional"))
      (node (ref "H1") (pin "24") (pinfunction "VM1_24") (pintype "bidirectional"))
      (node (ref "H2") (pin "13") (pinfunction "VM2_13") (pintype "bidirectional"))
      (node (ref "H2") (pin "14") (pinfunction "VM3_14") (pintype "bidirectional"))
      (node (ref "H2") (pin "24") (pinfunction "VM1_24") (pintype "bidirectional"))
      (node (ref "LIPO") (pin "P$1") (pinfunction "1_P$1") (pintype "passive"))
      (node (ref "R19") (pin "1") (pinfunction "1_1") (pintype "passive"))
      (node (ref "R28") (pin "1") (pinfunction "1_1") (pintype "passive"))
      (node (ref "R34") (pin "1") (pinfunction "1_1") (pintype "passive"))
      (node (ref "R4") (pin "1") (pinfunction "1_1") (pintype "passive"))
    )
    (net (code "240") (name "V_DIV_BAT") (class "Default")
      (node (ref "R19") (pin "2") (pinfunction "2_2") (pintype "passive"))
      (node (ref "R25") (pin "1") (pinfunction "1_1") (pintype "passive"))
      (node (ref "SIP") (pin "A8") (pinfunction "AIN6_A8") (pintype "bidirectional"))
    )
    (net (code "241") (name "V_DIV_DC") (class "Default")
      (node (ref "R1") (pin "2") (pinfunction "2_2") (pintype "passive"))
      (node (ref "R14") (pin "1") (pinfunction "1_1") (pintype "passive"))
      (node (ref "SIP") (pin "B8") (pinfunction "AIN5_B8") (pintype "bidirectional"))
    )
    (net (code "242") (name "unconnected-(CHGIC-ACOK-Pad12)") (class "Default")
      (node (ref "CHGIC") (pin "12") (pinfunction "ACOK_12") (pintype "bidirectional"))
    )
    (net (code "243") (name "unconnected-(CHGIC-CELL-Pad4)") (class "Default")
      (node (ref "CHGIC") (pin "4") (pinfunction "CELL_4") (pintype "bidirectional"))
    )
    (net (code "244") (name "unconnected-(GPS-Pad1)") (class "Default")
      (node (ref "GPS") (pin "1") (pinfunction "1_1") (pintype "bidirectional"))
    )
    (net (code "245") (name "unconnected-(IMU-AUX_CL-Pad7)") (class "Default")
      (node (ref "IMU") (pin "7") (pinfunction "AUX_CL_7") (pintype "bidirectional"))
    )
    (net (code "246") (name "unconnected-(IMU-AUX_DA-Pad21)") (class "Default")
      (node (ref "IMU") (pin "21") (pinfunction "AUX_DA_21") (pintype "bidirectional"))
    )
    (net (code "247") (name "unconnected-(IMU-FSYNC-Pad11)") (class "Default")
      (node (ref "IMU") (pin "11") (pinfunction "FSYNC_11") (pintype "bidirectional"))
    )
    (net (code "248") (name "unconnected-(IMU-NC-Pad2)") (class "Default")
      (node (ref "IMU") (pin "2") (pinfunction "NC_2") (pintype "bidirectional"))
    )
    (net (code "249") (name "unconnected-(IMU-NC-Pad3)") (class "Default")
      (node (ref "IMU") (pin "3") (pinfunction "NC_3") (pintype "bidirectional"))
    )
    (net (code "250") (name "unconnected-(IMU-NC-Pad4)") (class "Default")
      (node (ref "IMU") (pin "4") (pinfunction "NC_4") (pintype "bidirectional"))
    )
    (net (code "251") (name "unconnected-(IMU-NC-Pad5)") (class "Default")
      (node (ref "IMU") (pin "5") (pinfunction "NC_5") (pintype "bidirectional"))
    )
    (net (code "252") (name "unconnected-(IMU-NC-Pad6)") (class "Default")
      (node (ref "IMU") (pin "6") (pinfunction "NC_6") (pintype "bidirectional"))
    )
    (net (code "253") (name "unconnected-(IMU-NC-Pad14)") (class "Default")
      (node (ref "IMU") (pin "14") (pinfunction "NC_14") (pintype "bidirectional"))
    )
    (net (code "254") (name "unconnected-(IMU-NC-Pad15)") (class "Default")
      (node (ref "IMU") (pin "15") (pinfunction "NC_15") (pintype "bidirectional"))
    )
    (net (code "255") (name "unconnected-(IMU-NC-Pad16)") (class "Default")
      (node (ref "IMU") (pin "16") (pinfunction "NC_16") (pintype "bidirectional"))
    )
    (net (code "256") (name "unconnected-(IMU-NC-Pad17)") (class "Default")
      (node (ref "IMU") (pin "17") (pinfunction "NC_17") (pintype "bidirectional"))
    )
    (net (code "257") (name "unconnected-(IMU-RESV-Pad19)") (class "Default")
      (node (ref "IMU") (pin "19") (pinfunction "RESV_19") (pintype "bidirectional"))
    )
    (net (code "258") (name "unconnected-(PROT-CO-Pad3)") (class "Default")
      (node (ref "PROT") (pin "3") (pinfunction "CO_3") (pintype "bidirectional"))
    )
    (net (code "259") (name "unconnected-(PROT-DP-Pad4)") (class "Default")
      (node (ref "PROT") (pin "4") (pinfunction "DP_4") (pintype "bidirectional"))
    )
    (net (code "260") (name "unconnected-(SIP-PadH16)") (class "Default")
      (node (ref "SIP") (pin "H16") (pinfunction "H16_H16") (pintype "bidirectional"))
    )
    (net (code "261") (name "unconnected-(SIP-PadH17)") (class "Default")
      (node (ref "SIP") (pin "H17") (pinfunction "H17_H17") (pintype "bidirectional"))
    )
    (net (code "262") (name "unconnected-(SIP-PadH18)") (class "Default")
      (node (ref "SIP") (pin "H18") (pinfunction "H18_H18") (pintype "bidirectional"))
    )
    (net (code "263") (name "unconnected-(SIP-PadJ15)") (class "Default")
      (node (ref "SIP") (pin "J15") (pinfunction "J15_J15") (pintype "bidirectional"))
    )
    (net (code "264") (name "unconnected-(SIP-PadJ16)") (class "Default")
      (node (ref "SIP") (pin "J16") (pinfunction "J16_J16") (pintype "bidirectional"))
    )
    (net (code "265") (name "unconnected-(SIP-PadJ17)") (class "Default")
      (node (ref "SIP") (pin "J17") (pinfunction "J17_J17") (pintype "bidirectional"))
    )
    (net (code "266") (name "unconnected-(SIP-PadJ18)") (class "Default")
      (node (ref "SIP") (pin "J18") (pinfunction "J18_J18") (pintype "bidirectional"))
    )
    (net (code "267") (name "unconnected-(SIP-PadK15)") (class "Default")
      (node (ref "SIP") (pin "K15") (pinfunction "K15_K15") (pintype "bidirectional"))
    )
    (net (code "268") (name "unconnected-(SIP-PadK16)") (class "Default")
      (node (ref "SIP") (pin "K16") (pinfunction "K16_K16") (pintype "bidirectional"))
    )
    (net (code "269") (name "unconnected-(SIP-PadK17)") (class "Default")
      (node (ref "SIP") (pin "K17") (pinfunction "K17_K17") (pintype "bidirectional"))
    )
    (net (code "270") (name "unconnected-(SIP-PadK18)") (class "Default")
      (node (ref "SIP") (pin "K18") (pinfunction "K18_K18") (pintype "bidirectional"))
    )
    (net (code "271") (name "unconnected-(SIP-PadL15)") (class "Default")
      (node (ref "SIP") (pin "L15") (pinfunction "L15_L15") (pintype "bidirectional"))
    )
    (net (code "272") (name "unconnected-(SIP-PadL16)") (class "Default")
      (node (ref "SIP") (pin "L16") (pinfunction "L16_L16") (pintype "bidirectional"))
    )
    (net (code "273") (name "unconnected-(SIP-PadL17)") (class "Default")
      (node (ref "SIP") (pin "L17") (pinfunction "L17_L17") (pintype "bidirectional"))
    )
    (net (code "274") (name "unconnected-(SIP-PadL18)") (class "Default")
      (node (ref "SIP") (pin "L18") (pinfunction "L18_L18") (pintype "bidirectional"))
    )
    (net (code "275") (name "unconnected-(SIP-PadM16)") (class "Default")
      (node (ref "SIP") (pin "M16") (pinfunction "M16_M16") (pintype "bidirectional"))
    )
    (net (code "276") (name "unconnected-(SIP-PadM17)") (class "Default")
      (node (ref "SIP") (pin "M17") (pinfunction "M17_M17") (pintype "bidirectional"))
    )
    (net (code "277") (name "unconnected-(SIP-PadM18)") (class "Default")
      (node (ref "SIP") (pin "M18") (pinfunction "M18_M18") (pintype "bidirectional"))
    )
    (net (code "278") (name "unconnected-(SIPB-GPIO0_7_C18-PadC18)") (class "Default")
      (node (ref "SIP") (pin "C18") (pinfunction "GPIO0_7_C18_C18") (pintype "bidirectional"))
    )
    (net (code "279") (name "unconnected-(SIPB-GPIO1_17_V14-PadV14)") (class "Default")
      (node (ref "SIP") (pin "V14") (pinfunction "GPIO1_17_V14_V14") (pintype "bidirectional"))
    )
    (net (code "280") (name "unconnected-(SIPB-GPIO1_28_U18-PadU18)") (class "Default")
      (node (ref "SIP") (pin "U18") (pinfunction "GPIO1_28_U18_U18") (pintype "bidirectional"))
    )
    (net (code "281") (name "unconnected-(SIPB-GPIO2_0_T13-PadT13)") (class "Default")
      (node (ref "SIP") (pin "T13") (pinfunction "GPIO2_0_T13_T13") (pintype "bidirectional"))
    )
    (net (code "282") (name "unconnected-(SIPB-GPIO2_1_V12-PadV12)") (class "Default")
      (node (ref "SIP") (pin "V12") (pinfunction "GPIO2_1_V12_V12") (pintype "bidirectional"))
    )
    (net (code "283") (name "unconnected-(SIPB-GPIO3_20_D13-PadD13)") (class "Default")
      (node (ref "SIP") (pin "D13") (pinfunction "GPIO3_20_D13_D13") (pintype "bidirectional"))
    )
    (net (code "284") (name "unconnected-(SIPB-UART0_CTSN_E18-PadE18)") (class "Default")
      (node (ref "SIP") (pin "E18") (pinfunction "UART0_CTSN_E18_E18") (pintype "bidirectional"))
    )
    (net (code "285") (name "unconnected-(SIPC-AIN4-PadC8)") (class "Default")
      (node (ref "SIP") (pin "C8") (pinfunction "AIN4_C8") (pintype "bidirectional"))
    )
    (net (code "286") (name "unconnected-(SIPC-HDMIDIS_GPIO1_27_V17-PadV17)") (class "Default")
      (node (ref "SIP") (pin "V17") (pinfunction "HDMIDIS_GPIO1_27_V17_V17") (pintype "bidirectional"))
    )
    (net (code "287") (name "unconnected-(SIPC-HDMIINT_GPIO1_25_U16-PadU16)") (class "Default")
      (node (ref "SIP") (pin "U16") (pinfunction "HDMIINT_GPIO1_25_U16_U16") (pintype "bidirectional"))
    )
    (net (code "288") (name "unconnected-(SIPC-USB0_CE-PadM15)") (class "Default")
      (node (ref "SIP") (pin "M15") (pinfunction "USB0_CE_M15") (pintype "bidirectional"))
    )
    (net (code "289") (name "unconnected-(SIPC-USB0_DRVVBUS-PadF16)") (class "Default")
      (node (ref "SIP") (pin "F16") (pinfunction "USB0_DRVVBUS_F16") (pintype "bidirectional"))
    )
    (net (code "290") (name "unconnected-(SIPC-USB1_CE-PadP18)") (class "Default")
      (node (ref "SIP") (pin "P18") (pinfunction "USB1_CE_P18") (pintype "bidirectional"))
    )
    (net (code "291") (name "unconnected-(SIPE-CAP_VBB_MPU-PadC10)") (class "Default")
      (node (ref "SIP") (pin "C10") (pinfunction "CAP_VBB_MPU_C10") (pintype "bidirectional"))
    )
    (net (code "292") (name "unconnected-(SIPE-CAP_VDD_RTC-PadD6)") (class "Default")
      (node (ref "SIP") (pin "D6") (pinfunction "CAP_VDD_RTC_D6") (pintype "bidirectional"))
    )
    (net (code "293") (name "unconnected-(SIPE-CAP_VDD_SRAM_COR-PadD9)") (class "Default")
      (node (ref "SIP") (pin "D9") (pinfunction "CAP_VDD_SRAM_COR_D9") (pintype "bidirectional"))
    )
    (net (code "294") (name "unconnected-(SIPE-CAP_VDD_SRAM_MPU-PadD11)") (class "Default")
      (node (ref "SIP") (pin "D11") (pinfunction "CAP_VDD_SRAM_MPU_D11") (pintype "bidirectional"))
    )
    (net (code "295") (name "unconnected-(SIPE-TESTOUT-PadA3)") (class "Default")
      (node (ref "SIP") (pin "A3") (pinfunction "TESTOUT_A3") (pintype "bidirectional"))
    )
    (net (code "296") (name "unconnected-(SIPE-VDDS_DDR1-PadE5)") (class "Default")
      (node (ref "SIP") (pin "E5") (pinfunction "VDDS_DDR1_E5") (pintype "bidirectional"))
    )
    (net (code "297") (name "unconnected-(SIPE-VDDS_DDR2-PadF5)") (class "Default")
      (node (ref "SIP") (pin "F5") (pinfunction "VDDS_DDR2_F5") (pintype "bidirectional"))
    )
    (net (code "298") (name "unconnected-(SIPE-VDDS_DDR3-PadG5)") (class "Default")
      (node (ref "SIP") (pin "G5") (pinfunction "VDDS_DDR3_G5") (pintype "bidirectional"))
    )
    (net (code "299") (name "unconnected-(SIPE-VDDS_DDR4-PadH5)") (class "Default")
      (node (ref "SIP") (pin "H5") (pinfunction "VDDS_DDR4_H5") (pintype "bidirectional"))
    )
    (net (code "300") (name "unconnected-(SIPE-VDDS_DDR5-PadJ5)") (class "Default")
      (node (ref "SIP") (pin "J5") (pinfunction "VDDS_DDR5_J5") (pintype "bidirectional"))
    )
    (net (code "301") (name "unconnected-(SIPE-VDDS_DDR6-PadK5)") (class "Default")
      (node (ref "SIP") (pin "K5") (pinfunction "VDDS_DDR6_K5") (pintype "bidirectional"))
    )
    (net (code "302") (name "unconnected-(SIPE-VDDS_DDR7-PadL5)") (class "Default")
      (node (ref "SIP") (pin "L5") (pinfunction "VDDS_DDR7_L5") (pintype "bidirectional"))
    )
    (net (code "303") (name "unconnected-(SIPE-VDD_CORE1-PadF6)") (class "Default")
      (node (ref "SIP") (pin "F6") (pinfunction "VDD_CORE1_F6") (pintype "bidirectional"))
    )
    (net (code "304") (name "unconnected-(SIPE-VDD_CORE2-PadF7)") (class "Default")
      (node (ref "SIP") (pin "F7") (pinfunction "VDD_CORE2_F7") (pintype "bidirectional"))
    )
    (net (code "305") (name "unconnected-(SIPE-VDD_CORE3-PadG6)") (class "Default")
      (node (ref "SIP") (pin "G6") (pinfunction "VDD_CORE3_G6") (pintype "bidirectional"))
    )
    (net (code "306") (name "unconnected-(SIPE-VDD_CORE4-PadG7)") (class "Default")
      (node (ref "SIP") (pin "G7") (pinfunction "VDD_CORE4_G7") (pintype "bidirectional"))
    )
    (net (code "307") (name "unconnected-(SIPE-VDD_CORE5-PadG10)") (class "Default")
      (node (ref "SIP") (pin "G10") (pinfunction "VDD_CORE5_G10") (pintype "bidirectional"))
    )
    (net (code "308") (name "unconnected-(SIPE-VDD_CORE6-PadH11)") (class "Default")
      (node (ref "SIP") (pin "H11") (pinfunction "VDD_CORE6_H11") (pintype "bidirectional"))
    )
    (net (code "309") (name "unconnected-(SIPE-VDD_CORE7-PadJ12)") (class "Default")
      (node (ref "SIP") (pin "J12") (pinfunction "VDD_CORE7_J12") (pintype "bidirectional"))
    )
    (net (code "310") (name "unconnected-(SIPE-VDD_CORE8-PadK6)") (class "Default")
      (node (ref "SIP") (pin "K6") (pinfunction "VDD_CORE8_K6") (pintype "bidirectional"))
    )
    (net (code "311") (name "unconnected-(SIPE-VDD_CORE9-PadK8)") (class "Default")
      (node (ref "SIP") (pin "K8") (pinfunction "VDD_CORE9_K8") (pintype "bidirectional"))
    )
    (net (code "312") (name "unconnected-(SIPE-VDD_CORE10-PadK12)") (class "Default")
      (node (ref "SIP") (pin "K12") (pinfunction "VDD_CORE10_K12") (pintype "bidirectional"))
    )
    (net (code "313") (name "unconnected-(SIPE-VDD_CORE11-PadL6)") (class "Default")
      (node (ref "SIP") (pin "L6") (pinfunction "VDD_CORE11_L6") (pintype "bidirectional"))
    )
    (net (code "314") (name "unconnected-(SIPE-VDD_CORE12-PadL7)") (class "Default")
      (node (ref "SIP") (pin "L7") (pinfunction "VDD_CORE12_L7") (pintype "bidirectional"))
    )
    (net (code "315") (name "unconnected-(SIPE-VDD_CORE13-PadL8)") (class "Default")
      (node (ref "SIP") (pin "L8") (pinfunction "VDD_CORE13_L8") (pintype "bidirectional"))
    )
    (net (code "316") (name "unconnected-(SIPE-VDD_CORE14-PadL9)") (class "Default")
      (node (ref "SIP") (pin "L9") (pinfunction "VDD_CORE14_L9") (pintype "bidirectional"))
    )
    (net (code "317") (name "unconnected-(SIPE-VDD_CORE15-PadM11)") (class "Default")
      (node (ref "SIP") (pin "M11") (pinfunction "VDD_CORE15_M11") (pintype "bidirectional"))
    )
    (net (code "318") (name "unconnected-(SIPE-VDD_CORE16-PadM13)") (class "Default")
      (node (ref "SIP") (pin "M13") (pinfunction "VDD_CORE16_M13") (pintype "bidirectional"))
    )
    (net (code "319") (name "unconnected-(SIPE-VDD_CORE17-PadN8)") (class "Default")
      (node (ref "SIP") (pin "N8") (pinfunction "VDD_CORE17_N8") (pintype "bidirectional"))
    )
    (net (code "320") (name "unconnected-(SIPE-VDD_CORE18-PadN9)") (class "Default")
      (node (ref "SIP") (pin "N9") (pinfunction "VDD_CORE18_N9") (pintype "bidirectional"))
    )
    (net (code "321") (name "unconnected-(SIPE-VDD_CORE19-PadN12)") (class "Default")
      (node (ref "SIP") (pin "N12") (pinfunction "VDD_CORE19_N12") (pintype "bidirectional"))
    )
    (net (code "322") (name "unconnected-(SIPE-VDD_CORE20-PadN13)") (class "Default")
      (node (ref "SIP") (pin "N13") (pinfunction "VDD_CORE20_N13") (pintype "bidirectional"))
    )
    (net (code "323") (name "unconnected-(SIPE-VDD_MPU0-PadF10)") (class "Default")
      (node (ref "SIP") (pin "F10") (pinfunction "VDD_MPU0_F10") (pintype "bidirectional"))
    )
    (net (code "324") (name "unconnected-(SIPE-VDD_MPU1-PadF11)") (class "Default")
      (node (ref "SIP") (pin "F11") (pinfunction "VDD_MPU1_F11") (pintype "bidirectional"))
    )
    (net (code "325") (name "unconnected-(SIPE-VDD_MPU2-PadF12)") (class "Default")
      (node (ref "SIP") (pin "F12") (pinfunction "VDD_MPU2_F12") (pintype "bidirectional"))
    )
    (net (code "326") (name "unconnected-(SIPE-VDD_MPU3-PadF13)") (class "Default")
      (node (ref "SIP") (pin "F13") (pinfunction "VDD_MPU3_F13") (pintype "bidirectional"))
    )
    (net (code "327") (name "unconnected-(SIPE-VDD_MPU4-PadG13)") (class "Default")
      (node (ref "SIP") (pin "G13") (pinfunction "VDD_MPU4_G13") (pintype "bidirectional"))
    )
    (net (code "328") (name "unconnected-(SIPE-VDD_MPU5-PadH13)") (class "Default")
      (node (ref "SIP") (pin "H13") (pinfunction "VDD_MPU5_H13") (pintype "bidirectional"))
    )
    (net (code "329") (name "unconnected-(SIPE-VDD_MPU6-PadJ13)") (class "Default")
      (node (ref "SIP") (pin "J13") (pinfunction "VDD_MPU6_J13") (pintype "bidirectional"))
    )
    (net (code "330") (name "unconnected-(SIPE-VDD_MPU_MON-PadA2)") (class "Default")
      (node (ref "SIP") (pin "A2") (pinfunction "VDD_MPU_MON_A2") (pintype "bidirectional"))
    )
    (net (code "331") (name "unconnected-(SIPE-VDD_PLL1-PadE7)") (class "Default")
      (node (ref "SIP") (pin "E7") (pinfunction "VDD_PLL1_E7") (pintype "bidirectional"))
    )
    (net (code "332") (name "unconnected-(SIPE-VDD_PLL2-PadH15)") (class "Default")
      (node (ref "SIP") (pin "H15") (pinfunction "VDD_PLL2_H15") (pintype "bidirectional"))
    )
    (net (code "333") (name "unconnected-(SIPE-VDD_PLL3-PadR10)") (class "Default")
      (node (ref "SIP") (pin "R10") (pinfunction "VDD_PLL3_R10") (pintype "bidirectional"))
    )
    (net (code "334") (name "unconnected-(SIPE-VDD_PLL4-PadR11)") (class "Default")
      (node (ref "SIP") (pin "R11") (pinfunction "VDD_PLL4_R11") (pintype "bidirectional"))
    )
    (net (code "335") (name "unconnected-(SIPE-VPP-PadM5)") (class "Default")
      (node (ref "SIP") (pin "M5") (pinfunction "VPP_M5") (pintype "bidirectional"))
    )
    (net (code "336") (name "unconnected-(U1-N.C.-Pad5)") (class "Default")
      (node (ref "U1") (pin "5") (pinfunction "N.C._5") (pintype "no_connect"))
    )
    (net (code "337") (name "unconnected-(U4-ID-Pad3)") (class "Default")
      (node (ref "U4") (pin "3") (pinfunction "ID_3") (pintype "passive"))
    )
    (net (code "338") (name "unconnected-(U4-N.C.-Pad5)") (class "Default")
      (node (ref "U4") (pin "5") (pinfunction "N.C._5") (pintype "no_connect"))
    )
    (net (code "339") (name "unconnected-(U6-NC-Pad1)") (class "Default")
      (node (ref "U6") (pin "1") (pinfunction "NC_1") (pintype "passive"))
    )
    (net (code "340") (name "unconnected-(U8-NC1-PadE1)") (class "Default")
      (node (ref "U8") (pin "E1") (pinfunction "NC1_E1") (pintype "bidirectional"))
    )
    (net (code "341") (name "unconnected-(U8-NC2-PadE2)") (class "Default")
      (node (ref "U8") (pin "E2") (pinfunction "NC2_E2") (pintype "bidirectional"))
    )
    (net (code "342") (name "unconnected-(U8-NC3-PadE3)") (class "Default")
      (node (ref "U8") (pin "E3") (pinfunction "NC3_E3") (pintype "bidirectional"))
    )
    (net (code "343") (name "unconnected-(U8-NC4-PadA2)") (class "Default")
      (node (ref "U8") (pin "A2") (pinfunction "NC4_A2") (pintype "bidirectional"))
    )
    (net (code "344") (name "unconnected-(U8-NC5-PadA6)") (class "Default")
      (node (ref "U8") (pin "A6") (pinfunction "NC5_A6") (pintype "bidirectional"))
    )
    (net (code "345") (name "unconnected-(U8-NC6-PadA7)") (class "Default")
      (node (ref "U8") (pin "A7") (pinfunction "NC6_A7") (pintype "bidirectional"))
    )
    (net (code "346") (name "unconnected-(U8-NC7-PadA8)") (class "Default")
      (node (ref "U8") (pin "A8") (pinfunction "NC7_A8") (pintype "bidirectional"))
    )
    (net (code "347") (name "unconnected-(U8-NC8-PadE8)") (class "Default")
      (node (ref "U8") (pin "E8") (pinfunction "NC8_E8") (pintype "bidirectional"))
    )
    (net (code "348") (name "unconnected-(U8-NC9-PadE9)") (class "Default")
      (node (ref "U8") (pin "E9") (pinfunction "NC9_E9") (pintype "bidirectional"))
    )
    (net (code "349") (name "unconnected-(U8-NC10-PadE10)") (class "Default")
      (node (ref "U8") (pin "E10") (pinfunction "NC10_E10") (pintype "bidirectional"))
    )
    (net (code "350") (name "unconnected-(U8-NC11-PadA1)") (class "Default")
      (node (ref "U8") (pin "A1") (pinfunction "NC11_A1") (pintype "bidirectional"))
    )
    (net (code "351") (name "unconnected-(U8-NC12-PadE12)") (class "Default")
      (node (ref "U8") (pin "E12") (pinfunction "NC12_E12") (pintype "bidirectional"))
    )
    (net (code "352") (name "unconnected-(U8-NC13-PadE13)") (class "Default")
      (node (ref "U8") (pin "E13") (pinfunction "NC13_E13") (pintype "bidirectional"))
    )
    (net (code "353") (name "unconnected-(U8-NC14-PadE14)") (class "Default")
      (node (ref "U8") (pin "E14") (pinfunction "NC14_E14") (pintype "bidirectional"))
    )
    (net (code "354") (name "unconnected-(U8-NC15-PadF1)") (class "Default")
      (node (ref "U8") (pin "F1") (pinfunction "NC15_F1") (pintype "bidirectional"))
    )
    (net (code "355") (name "unconnected-(U8-NC16-PadF2)") (class "Default")
      (node (ref "U8") (pin "F2") (pinfunction "NC16_F2") (pintype "bidirectional"))
    )
    (net (code "356") (name "unconnected-(U8-NC17-PadF3)") (class "Default")
      (node (ref "U8") (pin "F3") (pinfunction "NC17_F3") (pintype "bidirectional"))
    )
    (net (code "357") (name "unconnected-(U8-NC18-PadA9)") (class "Default")
      (node (ref "U8") (pin "A9") (pinfunction "NC18_A9") (pintype "bidirectional"))
    )
    (net (code "358") (name "unconnected-(U8-NC19-PadB14)") (class "Default")
      (node (ref "U8") (pin "B14") (pinfunction "NC19_B14") (pintype "bidirectional"))
    )
    (net (code "359") (name "unconnected-(U8-NC20-PadC14)") (class "Default")
      (node (ref "U8") (pin "C14") (pinfunction "NC20_C14") (pintype "bidirectional"))
    )
    (net (code "360") (name "unconnected-(U8-NC21-PadC13)") (class "Default")
      (node (ref "U8") (pin "C13") (pinfunction "NC21_C13") (pintype "bidirectional"))
    )
    (net (code "361") (name "unconnected-(U8-NC22-PadC12)") (class "Default")
      (node (ref "U8") (pin "C12") (pinfunction "NC22_C12") (pintype "bidirectional"))
    )
    (net (code "362") (name "unconnected-(U8-NC23-PadC11)") (class "Default")
      (node (ref "U8") (pin "C11") (pinfunction "NC23_C11") (pintype "bidirectional"))
    )
    (net (code "363") (name "unconnected-(U8-NC24-PadF10)") (class "Default")
      (node (ref "U8") (pin "F10") (pinfunction "NC24_F10") (pintype "bidirectional"))
    )
    (net (code "364") (name "unconnected-(U8-NC25-PadC10)") (class "Default")
      (node (ref "U8") (pin "C10") (pinfunction "NC25_C10") (pintype "bidirectional"))
    )
    (net (code "365") (name "unconnected-(U8-NC26-PadF12)") (class "Default")
      (node (ref "U8") (pin "F12") (pinfunction "NC26_F12") (pintype "bidirectional"))
    )
    (net (code "366") (name "unconnected-(U8-NC27-PadF13)") (class "Default")
      (node (ref "U8") (pin "F13") (pinfunction "NC27_F13") (pintype "bidirectional"))
    )
    (net (code "367") (name "unconnected-(U8-NC28-PadF14)") (class "Default")
      (node (ref "U8") (pin "F14") (pinfunction "NC28_F14") (pintype "bidirectional"))
    )
    (net (code "368") (name "unconnected-(U8-NC29-PadC9)") (class "Default")
      (node (ref "U8") (pin "C9") (pinfunction "NC29_C9") (pintype "bidirectional"))
    )
    (net (code "369") (name "unconnected-(U8-NC30-PadC8)") (class "Default")
      (node (ref "U8") (pin "C8") (pinfunction "NC30_C8") (pintype "bidirectional"))
    )
    (net (code "370") (name "unconnected-(U8-NC31-PadC7)") (class "Default")
      (node (ref "U8") (pin "C7") (pinfunction "NC31_C7") (pintype "bidirectional"))
    )
    (net (code "371") (name "unconnected-(U8-NC32-PadC5)") (class "Default")
      (node (ref "U8") (pin "C5") (pinfunction "NC32_C5") (pintype "bidirectional"))
    )
    (net (code "372") (name "unconnected-(U8-NC33-PadC3)") (class "Default")
      (node (ref "U8") (pin "C3") (pinfunction "NC33_C3") (pintype "bidirectional"))
    )
    (net (code "373") (name "unconnected-(U8-NC34-PadC1)") (class "Default")
      (node (ref "U8") (pin "C1") (pinfunction "NC34_C1") (pintype "bidirectional"))
    )
    (net (code "374") (name "unconnected-(U8-NC35-PadD14)") (class "Default")
      (node (ref "U8") (pin "D14") (pinfunction "NC35_D14") (pintype "bidirectional"))
    )
    (net (code "375") (name "unconnected-(U8-NC36-PadD13)") (class "Default")
      (node (ref "U8") (pin "D13") (pinfunction "NC36_D13") (pintype "bidirectional"))
    )
    (net (code "376") (name "unconnected-(U8-NC37-PadD12)") (class "Default")
      (node (ref "U8") (pin "D12") (pinfunction "NC37_D12") (pintype "bidirectional"))
    )
    (net (code "377") (name "unconnected-(U8-NC38-PadD4)") (class "Default")
      (node (ref "U8") (pin "D4") (pinfunction "NC38_D4") (pintype "bidirectional"))
    )
    (net (code "378") (name "unconnected-(U8-NC39-PadD3)") (class "Default")
      (node (ref "U8") (pin "D3") (pinfunction "NC39_D3") (pintype "bidirectional"))
    )
    (net (code "379") (name "unconnected-(U8-NC40-PadG12)") (class "Default")
      (node (ref "U8") (pin "G12") (pinfunction "NC40_G12") (pintype "bidirectional"))
    )
    (net (code "380") (name "unconnected-(U8-NC41-PadG13)") (class "Default")
      (node (ref "U8") (pin "G13") (pinfunction "NC41_G13") (pintype "bidirectional"))
    )
    (net (code "381") (name "unconnected-(U8-NC42-PadG14)") (class "Default")
      (node (ref "U8") (pin "G14") (pinfunction "NC42_G14") (pintype "bidirectional"))
    )
    (net (code "382") (name "unconnected-(U8-NC43-PadH1)") (class "Default")
      (node (ref "U8") (pin "H1") (pinfunction "NC43_H1") (pintype "bidirectional"))
    )
    (net (code "383") (name "unconnected-(U8-NC44-PadH2)") (class "Default")
      (node (ref "U8") (pin "H2") (pinfunction "NC44_H2") (pintype "bidirectional"))
    )
    (net (code "384") (name "unconnected-(U8-NC45-PadH3)") (class "Default")
      (node (ref "U8") (pin "H3") (pinfunction "NC45_H3") (pintype "bidirectional"))
    )
    (net (code "385") (name "unconnected-(U8-NC46-PadD2)") (class "Default")
      (node (ref "U8") (pin "D2") (pinfunction "NC46_D2") (pintype "bidirectional"))
    )
    (net (code "386") (name "unconnected-(U8-NC47-PadH5)") (class "Default")
      (node (ref "U8") (pin "H5") (pinfunction "NC47_H5") (pintype "bidirectional"))
    )
    (net (code "387") (name "unconnected-(U8-NC48-PadD1)") (class "Default")
      (node (ref "U8") (pin "D1") (pinfunction "NC48_D1") (pintype "bidirectional"))
    )
    (net (code "388") (name "unconnected-(U8-NC49-PadB13)") (class "Default")
      (node (ref "U8") (pin "B13") (pinfunction "NC49_B13") (pintype "bidirectional"))
    )
    (net (code "389") (name "unconnected-(U8-NC50-PadB12)") (class "Default")
      (node (ref "U8") (pin "B12") (pinfunction "NC50_B12") (pintype "bidirectional"))
    )
    (net (code "390") (name "unconnected-(U8-NC51-PadB11)") (class "Default")
      (node (ref "U8") (pin "B11") (pinfunction "NC51_B11") (pintype "bidirectional"))
    )
    (net (code "391") (name "unconnected-(U8-NC52-PadB10)") (class "Default")
      (node (ref "U8") (pin "B10") (pinfunction "NC52_B10") (pintype "bidirectional"))
    )
    (net (code "392") (name "unconnected-(U8-NC53-PadB9)") (class "Default")
      (node (ref "U8") (pin "B9") (pinfunction "NC53_B9") (pintype "bidirectional"))
    )
    (net (code "393") (name "unconnected-(U8-NC54-PadH12)") (class "Default")
      (node (ref "U8") (pin "H12") (pinfunction "NC54_H12") (pintype "bidirectional"))
    )
    (net (code "394") (name "unconnected-(U8-NC55-PadH13)") (class "Default")
      (node (ref "U8") (pin "H13") (pinfunction "NC55_H13") (pintype "bidirectional"))
    )
    (net (code "395") (name "unconnected-(U8-NC56-PadH14)") (class "Default")
      (node (ref "U8") (pin "H14") (pinfunction "NC56_H14") (pintype "bidirectional"))
    )
    (net (code "396") (name "unconnected-(U8-NC57-PadJ1)") (class "Default")
      (node (ref "U8") (pin "J1") (pinfunction "NC57_J1") (pintype "bidirectional"))
    )
    (net (code "397") (name "unconnected-(U8-NC58-PadJ2)") (class "Default")
      (node (ref "U8") (pin "J2") (pinfunction "NC58_J2") (pintype "bidirectional"))
    )
    (net (code "398") (name "unconnected-(U8-NC59-PadJ3)") (class "Default")
      (node (ref "U8") (pin "J3") (pinfunction "NC59_J3") (pintype "bidirectional"))
    )
    (net (code "399") (name "unconnected-(U8-NC60-PadJ5)") (class "Default")
      (node (ref "U8") (pin "J5") (pinfunction "NC60_J5") (pintype "bidirectional"))
    )
    (net (code "400") (name "unconnected-(U8-NC61-PadP8)") (class "Default")
      (node (ref "U8") (pin "P8") (pinfunction "NC61_P8") (pintype "bidirectional"))
    )
    (net (code "401") (name "unconnected-(U8-NC62-PadP9)") (class "Default")
      (node (ref "U8") (pin "P9") (pinfunction "NC62_P9") (pintype "bidirectional"))
    )
    (net (code "402") (name "unconnected-(U8-NC63-PadP7)") (class "Default")
      (node (ref "U8") (pin "P7") (pinfunction "NC63_P7") (pintype "bidirectional"))
    )
    (net (code "403") (name "unconnected-(U8-NC64-PadP2)") (class "Default")
      (node (ref "U8") (pin "P2") (pinfunction "NC64_P2") (pintype "bidirectional"))
    )
    (net (code "404") (name "unconnected-(U8-NC65-PadP1)") (class "Default")
      (node (ref "U8") (pin "P1") (pinfunction "NC65_P1") (pintype "bidirectional"))
    )
    (net (code "405") (name "unconnected-(U8-NC66-PadN14)") (class "Default")
      (node (ref "U8") (pin "N14") (pinfunction "NC66_N14") (pintype "bidirectional"))
    )
    (net (code "406") (name "unconnected-(U8-NC67-PadN13)") (class "Default")
      (node (ref "U8") (pin "N13") (pinfunction "NC67_N13") (pintype "bidirectional"))
    )
    (net (code "407") (name "unconnected-(U8-NC68-PadN12)") (class "Default")
      (node (ref "U8") (pin "N12") (pinfunction "NC68_N12") (pintype "bidirectional"))
    )
    (net (code "408") (name "unconnected-(U8-NC69-PadJ13)") (class "Default")
      (node (ref "U8") (pin "J13") (pinfunction "NC69_J13") (pintype "bidirectional"))
    )
    (net (code "409") (name "unconnected-(U8-NC70-PadJ14)") (class "Default")
      (node (ref "U8") (pin "J14") (pinfunction "NC70_J14") (pintype "bidirectional"))
    )
    (net (code "410") (name "unconnected-(U8-NC71-PadK1)") (class "Default")
      (node (ref "U8") (pin "K1") (pinfunction "NC71_K1") (pintype "bidirectional"))
    )
    (net (code "411") (name "unconnected-(U8-NC72-PadK2)") (class "Default")
      (node (ref "U8") (pin "K2") (pinfunction "NC72_K2") (pintype "bidirectional"))
    )
    (net (code "412") (name "unconnected-(U8-NC73-PadK3)") (class "Default")
      (node (ref "U8") (pin "K3") (pinfunction "NC73_K3") (pintype "bidirectional"))
    )
    (net (code "413") (name "unconnected-(U8-NC74-PadB8)") (class "Default")
      (node (ref "U8") (pin "B8") (pinfunction "NC74_B8") (pintype "bidirectional"))
    )
    (net (code "414") (name "unconnected-(U8-NC75-PadN10)") (class "Default")
      (node (ref "U8") (pin "N10") (pinfunction "NC75_N10") (pintype "bidirectional"))
    )
    (net (code "415") (name "unconnected-(U8-NC76-PadN11)") (class "Default")
      (node (ref "U8") (pin "N11") (pinfunction "NC76_N11") (pintype "bidirectional"))
    )
    (net (code "416") (name "unconnected-(U8-NC77-PadK7)") (class "Default")
      (node (ref "U8") (pin "K7") (pinfunction "NC77_K7") (pintype "bidirectional"))
    )
    (net (code "417") (name "unconnected-(U8-NC78-PadG10)") (class "Default")
      (node (ref "U8") (pin "G10") (pinfunction "NC78_G10") (pintype "bidirectional"))
    )
    (net (code "418") (name "unconnected-(U8-NC79-PadG3)") (class "Default")
      (node (ref "U8") (pin "G3") (pinfunction "NC79_G3") (pintype "bidirectional"))
    )
    (net (code "419") (name "unconnected-(U8-NC80-PadK10)") (class "Default")
      (node (ref "U8") (pin "K10") (pinfunction "NC80_K10") (pintype "bidirectional"))
    )
    (net (code "420") (name "unconnected-(U8-NC81-PadG2)") (class "Default")
      (node (ref "U8") (pin "G2") (pinfunction "NC81_G2") (pintype "bidirectional"))
    )
    (net (code "421") (name "unconnected-(U8-NC82-PadK12)") (class "Default")
      (node (ref "U8") (pin "K12") (pinfunction "NC82_K12") (pintype "bidirectional"))
    )
    (net (code "422") (name "unconnected-(U8-NC83-PadK13)") (class "Default")
      (node (ref "U8") (pin "K13") (pinfunction "NC83_K13") (pintype "bidirectional"))
    )
    (net (code "423") (name "unconnected-(U8-NC84-PadK14)") (class "Default")
      (node (ref "U8") (pin "K14") (pinfunction "NC84_K14") (pintype "bidirectional"))
    )
    (net (code "424") (name "unconnected-(U8-NC85-PadL1)") (class "Default")
      (node (ref "U8") (pin "L1") (pinfunction "NC85_L1") (pintype "bidirectional"))
    )
    (net (code "425") (name "unconnected-(U8-NC86-PadL2)") (class "Default")
      (node (ref "U8") (pin "L2") (pinfunction "NC86_L2") (pintype "bidirectional"))
    )
    (net (code "426") (name "unconnected-(U8-NC87-PadL3)") (class "Default")
      (node (ref "U8") (pin "L3") (pinfunction "NC87_L3") (pintype "bidirectional"))
    )
    (net (code "427") (name "unconnected-(U8-NC88-PadG1)") (class "Default")
      (node (ref "U8") (pin "G1") (pinfunction "NC88_G1") (pintype "bidirectional"))
    )
    (net (code "428") (name "unconnected-(U8-NC89-PadB7)") (class "Default")
      (node (ref "U8") (pin "B7") (pinfunction "NC89_B7") (pintype "bidirectional"))
    )
    (net (code "429") (name "unconnected-(U8-NC90-PadB1)") (class "Default")
      (node (ref "U8") (pin "B1") (pinfunction "NC90_B1") (pintype "bidirectional"))
    )
    (net (code "430") (name "unconnected-(U8-NC91-PadA14)") (class "Default")
      (node (ref "U8") (pin "A14") (pinfunction "NC91_A14") (pintype "bidirectional"))
    )
    (net (code "431") (name "unconnected-(U8-NC92-PadA13)") (class "Default")
      (node (ref "U8") (pin "A13") (pinfunction "NC92_A13") (pintype "bidirectional"))
    )
    (net (code "432") (name "unconnected-(U8-NC93-PadA12)") (class "Default")
      (node (ref "U8") (pin "A12") (pinfunction "NC93_A12") (pintype "bidirectional"))
    )
    (net (code "433") (name "unconnected-(U8-NC94-PadA11)") (class "Default")
      (node (ref "U8") (pin "A11") (pinfunction "NC94_A11") (pintype "bidirectional"))
    )
    (net (code "434") (name "unconnected-(U8-NC95-PadA10)") (class "Default")
      (node (ref "U8") (pin "A10") (pinfunction "NC95_A10") (pintype "bidirectional"))
    )
    (net (code "435") (name "unconnected-(U8-NC96-PadL12)") (class "Default")
      (node (ref "U8") (pin "L12") (pinfunction "NC96_L12") (pintype "bidirectional"))
    )
    (net (code "436") (name "unconnected-(U8-NC97-PadL13)") (class "Default")
      (node (ref "U8") (pin "L13") (pinfunction "NC97_L13") (pintype "bidirectional"))
    )
    (net (code "437") (name "unconnected-(U8-NC98-PadL14)") (class "Default")
      (node (ref "U8") (pin "L14") (pinfunction "NC98_L14") (pintype "bidirectional"))
    )
    (net (code "438") (name "unconnected-(U8-NC99-PadM1)") (class "Default")
      (node (ref "U8") (pin "M1") (pinfunction "NC99_M1") (pintype "bidirectional"))
    )
    (net (code "439") (name "unconnected-(U8-NC100-PadM2)") (class "Default")
      (node (ref "U8") (pin "M2") (pinfunction "NC100_M2") (pintype "bidirectional"))
    )
    (net (code "440") (name "unconnected-(U8-NC101-PadM3)") (class "Default")
      (node (ref "U8") (pin "M3") (pinfunction "NC101_M3") (pintype "bidirectional"))
    )
    (net (code "441") (name "unconnected-(U8-NC102-PadP13)") (class "Default")
      (node (ref "U8") (pin "P13") (pinfunction "NC102_P13") (pintype "bidirectional"))
    )
    (net (code "442") (name "unconnected-(U8-NC103-PadP12)") (class "Default")
      (node (ref "U8") (pin "P12") (pinfunction "NC103_P12") (pintype "bidirectional"))
    )
    (net (code "443") (name "unconnected-(U8-NC104-PadP11)") (class "Default")
      (node (ref "U8") (pin "P11") (pinfunction "NC104_P11") (pintype "bidirectional"))
    )
    (net (code "444") (name "unconnected-(U8-NC105-PadM7)") (class "Default")
      (node (ref "U8") (pin "M7") (pinfunction "NC105_M7") (pintype "bidirectional"))
    )
    (net (code "445") (name "unconnected-(U8-NC106-PadM8)") (class "Default")
      (node (ref "U8") (pin "M8") (pinfunction "NC106_M8") (pintype "bidirectional"))
    )
    (net (code "446") (name "unconnected-(U8-NC107-PadM9)") (class "Default")
      (node (ref "U8") (pin "M9") (pinfunction "NC107_M9") (pintype "bidirectional"))
    )
    (net (code "447") (name "unconnected-(U8-NC108-PadM10)") (class "Default")
      (node (ref "U8") (pin "M10") (pinfunction "NC108_M10") (pintype "bidirectional"))
    )
    (net (code "448") (name "unconnected-(U8-NC109-PadM11)") (class "Default")
      (node (ref "U8") (pin "M11") (pinfunction "NC109_M11") (pintype "bidirectional"))
    )
    (net (code "449") (name "unconnected-(U8-NC110-PadM12)") (class "Default")
      (node (ref "U8") (pin "M12") (pinfunction "NC110_M12") (pintype "bidirectional"))
    )
    (net (code "450") (name "unconnected-(U8-NC111-PadM13)") (class "Default")
      (node (ref "U8") (pin "M13") (pinfunction "NC111_M13") (pintype "bidirectional"))
    )
    (net (code "451") (name "unconnected-(U8-NC112-PadM14)") (class "Default")
      (node (ref "U8") (pin "M14") (pinfunction "NC112_M14") (pintype "bidirectional"))
    )
    (net (code "452") (name "unconnected-(U8-NC113-PadN1)") (class "Default")
      (node (ref "U8") (pin "N1") (pinfunction "NC113_N1") (pintype "bidirectional"))
    )
    (net (code "453") (name "unconnected-(U8-NC114-PadP10)") (class "Default")
      (node (ref "U8") (pin "P10") (pinfunction "NC114_P10") (pintype "bidirectional"))
    )
    (net (code "454") (name "unconnected-(U8-NC115-PadN3)") (class "Default")
      (node (ref "U8") (pin "N3") (pinfunction "NC115_N3") (pintype "bidirectional"))
    )
    (net (code "455") (name "unconnected-(U8-NC116-PadP14)") (class "Default")
      (node (ref "U8") (pin "P14") (pinfunction "NC116_P14") (pintype "bidirectional"))
    )
    (net (code "456") (name "unconnected-(U8-NC117-PadJ12)") (class "Default")
      (node (ref "U8") (pin "J12") (pinfunction "NC117_J12") (pintype "bidirectional"))
    )
    (net (code "457") (name "unconnected-(U8-NC118-PadN7)") (class "Default")
      (node (ref "U8") (pin "N7") (pinfunction "NC118_N7") (pintype "bidirectional"))
    )
    (net (code "458") (name "unconnected-(U8-NC119-PadN8)") (class "Default")
      (node (ref "U8") (pin "N8") (pinfunction "NC119_N8") (pintype "bidirectional"))
    )
    (net (code "459") (name "unconnected-(U8-NC120-PadN9)") (class "Default")
      (node (ref "U8") (pin "N9") (pinfunction "NC120_N9") (pintype "bidirectional"))
    )
    (net (code "460") (name "unconnected-(U8-NC121-PadE5)") (class "Default")
      (node (ref "U8") (pin "E5") (pinfunction "NC121_E5") (pintype "bidirectional"))
    )
    (net (code "461") (name "unconnected-(U8-NC122-PadN6)") (class "Default")
      (node (ref "U8") (pin "N6") (pinfunction "NC122_N6") (pintype "bidirectional"))
    )
    (net (code "462") (name "unconnected-(U8-NC123-PadK6)") (class "Default")
      (node (ref "U8") (pin "K6") (pinfunction "NC123_K6") (pintype "bidirectional"))
    )
  )
)
